# PCB_KioskMB_r3_3-03.net
KiCad netlist of a schematic drawn in EAGLE
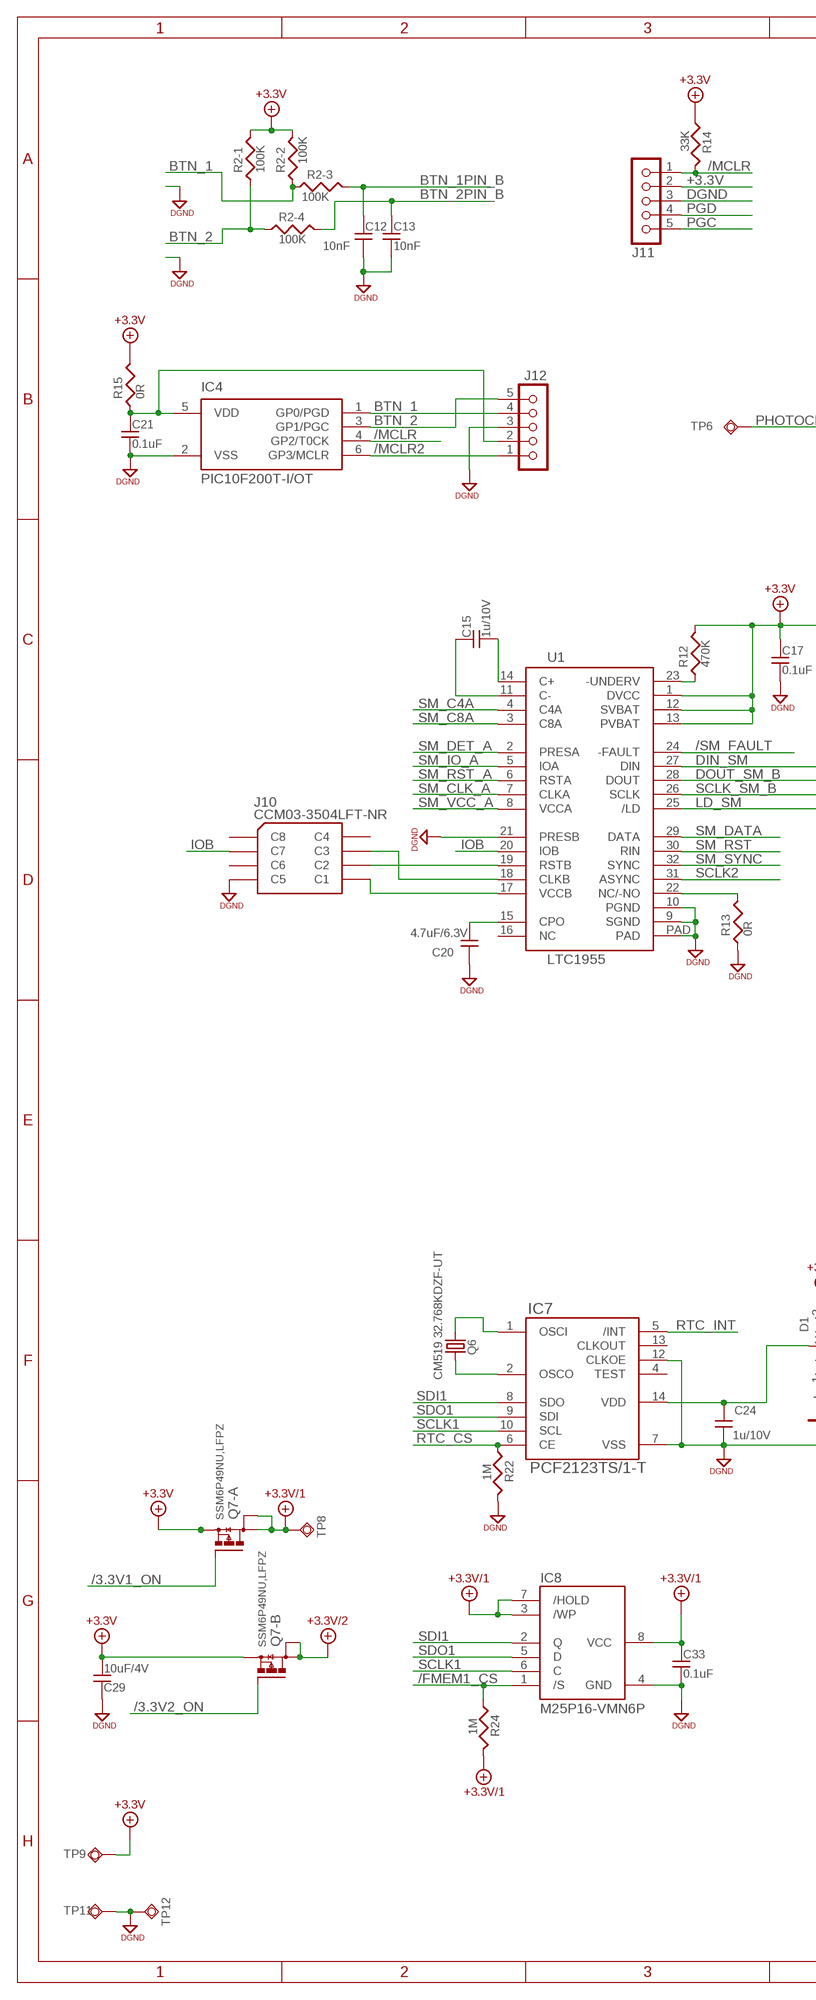
[diagram p0: schematic, sheet 1, part 1 of 2]
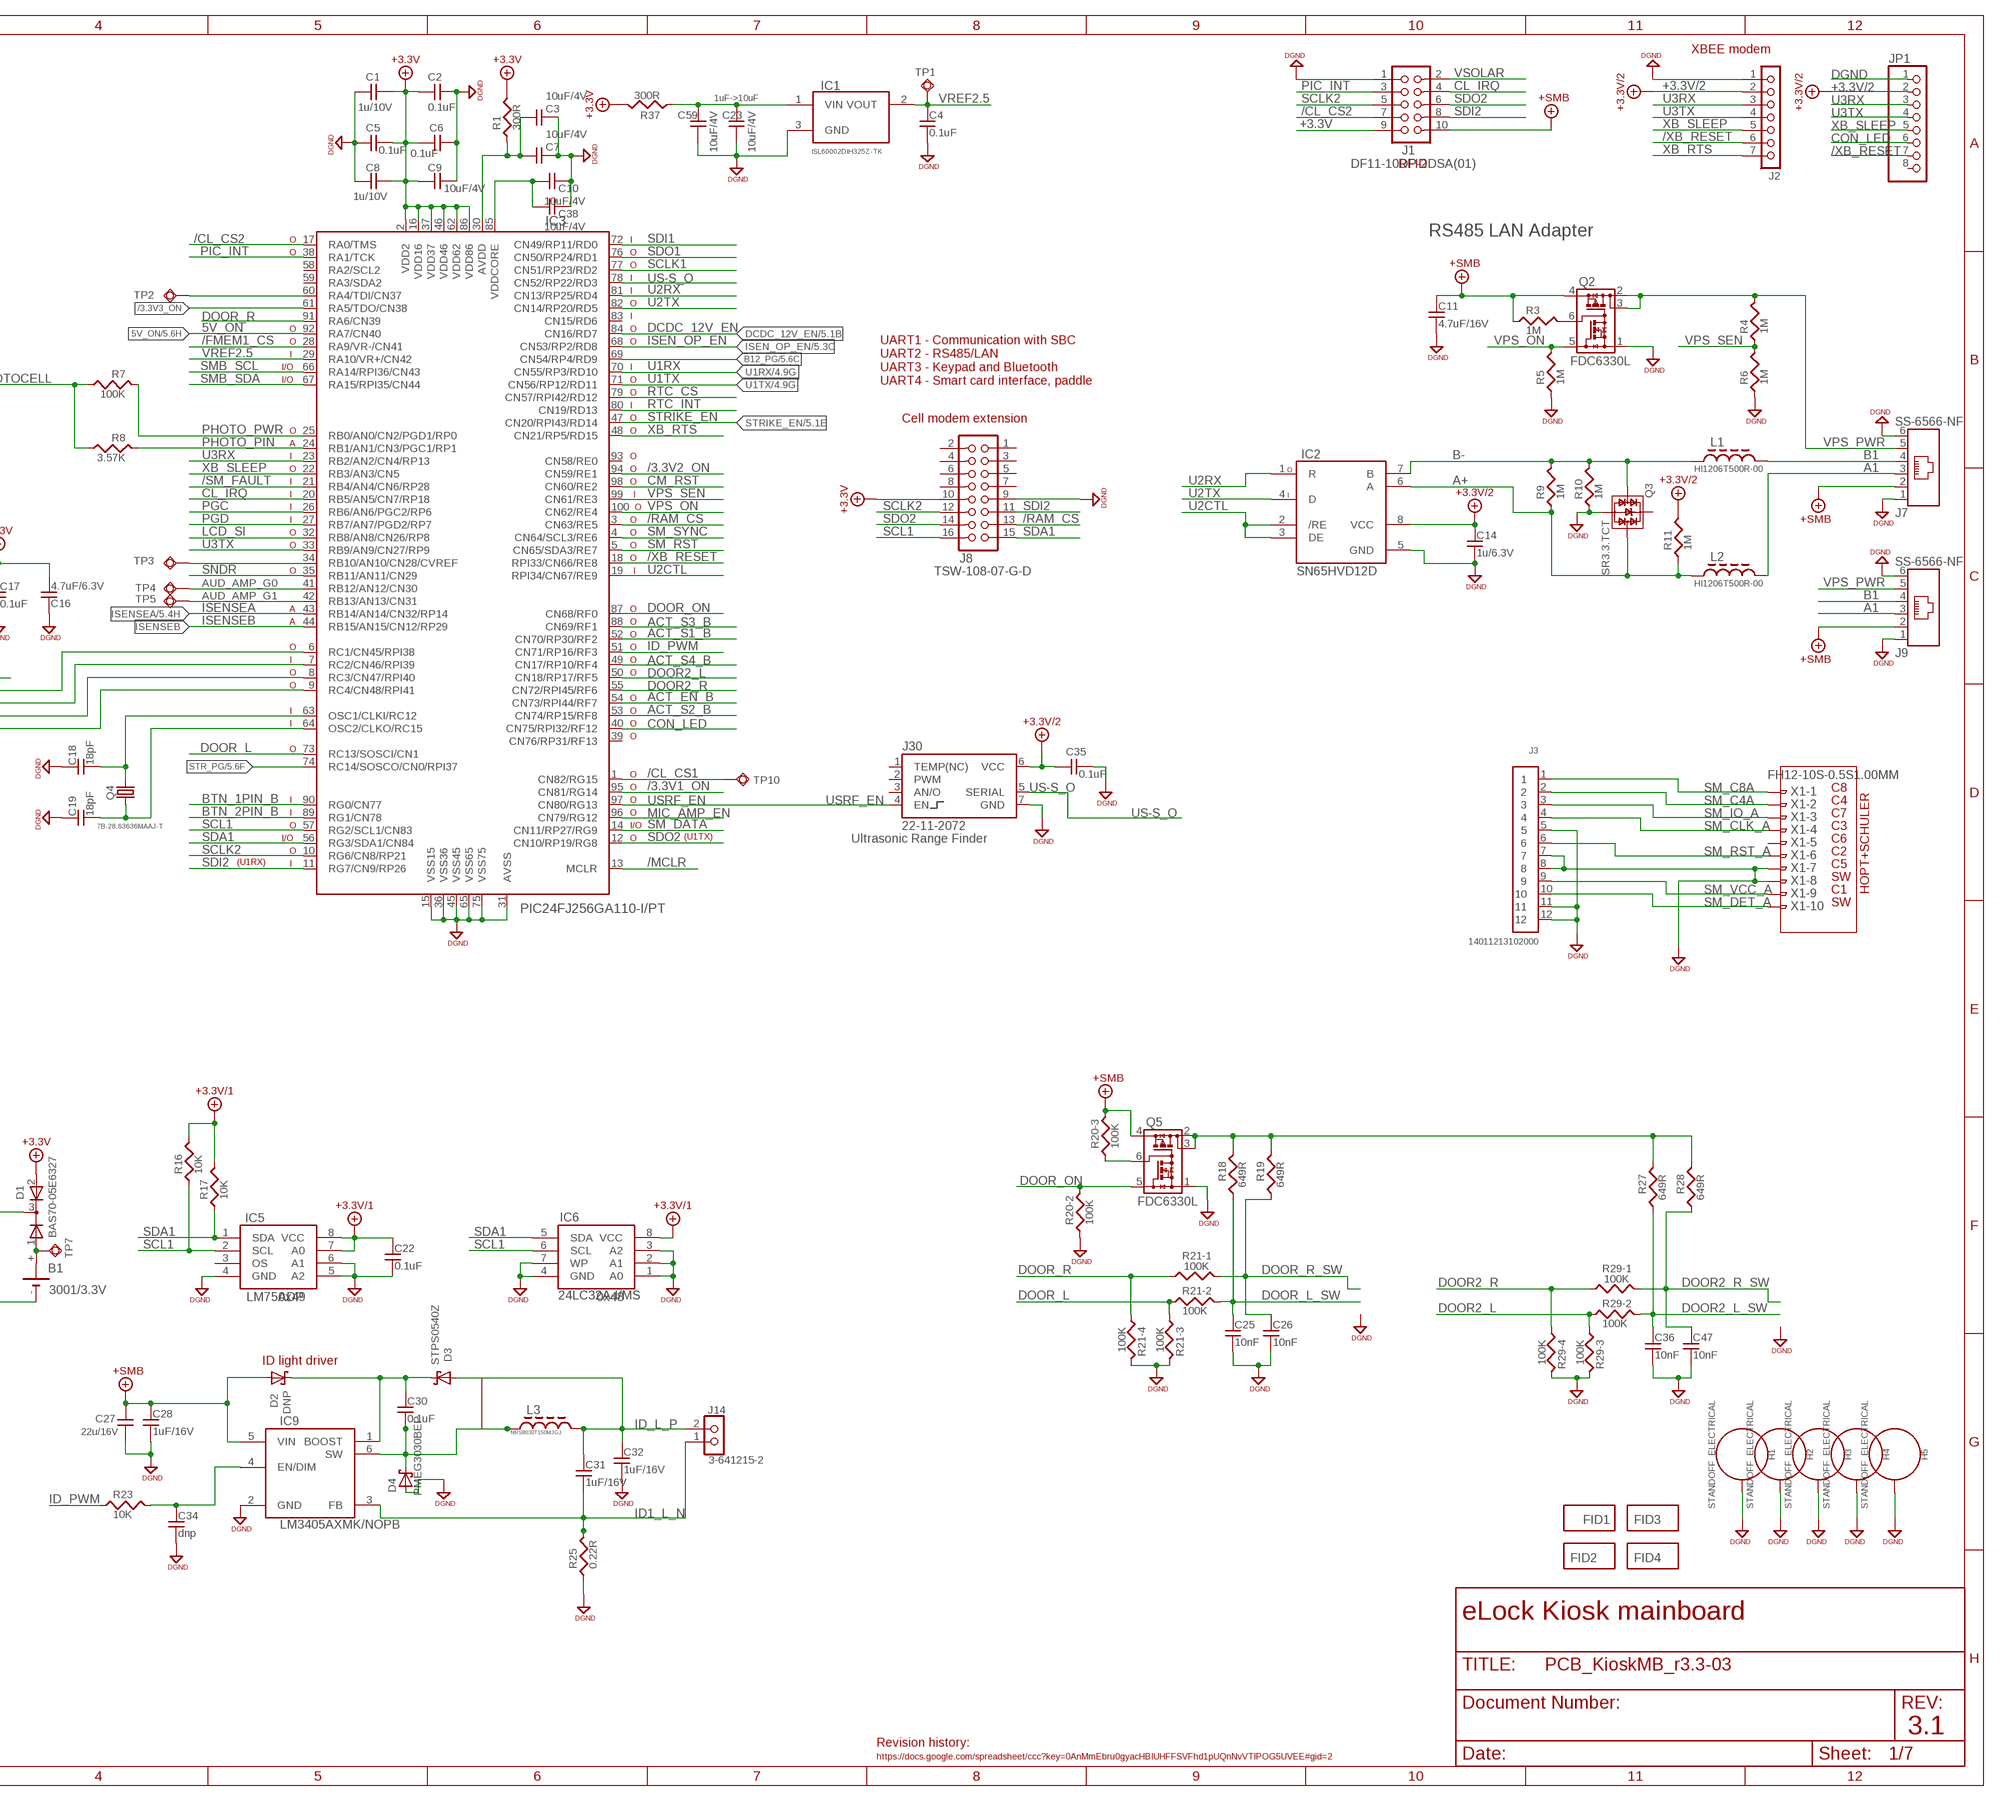
[diagram p1: schematic, sheet 1, part 2 of 2]
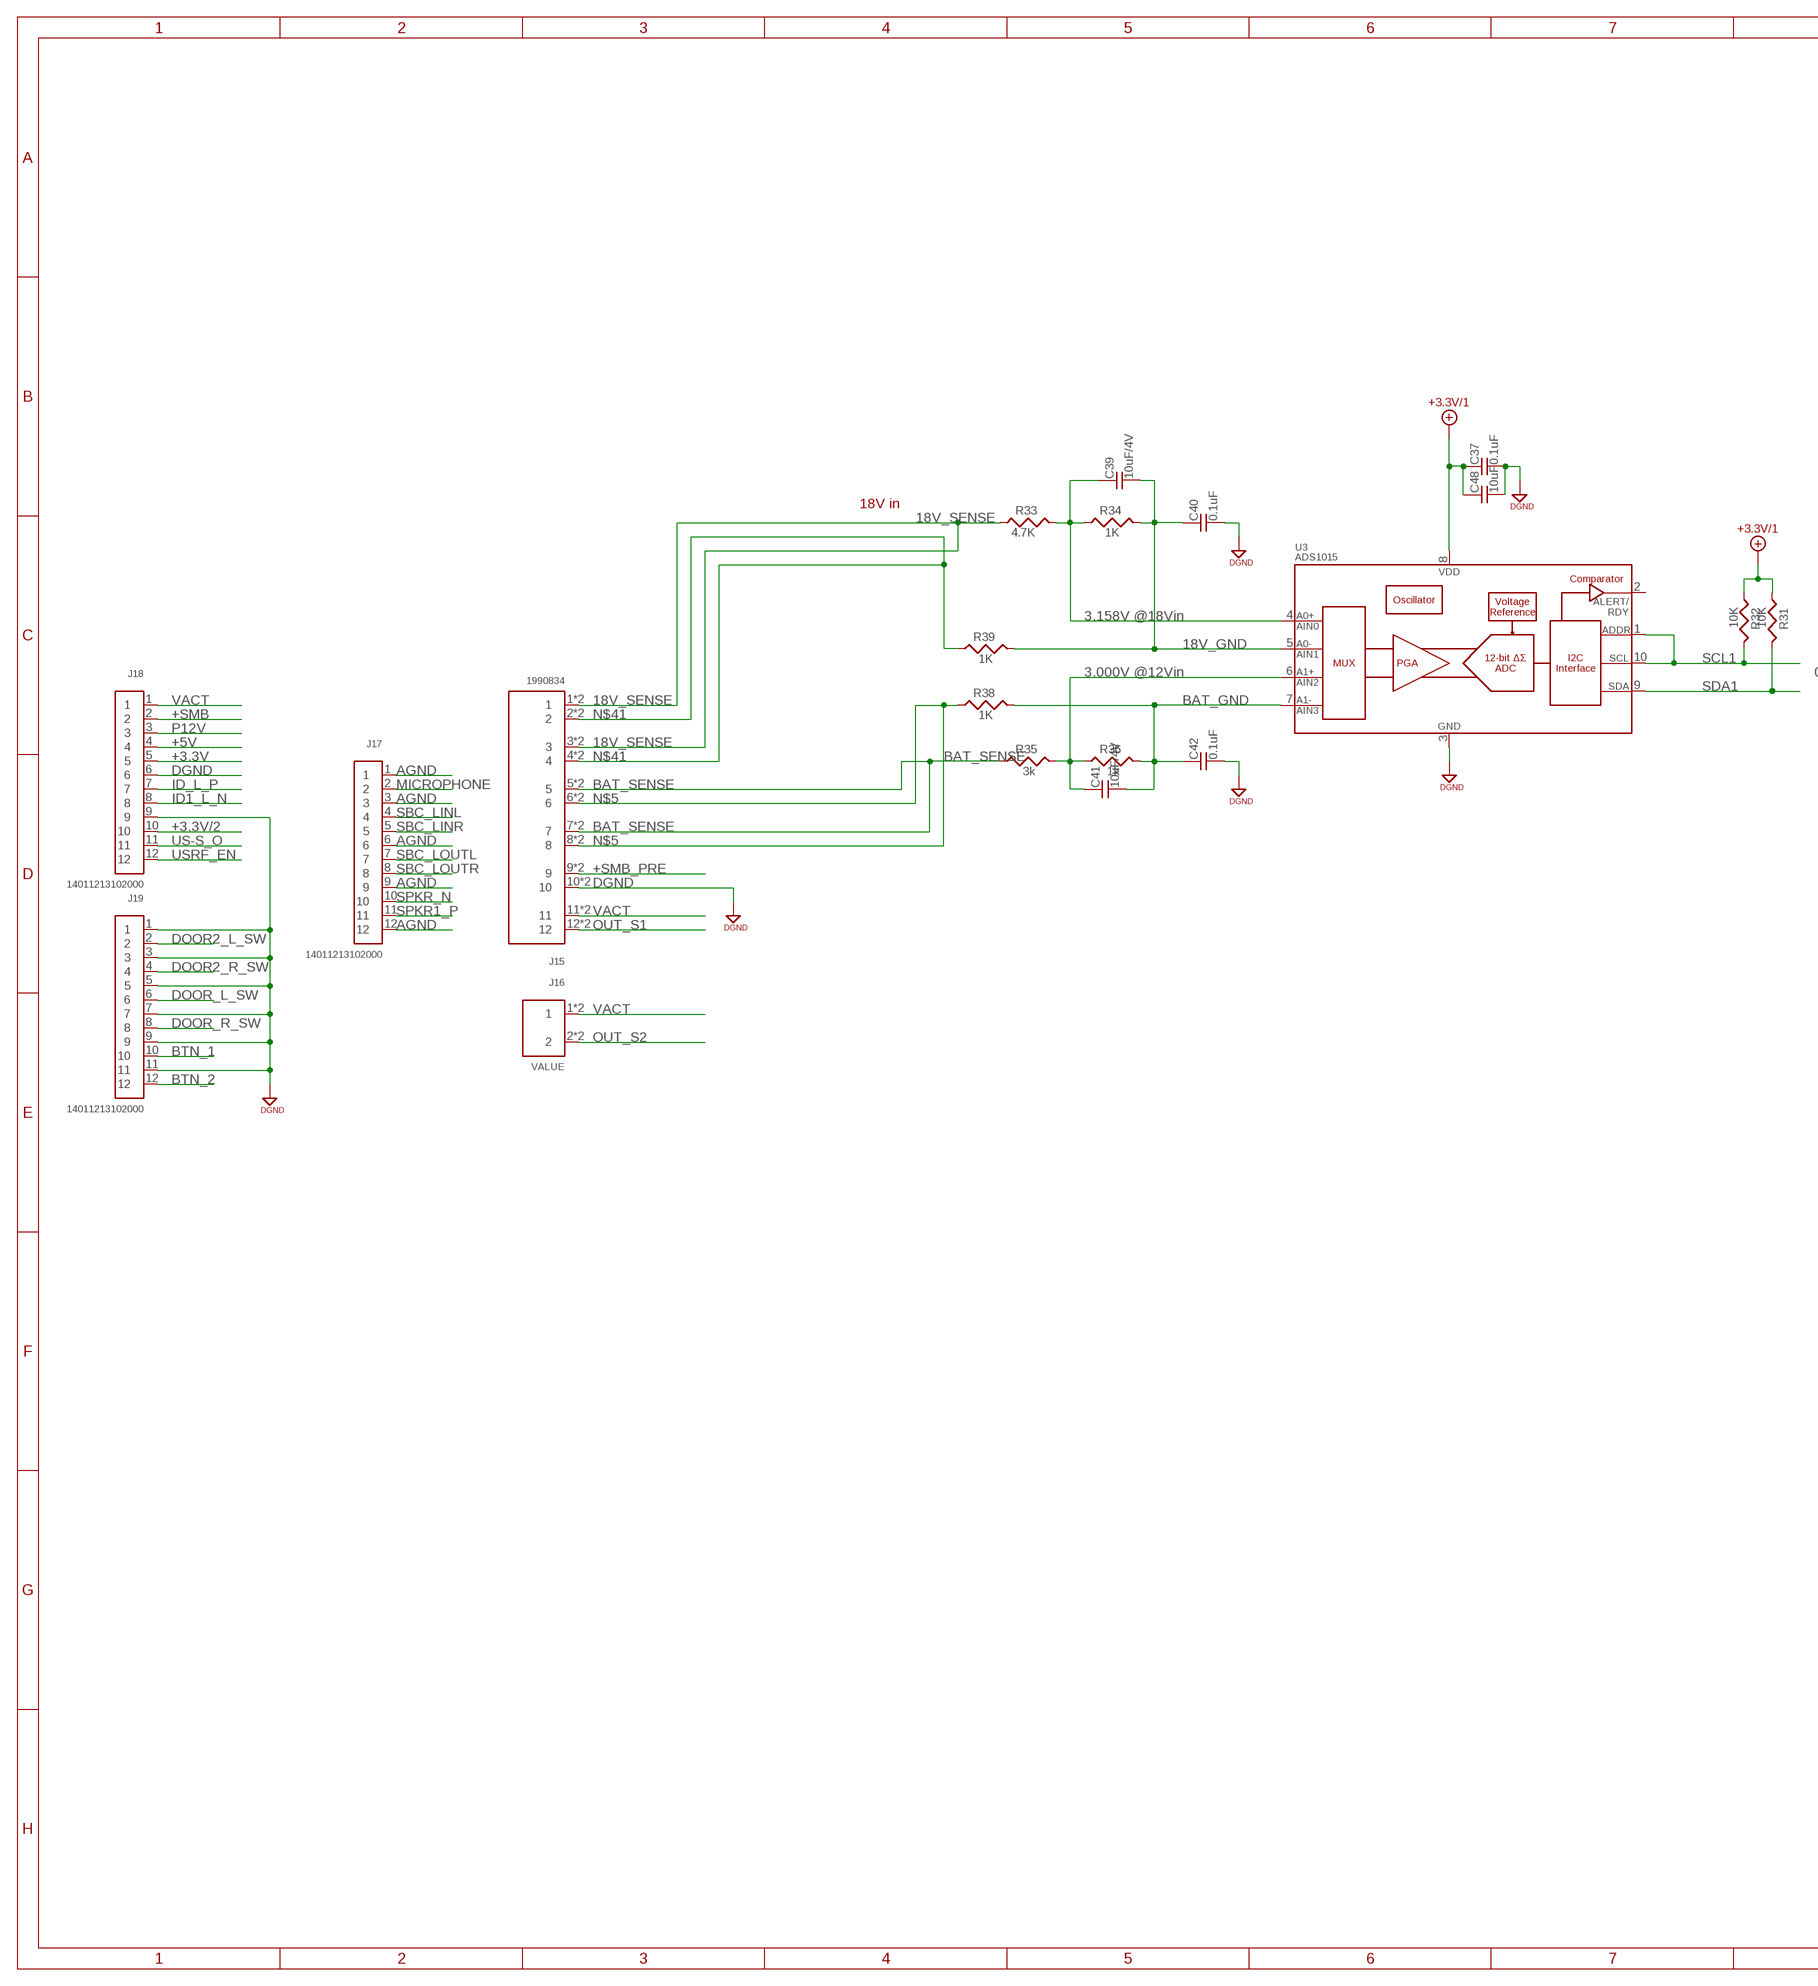
[diagram p2: schematic, sheet 2, part 1 of 2]
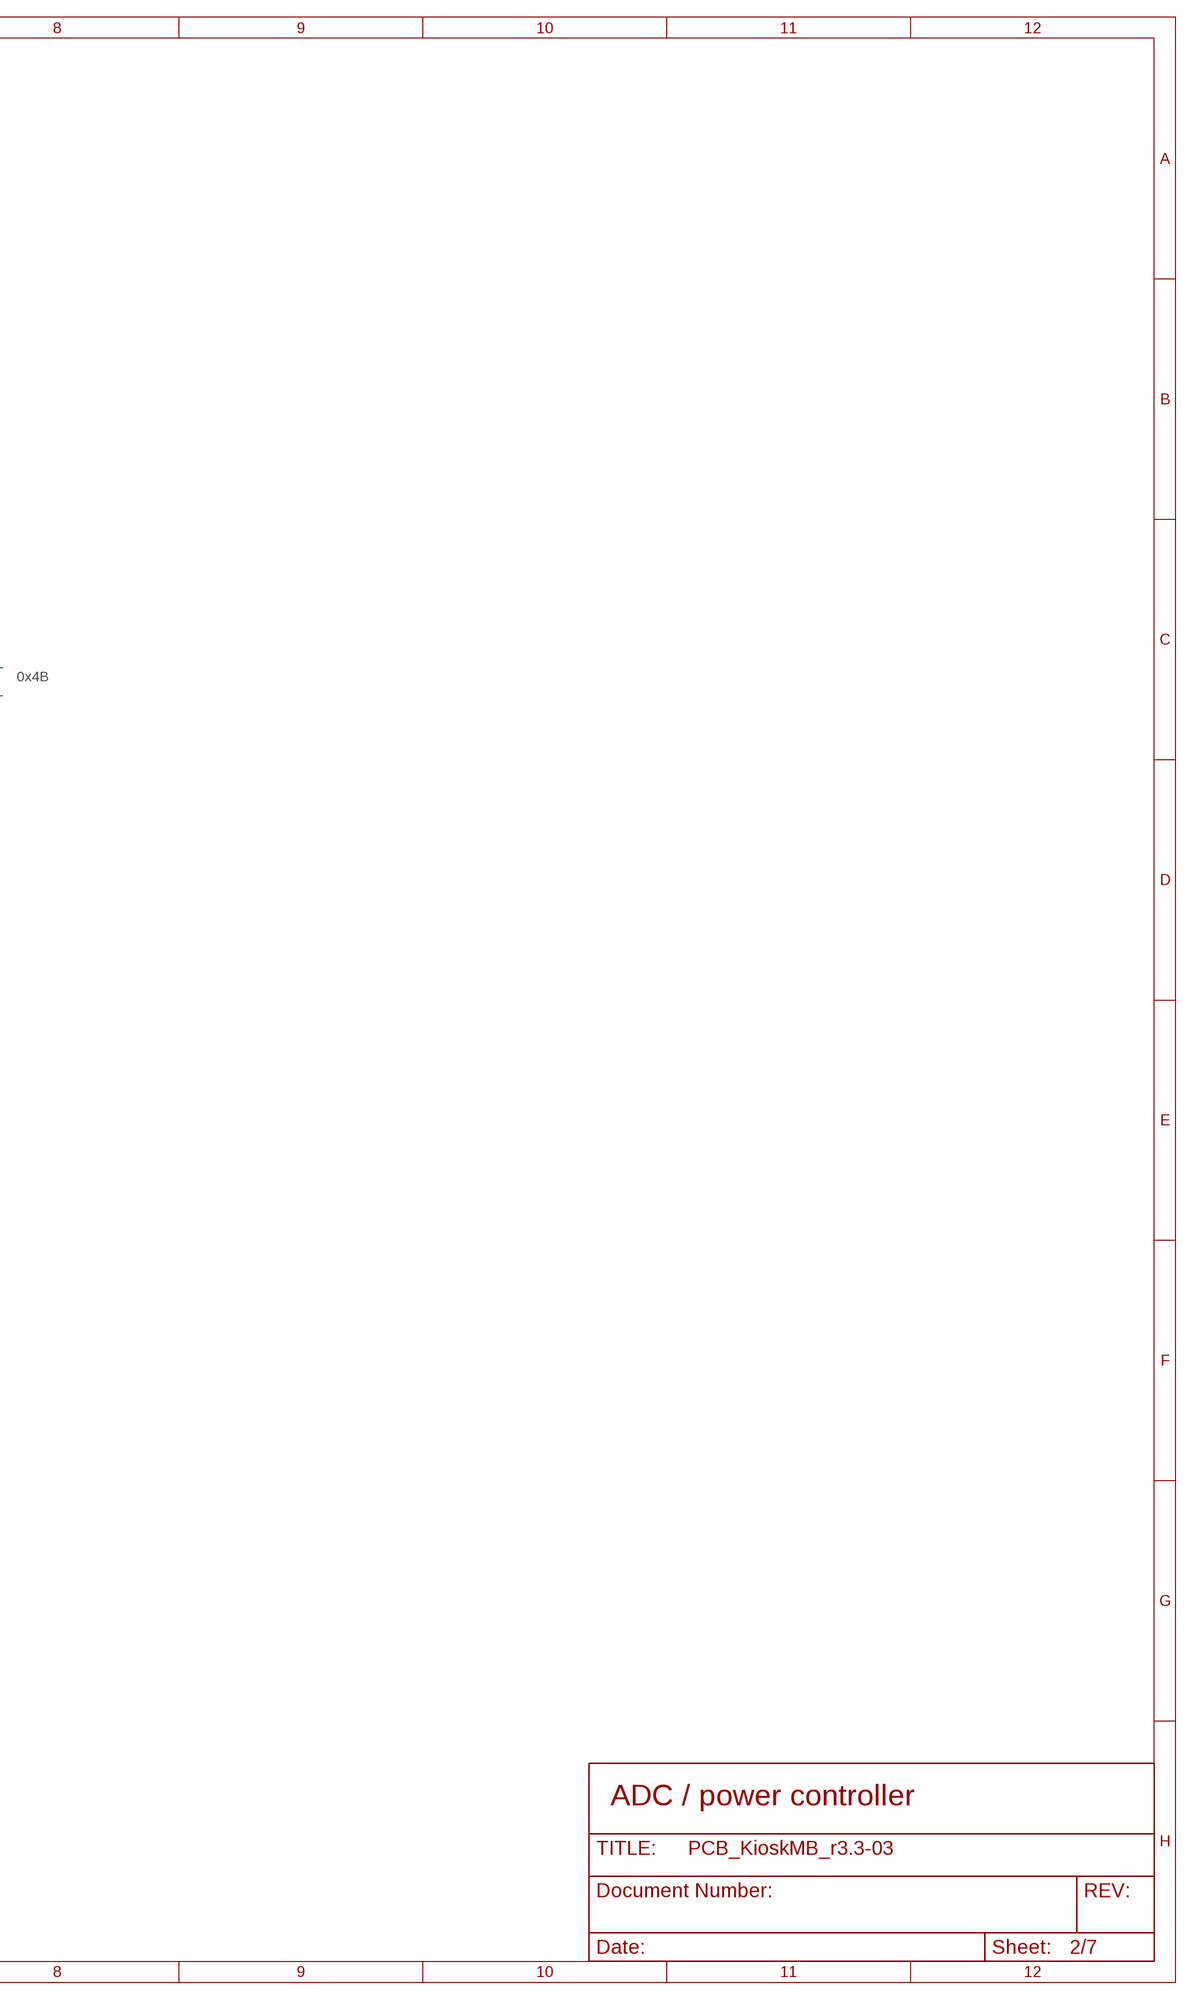
[diagram p3: schematic, sheet 2, part 2 of 2]
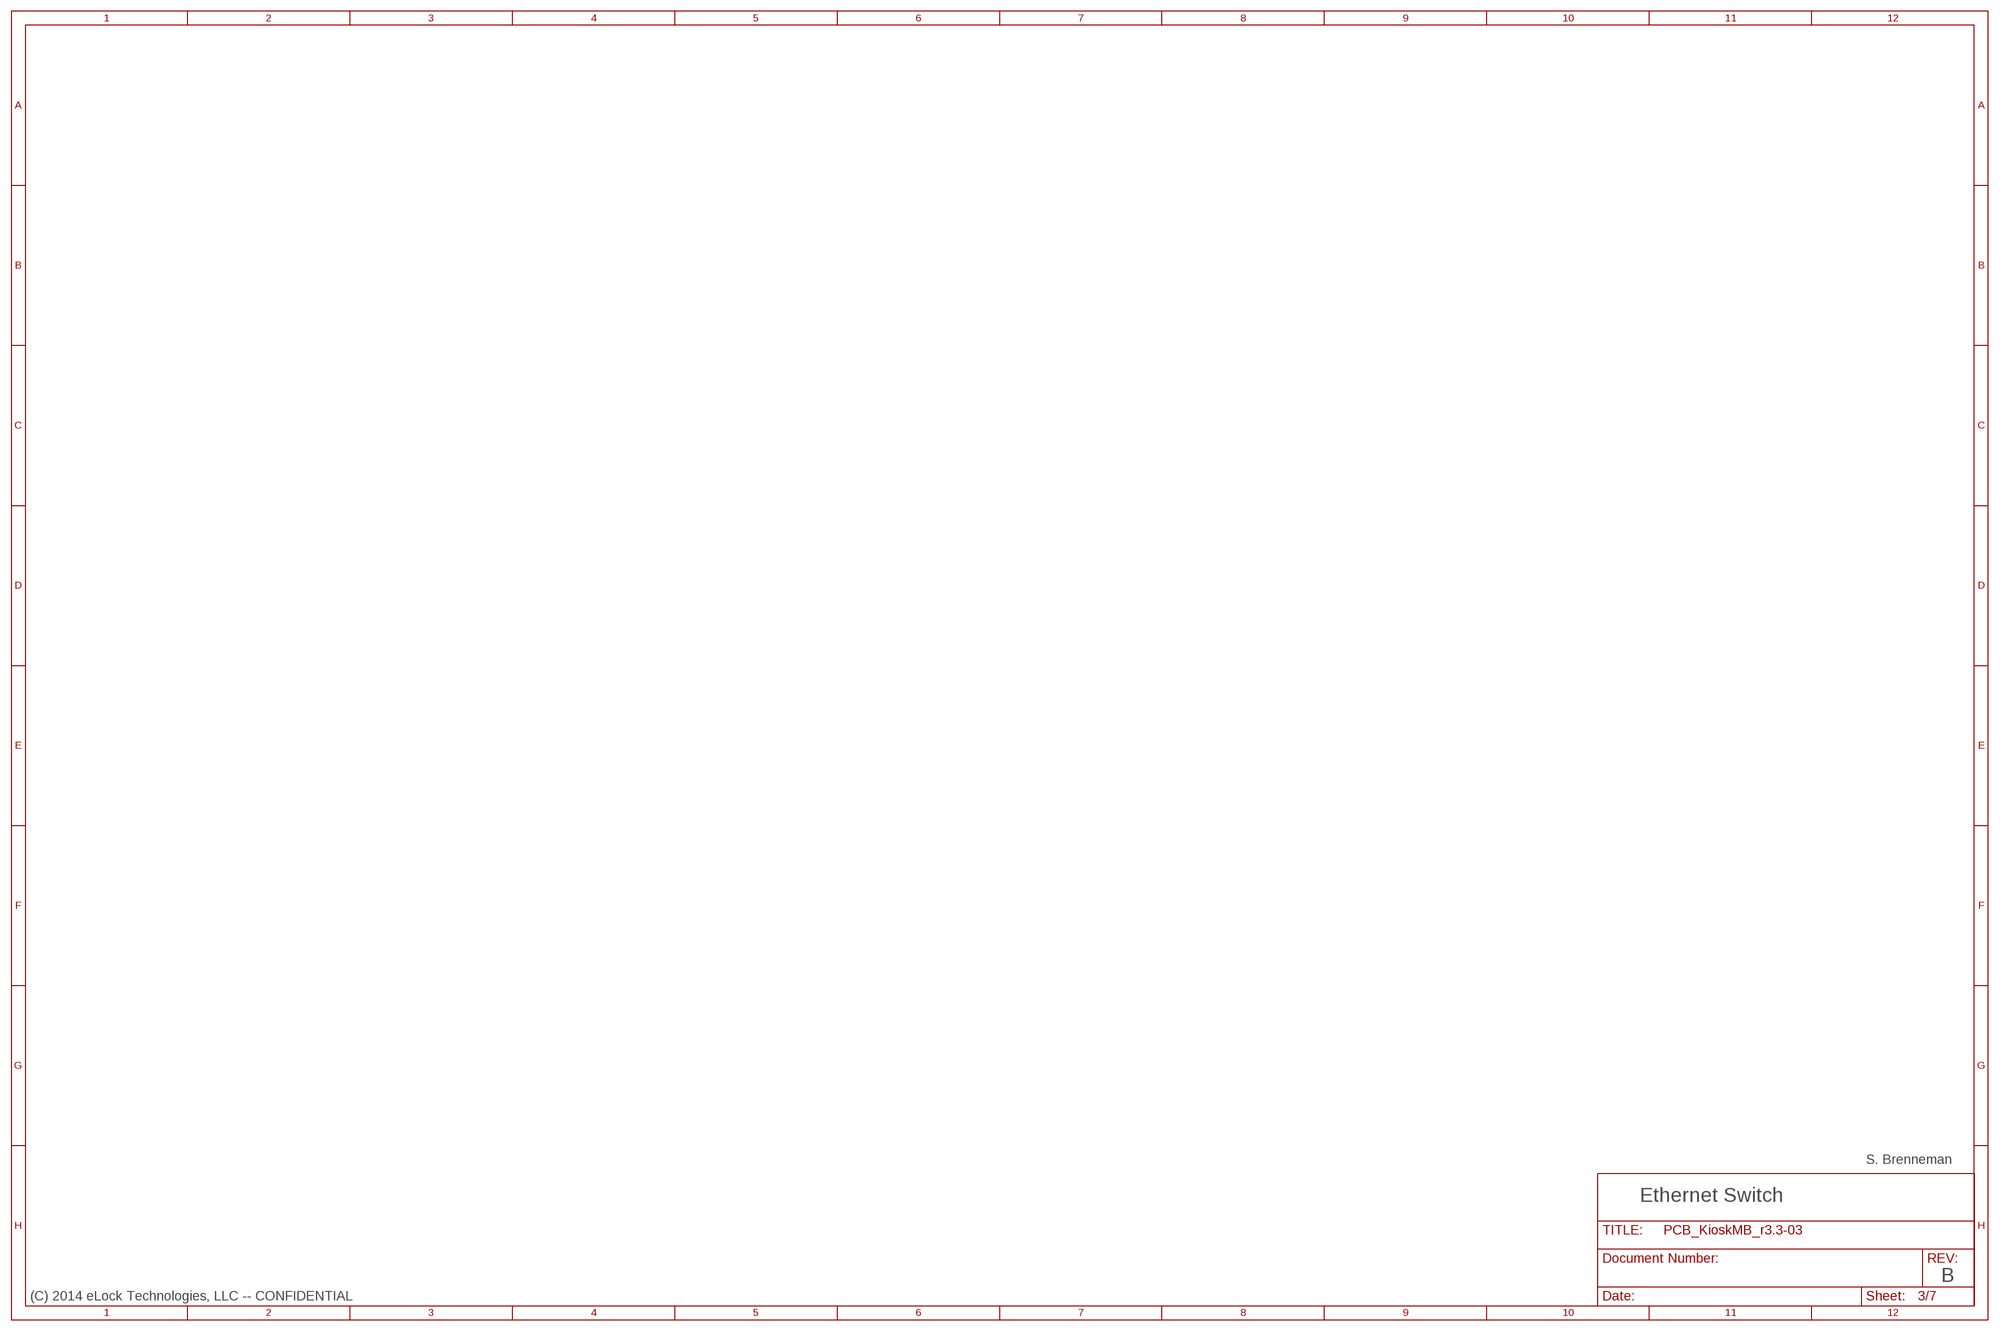
[diagram p4: schematic, sheet 3]
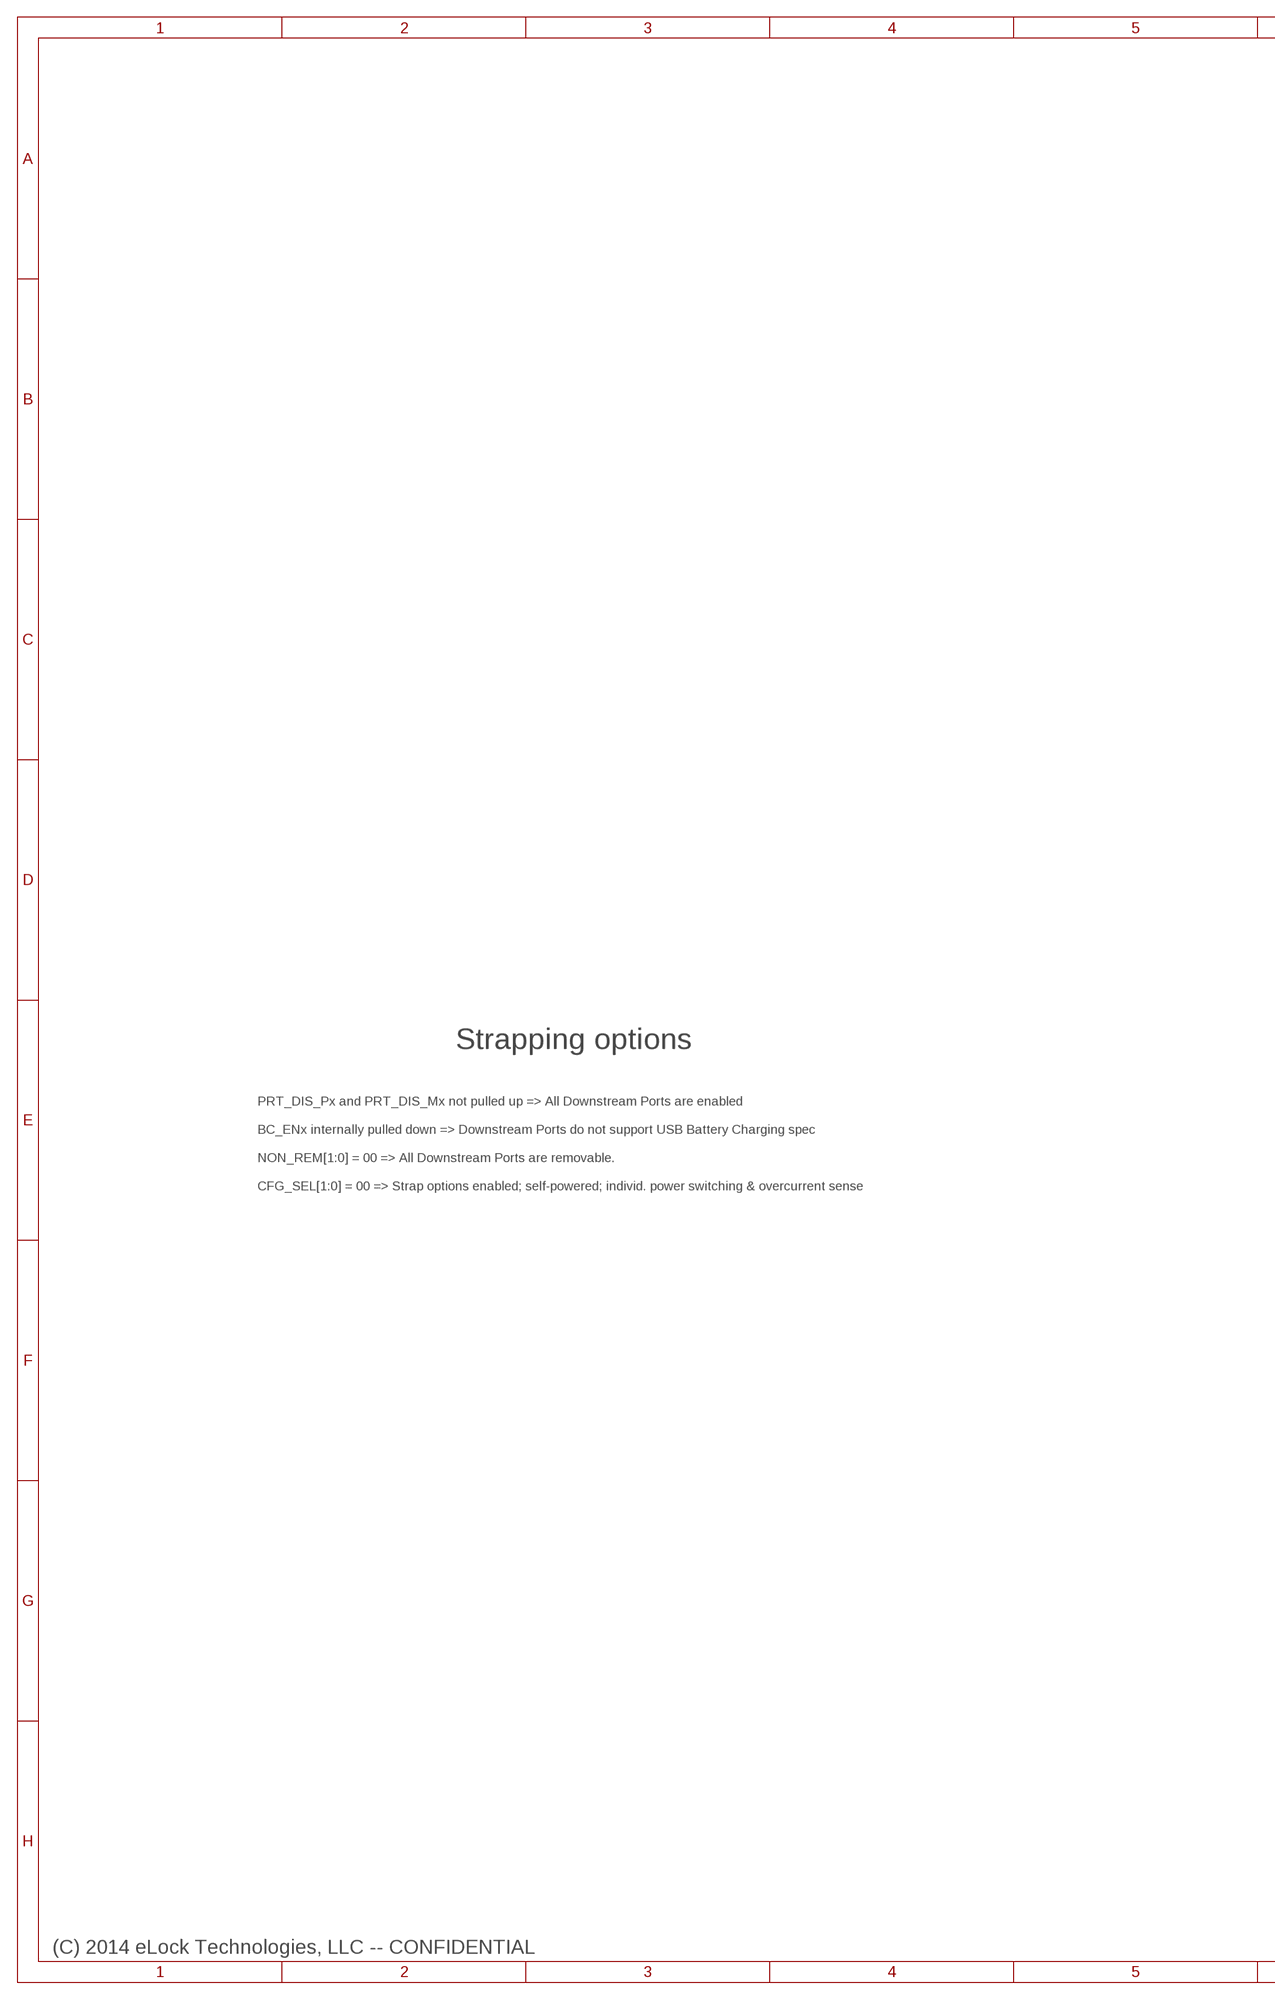
[diagram p5: schematic, sheet 4, part 1 of 2]
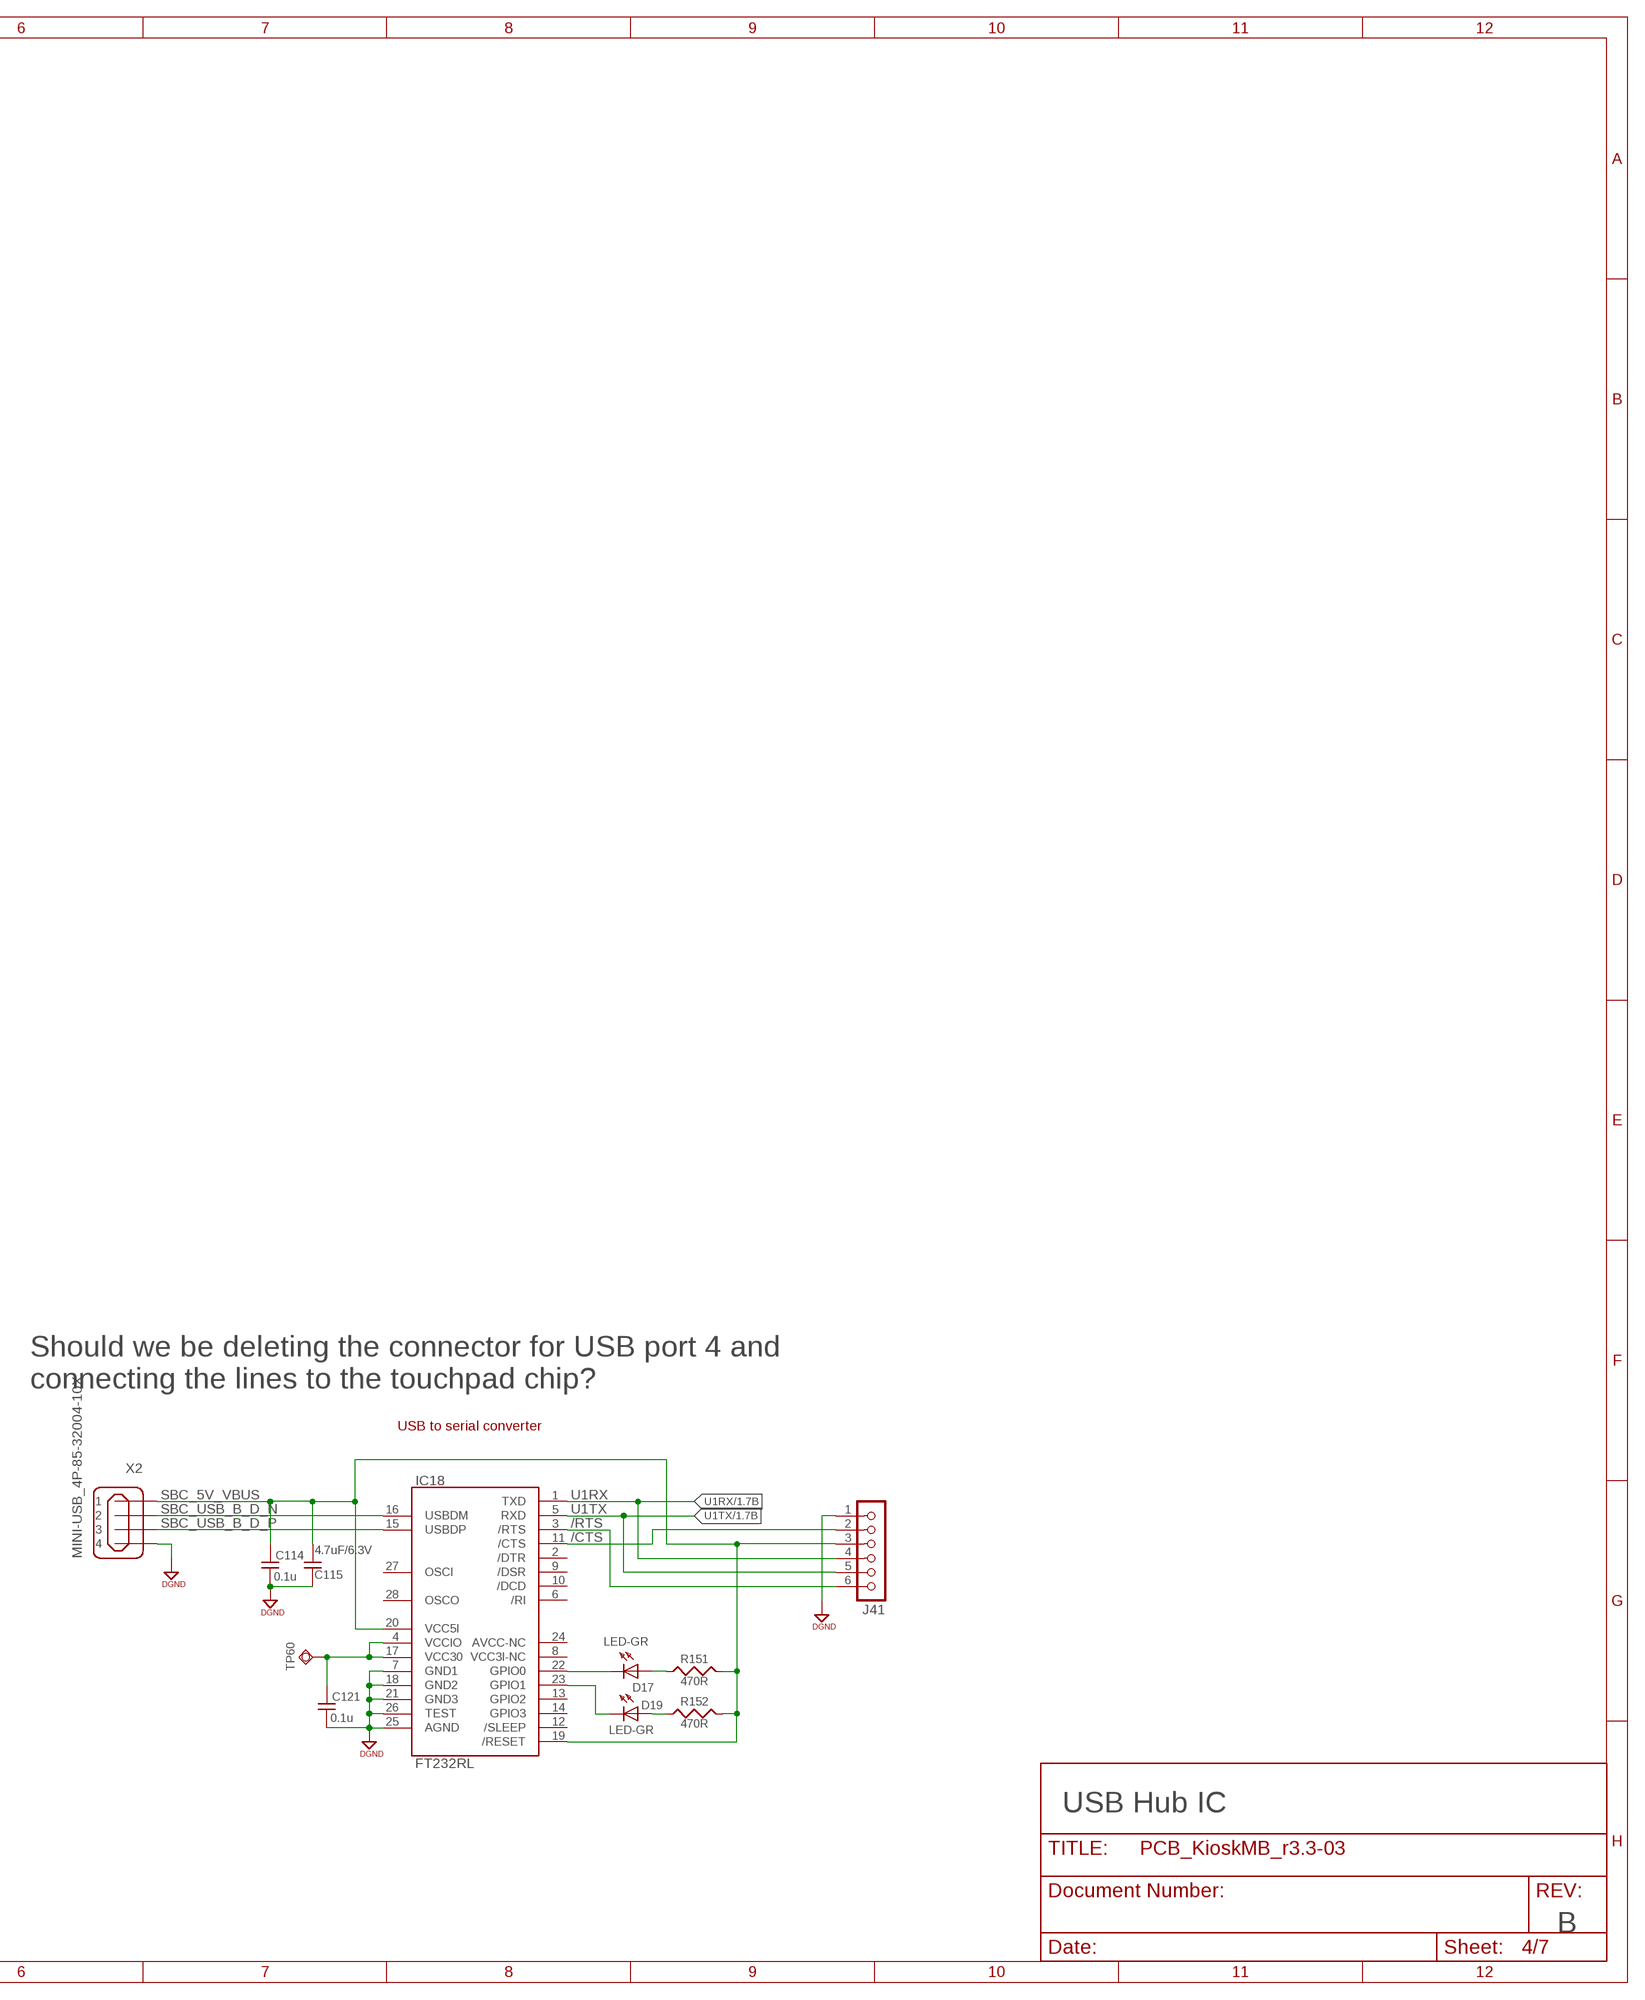
[diagram p6: schematic, sheet 4, part 2 of 2]
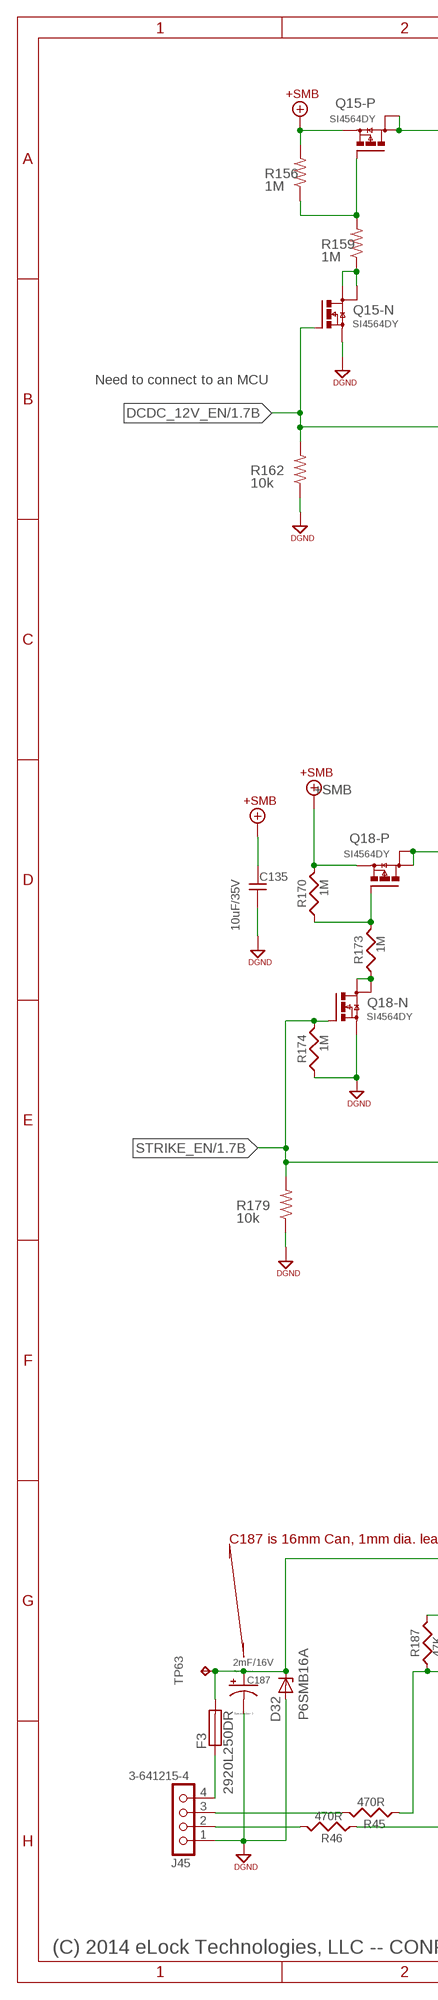
[diagram p7: schematic, sheet 5, part 1 of 2]
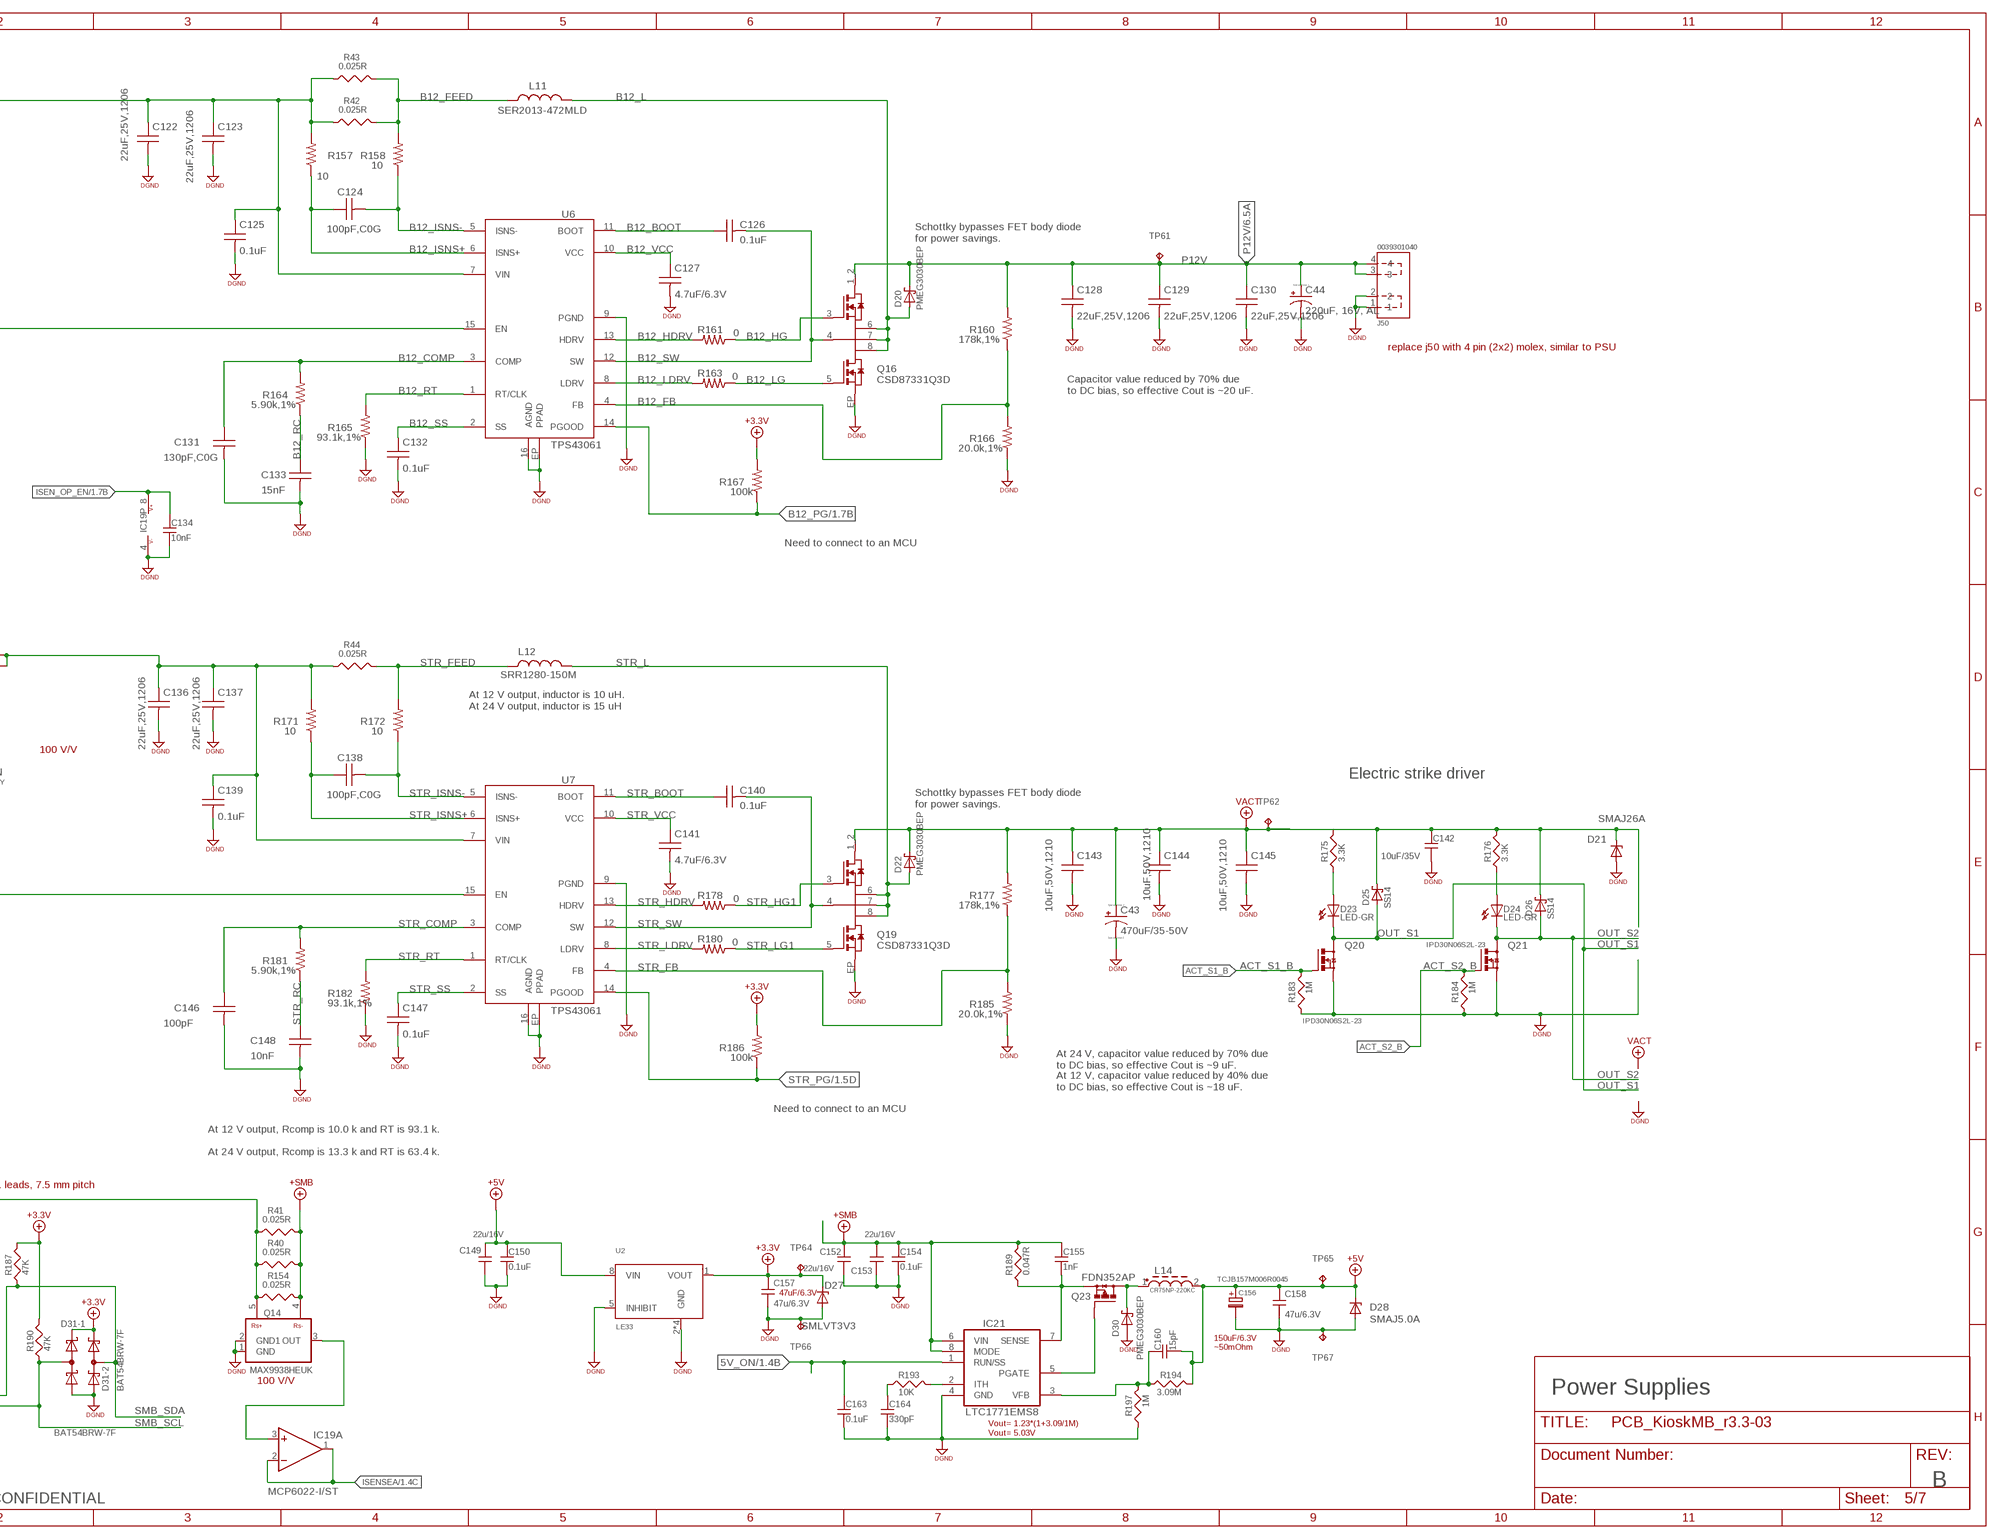
[diagram p8: schematic, sheet 5, part 2 of 2]
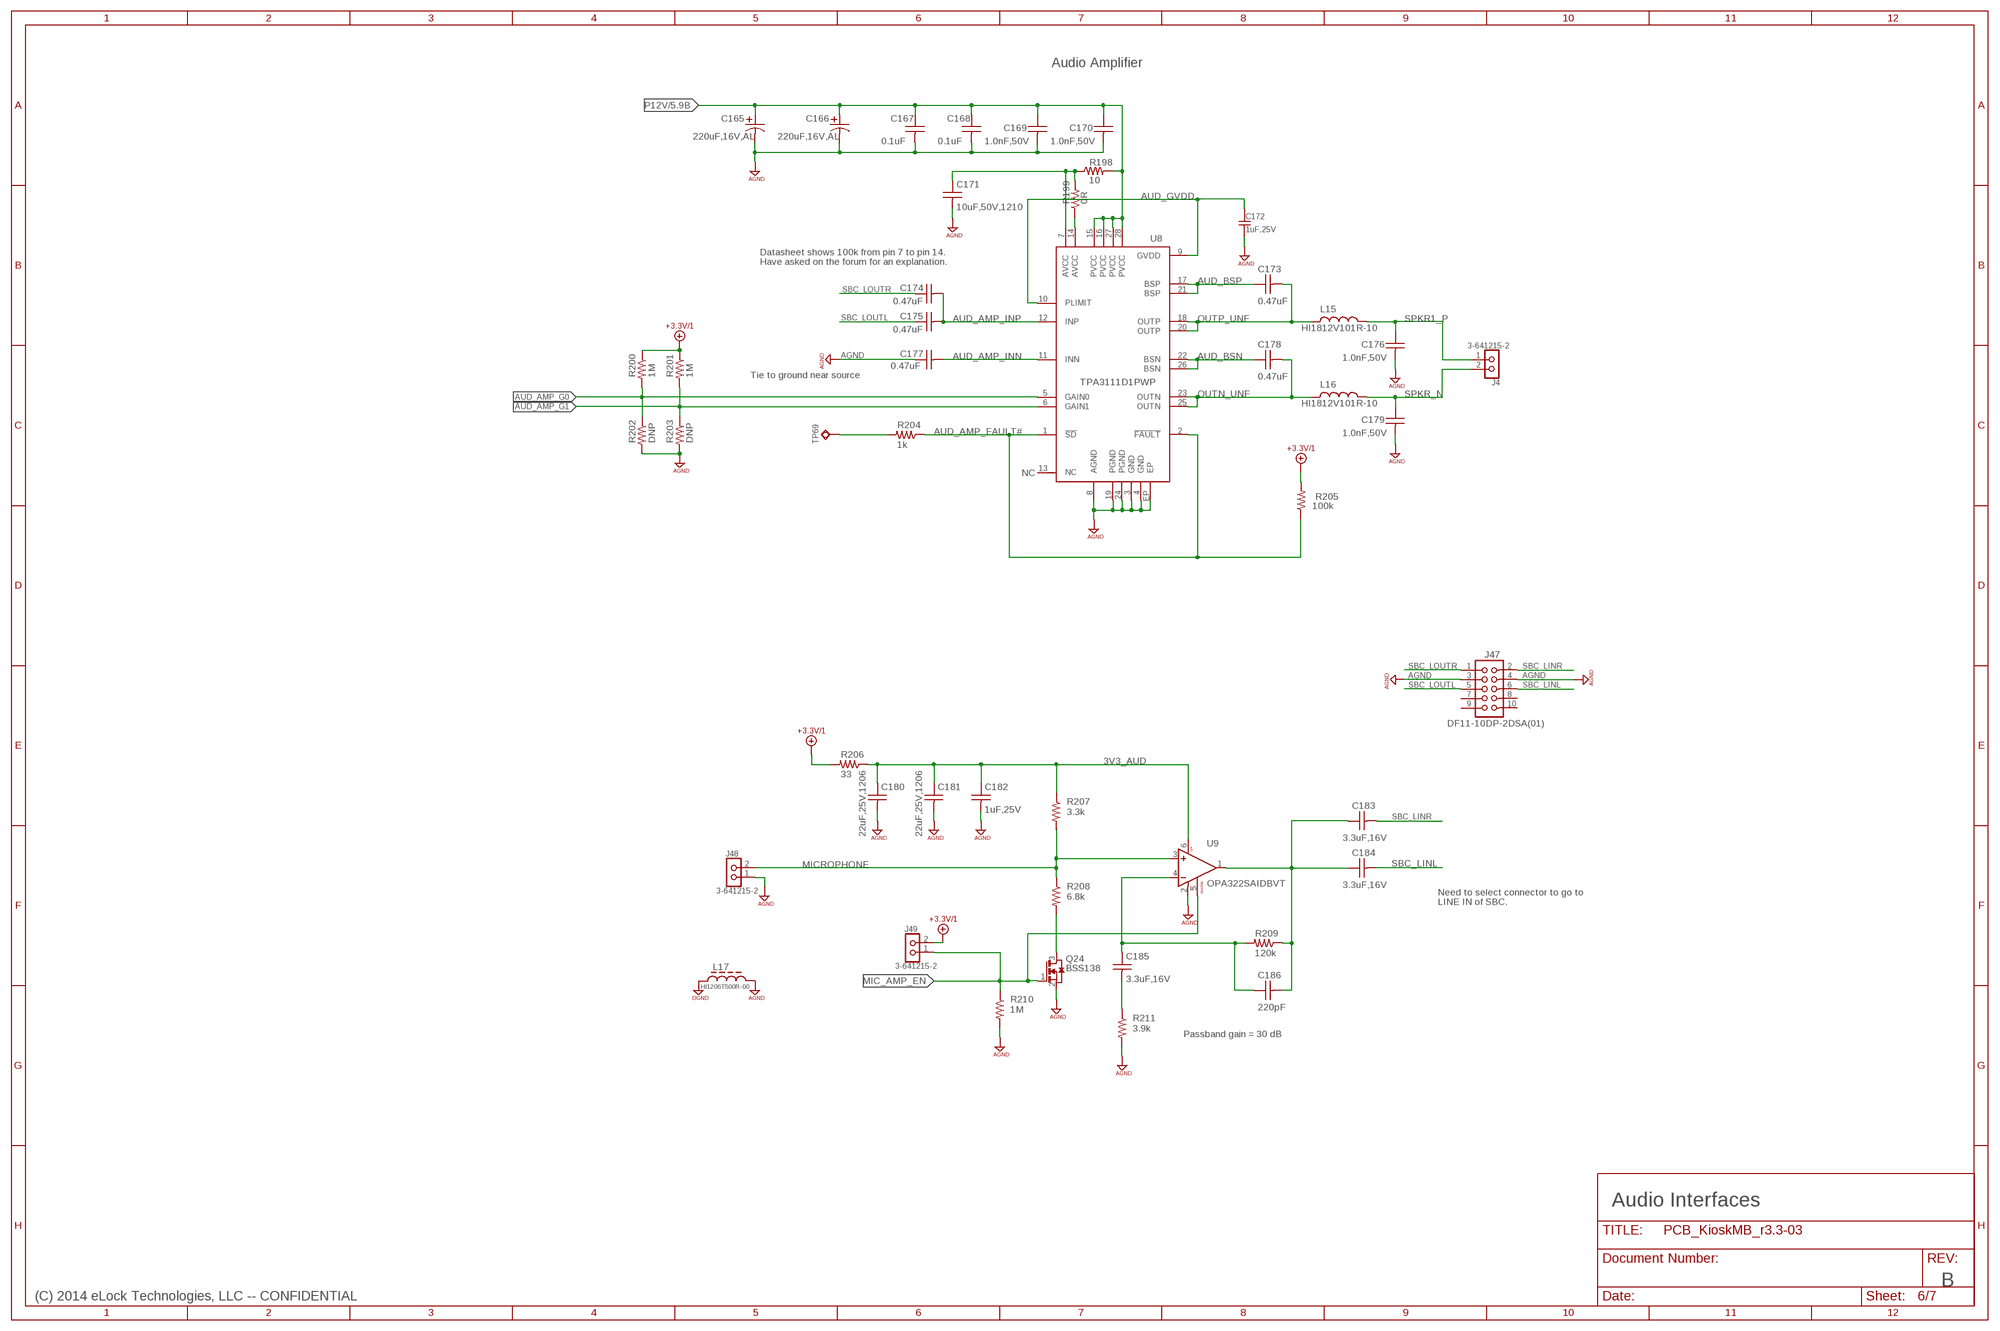
[diagram p9: schematic, sheet 6]
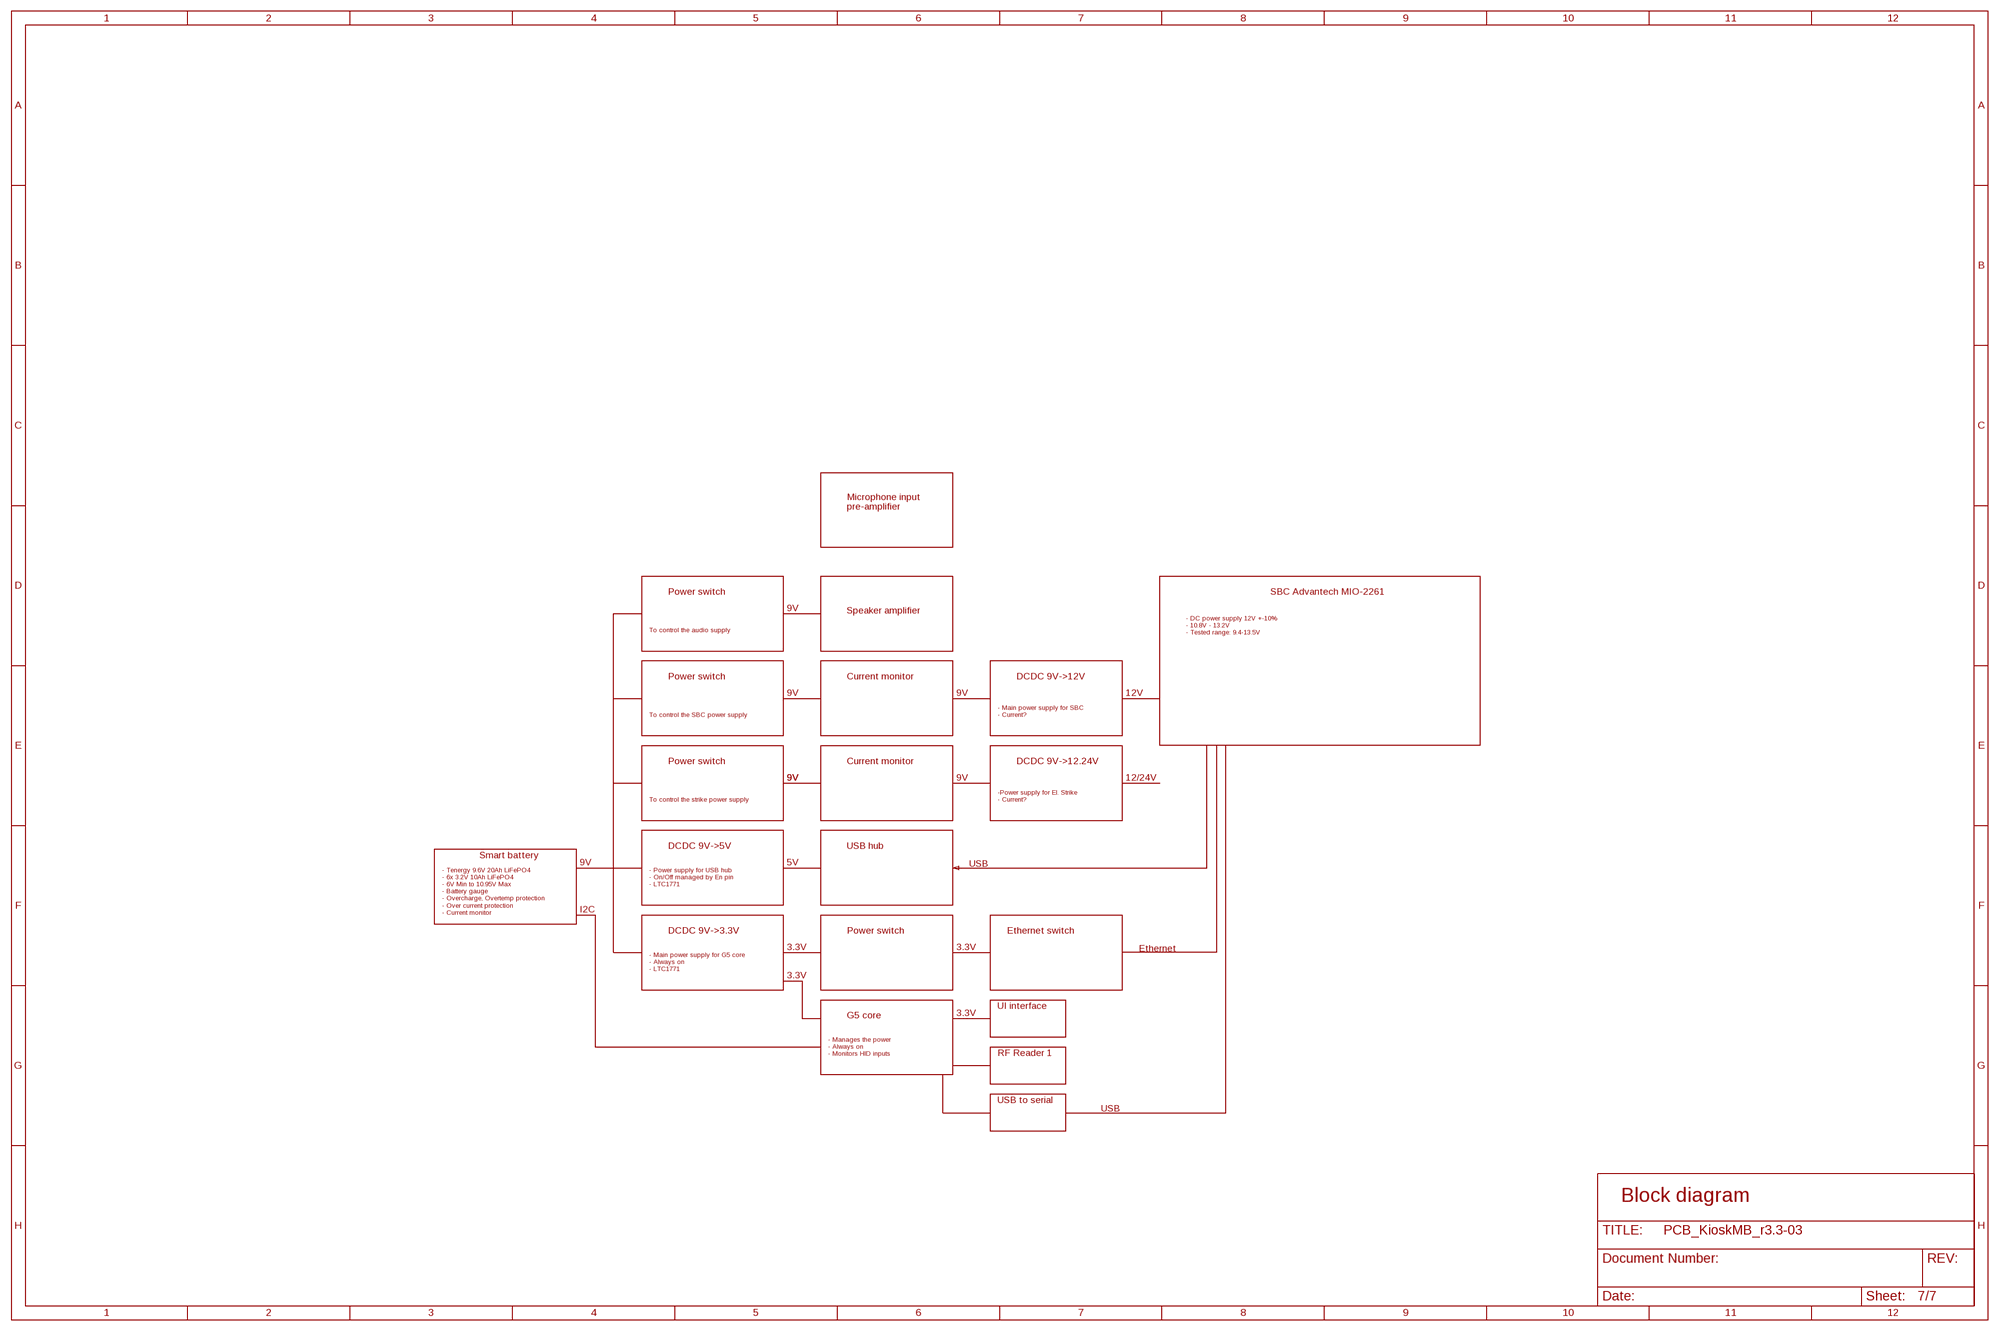
[diagram p10: schematic, sheet 7]

(export (version "E")
  (design (tool "Eeschema 10.0.6"))
  (components
    (comp (ref "C114")
      (value "0.1u")
      (footprint "eagle-import:0603")
      (libsource (lib "eagle-import") (part "C-0603"))
    )
    (comp (ref "C115")
      (value "4.7uF/6.3V")
      (footprint "eagle-import:0603")
      (libsource (lib "eagle-import") (part "C-0603"))
    )
    (comp (ref "C121")
      (value "0.1u")
      (footprint "eagle-import:0603")
      (libsource (lib "eagle-import") (part "C-0603"))
    )
    (comp (ref "D17")
      (value "LED-GR")
      (footprint "eagle-import:0805-POL")
      (libsource (lib "eagle-import") (part "LED-0805"))
    )
    (comp (ref "D19")
      (value "LED-GR")
      (footprint "eagle-import:0805-POL")
      (libsource (lib "eagle-import") (part "LED-0805"))
    )
    (comp (ref "IC18")
      (value "FT232RL")
      (footprint "eagle-import:SSOP28DB")
      (libsource (lib "eagle-import") (part "FT232RL"))
    )
    (comp (ref "J41")
      (value "MA06-1")
      (footprint "eagle-import:MA06-1")
      (libsource (lib "eagle-import") (part "MA06-1"))
    )
    (comp (ref "R151")
      (value "470R")
      (footprint "eagle-import:0603")
      (libsource (lib "eagle-import") (part "R-0603"))
    )
    (comp (ref "R152")
      (value "470R")
      (footprint "eagle-import:0603")
      (libsource (lib "eagle-import") (part "R-0603"))
    )
    (comp (ref "TP60")
      (value "ROUND_SMD0.7MM")
      (footprint "eagle-import:SMD_ROUND_07MM")
      (libsource (lib "eagle-import") (part "ROUND_SMD0.7MM"))
    )
    (comp (ref "X2")
      (value "MINI-USB_4P-85-32004-10X")
      (footprint "eagle-import:85-32004-10X")
      (libsource (lib "eagle-import") (part "MINI-USB_4P-85-32004-10X"))
    )
    (comp (ref "C165")
      (value "220uF,16V,AL")
      (footprint "eagle-import:CAP_6.3MM_DIA_SMT")
      (fields (field (name "MANUFACTURER") "Kemet") (field (name "MFR_PN") "EEV227M016A9HAA"))
      (libsource (lib "eagle-import") (part "CAP_ELEC_6.3MM_SMD"))
    )
    (comp (ref "C166")
      (value "220uF,16V,AL")
      (footprint "eagle-import:CAP_6.3MM_DIA_SMT")
      (fields (field (name "MANUFACTURER") "Kemet") (field (name "MFR_PN") "EEV227M016A9HAA"))
      (libsource (lib "eagle-import") (part "CAP_ELEC_6.3MM_SMD"))
    )
    (comp (ref "C167")
      (value "0.1uF")
      (footprint "eagle-import:C0603")
      (libsource (lib "eagle-import") (part "C-US-NP0603"))
    )
    (comp (ref "C168")
      (value "0.1uF")
      (footprint "eagle-import:C0603")
      (libsource (lib "eagle-import") (part "C-US-NP0603"))
    )
    (comp (ref "C169")
      (value "1.0nF,50V")
      (footprint "eagle-import:C0603")
      (fields (field (name "MANUFACTURER") "Samsung"))
      (libsource (lib "eagle-import") (part "C-US-NP0603"))
    )
    (comp (ref "C170")
      (value "1.0nF,50V")
      (footprint "eagle-import:C0603")
      (fields (field (name "MANUFACTURER") "Samsung"))
      (libsource (lib "eagle-import") (part "C-US-NP0603"))
    )
    (comp (ref "C171")
      (value "10uF,50V,1210")
      (footprint "eagle-import:C1210")
      (fields (field (name "MANUFACTURER") "Samsung"))
      (libsource (lib "eagle-import") (part "C-US-NP1210"))
    )
    (comp (ref "C172")
      (value "1uF,25V")
      (footprint "eagle-import:0603")
      (libsource (lib "eagle-import") (part "C-0603"))
    )
    (comp (ref "C173")
      (value "0.47uF")
      (footprint "eagle-import:C0603")
      (fields (field (name "MANUFACTURER") "Taiyo Yuden"))
      (libsource (lib "eagle-import") (part "C-US-NP0603"))
    )
    (comp (ref "C174")
      (value "0.47uF")
      (footprint "eagle-import:C0603")
      (fields (field (name "MANUFACTURER") "Samsung"))
      (libsource (lib "eagle-import") (part "C-US-NP0603"))
    )
    (comp (ref "C175")
      (value "0.47uF")
      (footprint "eagle-import:C0603")
      (fields (field (name "MANUFACTURER") "Samsung"))
      (libsource (lib "eagle-import") (part "C-US-NP0603"))
    )
    (comp (ref "C176")
      (value "1.0nF,50V")
      (footprint "eagle-import:C0603")
      (fields (field (name "MANUFACTURER") "Samsung"))
      (libsource (lib "eagle-import") (part "C-US-NP0603"))
    )
    (comp (ref "C177")
      (value "0.47uF")
      (footprint "eagle-import:C0603")
      (fields (field (name "MANUFACTURER") "Samsung"))
      (libsource (lib "eagle-import") (part "C-US-NP0603"))
    )
    (comp (ref "C178")
      (value "0.47uF")
      (footprint "eagle-import:C0603")
      (fields (field (name "MANUFACTURER") "Taiyo Yuden"))
      (libsource (lib "eagle-import") (part "C-US-NP0603"))
    )
    (comp (ref "C179")
      (value "1.0nF,50V")
      (footprint "eagle-import:C0603")
      (fields (field (name "MANUFACTURER") "Samsung"))
      (libsource (lib "eagle-import") (part "C-US-NP0603"))
    )
    (comp (ref "C180")
      (value "22uF,25V,1206")
      (footprint "eagle-import:C1206")
      (fields (field (name "MANUFACTURER") "Samsung"))
      (libsource (lib "eagle-import") (part "C-US-NP1206"))
    )
    (comp (ref "C181")
      (value "22uF,25V,1206")
      (footprint "eagle-import:C1206")
      (fields (field (name "MANUFACTURER") "Samsung"))
      (libsource (lib "eagle-import") (part "C-US-NP1206"))
    )
    (comp (ref "C182")
      (value "1uF,25V")
      (footprint "eagle-import:C0603")
      (libsource (lib "eagle-import") (part "C-US-NP0603"))
    )
    (comp (ref "C183")
      (value "3.3uF,16V")
      (footprint "eagle-import:C0603")
      (libsource (lib "eagle-import") (part "C-US-NP0603"))
    )
    (comp (ref "C184")
      (value "3.3uF,16V")
      (footprint "eagle-import:C0603")
      (libsource (lib "eagle-import") (part "C-US-NP0603"))
    )
    (comp (ref "C185")
      (value "3.3uF,16V")
      (footprint "eagle-import:C0603")
      (libsource (lib "eagle-import") (part "C-US-NP0603"))
    )
    (comp (ref "C186")
      (value "220pF")
      (footprint "eagle-import:C0603")
      (libsource (lib "eagle-import") (part "C-US-NP0603"))
    )
    (comp (ref "J4")
      (value "3-641215-2")
      (footprint "eagle-import:3-641215-2")
      (libsource (lib "eagle-import") (part "3-641215-2"))
    )
    (comp (ref "J47")
      (value "DF11-10DP-2DSA(01)")
      (footprint "eagle-import:DF11-10DP-2DSA")
      (libsource (lib "eagle-import") (part "DF11-10DP-2DSA(01)"))
    )
    (comp (ref "J48")
      (value "3-641215-2")
      (footprint "eagle-import:3-641215-2")
      (libsource (lib "eagle-import") (part "3-641215-2"))
    )
    (comp (ref "J49")
      (value "3-641215-2")
      (footprint "eagle-import:3-641215-2")
      (libsource (lib "eagle-import") (part "3-641215-2"))
    )
    (comp (ref "L15")
      (value "HI1812V101R-10")
      (footprint "eagle-import:L1812")
      (fields (field (name "MANUFACTURER") "Laird") (field (name "MFR_PN") "HI1812V101R-10"))
      (libsource (lib "eagle-import") (part "L1812"))
    )
    (comp (ref "L16")
      (value "HI1812V101R-10")
      (footprint "eagle-import:L1812")
      (fields (field (name "MANUFACTURER") "Laird") (field (name "MFR_PN") "HI1812V101R-10"))
      (libsource (lib "eagle-import") (part "L1812"))
    )
    (comp (ref "L17")
      (value "HI1206T500R-00")
      (footprint "eagle-import:1206")
      (libsource (lib "eagle-import") (part "L-1206"))
    )
    (comp (ref "Q24")
      (value "BSS138")
      (footprint "eagle-import:SOT23")
      (libsource (lib "eagle-import") (part "BSS138"))
    )
    (comp (ref "R198")
      (value "10")
      (footprint "eagle-import:R0603")
      (fields (field (name "MANUFACTURER") "Rohm"))
      (libsource (lib "eagle-import") (part "R-US_R0603"))
    )
    (comp (ref "R199")
      (value "0R")
      (footprint "eagle-import:R0603")
      (fields (field (name "MANUFACTURER") "Rohm"))
      (libsource (lib "eagle-import") (part "R-US_R0603"))
    )
    (comp (ref "R200")
      (value "1M")
      (footprint "eagle-import:R0603")
      (libsource (lib "eagle-import") (part "R-US_R0603"))
    )
    (comp (ref "R201")
      (value "1M")
      (footprint "eagle-import:R0603")
      (libsource (lib "eagle-import") (part "R-US_R0603"))
    )
    (comp (ref "R202")
      (value "DNP")
      (footprint "eagle-import:R0603")
      (libsource (lib "eagle-import") (part "R-US_R0603"))
    )
    (comp (ref "R203")
      (value "DNP")
      (footprint "eagle-import:R0603")
      (libsource (lib "eagle-import") (part "R-US_R0603"))
    )
    (comp (ref "R204")
      (value "1k")
      (footprint "eagle-import:R0603")
      (libsource (lib "eagle-import") (part "R-US_R0603"))
    )
    (comp (ref "R205")
      (value "100k")
      (footprint "eagle-import:R0603")
      (libsource (lib "eagle-import") (part "R-US_R0603"))
    )
    (comp (ref "R206")
      (value "33")
      (footprint "eagle-import:R0603")
      (libsource (lib "eagle-import") (part "R-US_R0603"))
    )
    (comp (ref "R207")
      (value "3.3k")
      (footprint "eagle-import:R0603")
      (libsource (lib "eagle-import") (part "R-US_R0603"))
    )
    (comp (ref "R208")
      (value "6.8k")
      (footprint "eagle-import:R0603")
      (libsource (lib "eagle-import") (part "R-US_R0603"))
    )
    (comp (ref "R209")
      (value "120k")
      (footprint "eagle-import:R0603")
      (libsource (lib "eagle-import") (part "R-US_R0603"))
    )
    (comp (ref "R210")
      (value "1M")
      (footprint "eagle-import:R0603")
      (libsource (lib "eagle-import") (part "R-US_R0603"))
    )
    (comp (ref "R211")
      (value "3.9k")
      (footprint "eagle-import:R0603")
      (libsource (lib "eagle-import") (part "R-US_R0603"))
    )
    (comp (ref "TP69")
      (value "P1-13")
      (footprint "eagle-import:P1-13@1")
      (libsource (lib "eagle-import") (part "P1-13"))
    )
    (comp (ref "U8")
      (value "TPA3111D1PWP")
      (footprint "eagle-import:TSSOP28_EP")
      (fields (field (name "MANUFACTURER") "TI"))
      (libsource (lib "eagle-import") (part "IC_TI_TPA3111D1PWP"))
    )
    (comp (ref "U9")
      (value "OPA322SAIDBVT")
      (footprint "eagle-import:SOT23-6")
      (fields (field (name "MANUFACTURER") "TI"))
      (libsource (lib "eagle-import") (part "IC_TI_OPA322SDBVAI"))
    )
    (comp (ref "B1")
      (value "3001/3.3V")
      (footprint "eagle-import:3001")
      (libsource (lib "eagle-import") (part "3001"))
    )
    (comp (ref "C1")
      (value "1u/10V")
      (footprint "eagle-import:0603")
      (libsource (lib "eagle-import") (part "C-0603"))
    )
    (comp (ref "C2")
      (value "0.1uF")
      (footprint "eagle-import:0603")
      (libsource (lib "eagle-import") (part "C-0603"))
    )
    (comp (ref "C3")
      (value "10uF/4V")
      (footprint "eagle-import:0603")
      (libsource (lib "eagle-import") (part "C-0603"))
    )
    (comp (ref "C4")
      (value "0.1uF")
      (footprint "eagle-import:0603")
      (libsource (lib "eagle-import") (part "C-0603"))
    )
    (comp (ref "C5")
      (value "0.1uF")
      (footprint "eagle-import:0603")
      (libsource (lib "eagle-import") (part "C-0603"))
    )
    (comp (ref "C6")
      (value "0.1uF")
      (footprint "eagle-import:0603")
      (libsource (lib "eagle-import") (part "C-0603"))
    )
    (comp (ref "C7")
      (value "10uF/4V")
      (footprint "eagle-import:0603")
      (libsource (lib "eagle-import") (part "C-0603"))
    )
    (comp (ref "C8")
      (value "1u/10V")
      (footprint "eagle-import:0603")
      (libsource (lib "eagle-import") (part "C-0603"))
    )
    (comp (ref "C9")
      (value "10uF/4V")
      (footprint "eagle-import:0603")
      (libsource (lib "eagle-import") (part "C-0603"))
    )
    (comp (ref "C10")
      (value "10uF/4V")
      (footprint "eagle-import:0603")
      (libsource (lib "eagle-import") (part "C-0603"))
    )
    (comp (ref "C11")
      (value "4.7uF/16V")
      (footprint "eagle-import:0805")
      (libsource (lib "eagle-import") (part "C-0805"))
    )
    (comp (ref "C12")
      (value "10nF")
      (footprint "eagle-import:0603")
      (libsource (lib "eagle-import") (part "C-0603"))
    )
    (comp (ref "C13")
      (value "10nF")
      (footprint "eagle-import:0603")
      (libsource (lib "eagle-import") (part "C-0603"))
    )
    (comp (ref "C14")
      (value "1u/6.3V")
      (footprint "eagle-import:0603")
      (libsource (lib "eagle-import") (part "C-0603"))
    )
    (comp (ref "C15")
      (value "1u/10V")
      (footprint "eagle-import:0603")
      (libsource (lib "eagle-import") (part "C-0603"))
    )
    (comp (ref "C16")
      (value "4.7uF/6.3V")
      (footprint "eagle-import:0603")
      (libsource (lib "eagle-import") (part "C-0603"))
    )
    (comp (ref "C17")
      (value "0.1uF")
      (footprint "eagle-import:0603")
      (libsource (lib "eagle-import") (part "C-0603"))
    )
    (comp (ref "C18")
      (value "18pF")
      (footprint "eagle-import:0603")
      (libsource (lib "eagle-import") (part "C-0603"))
    )
    (comp (ref "C19")
      (value "18pF")
      (footprint "eagle-import:0603")
      (libsource (lib "eagle-import") (part "C-0603"))
    )
    (comp (ref "C20")
      (value "4.7uF/6.3V")
      (footprint "eagle-import:0603")
      (libsource (lib "eagle-import") (part "C-0603"))
    )
    (comp (ref "C21")
      (value "0.1uF")
      (footprint "eagle-import:0603")
      (libsource (lib "eagle-import") (part "C-0603"))
    )
    (comp (ref "C22")
      (value "0.1uF")
      (footprint "eagle-import:0603")
      (libsource (lib "eagle-import") (part "C-0603"))
    )
    (comp (ref "C23")
      (value "10uF/4V")
      (footprint "eagle-import:0603")
      (libsource (lib "eagle-import") (part "C-0603"))
    )
    (comp (ref "C24")
      (value "1u/10V")
      (footprint "eagle-import:0603")
      (libsource (lib "eagle-import") (part "C-0603"))
    )
    (comp (ref "C25")
      (value "10nF")
      (footprint "eagle-import:0603")
      (libsource (lib "eagle-import") (part "C-0603"))
    )
    (comp (ref "C26")
      (value "10nF")
      (footprint "eagle-import:0603")
      (libsource (lib "eagle-import") (part "C-0603"))
    )
    (comp (ref "C27")
      (value "22u/16V")
      (footprint "eagle-import:1210")
      (libsource (lib "eagle-import") (part "C-1210"))
    )
    (comp (ref "C28")
      (value "1uF/16V")
      (footprint "eagle-import:0603")
      (libsource (lib "eagle-import") (part "C-0603"))
    )
    (comp (ref "C29")
      (value "10uF/4V")
      (footprint "eagle-import:0603")
      (libsource (lib "eagle-import") (part "C-0603"))
    )
    (comp (ref "C30")
      (value "0.1uF")
      (footprint "eagle-import:0603")
      (libsource (lib "eagle-import") (part "C-0603"))
    )
    (comp (ref "C31")
      (value "1uF/16V")
      (footprint "eagle-import:0603")
      (libsource (lib "eagle-import") (part "C-0603"))
    )
    (comp (ref "C32")
      (value "1uF/16V")
      (footprint "eagle-import:0603")
      (libsource (lib "eagle-import") (part "C-0603"))
    )
    (comp (ref "C33")
      (value "0.1uF")
      (footprint "eagle-import:0603")
      (libsource (lib "eagle-import") (part "C-0603"))
    )
    (comp (ref "C34")
      (value "dnp")
      (footprint "eagle-import:0603")
      (libsource (lib "eagle-import") (part "C-0603"))
    )
    (comp (ref "C35")
      (value "0.1uF")
      (footprint "eagle-import:0603")
      (libsource (lib "eagle-import") (part "C-0603"))
    )
    (comp (ref "C36")
      (value "10nF")
      (footprint "eagle-import:0603")
      (libsource (lib "eagle-import") (part "C-0603"))
    )
    (comp (ref "C38")
      (value "10uF/4V")
      (footprint "eagle-import:0603")
      (libsource (lib "eagle-import") (part "C-0603"))
    )
    (comp (ref "C47")
      (value "10nF")
      (footprint "eagle-import:0603")
      (libsource (lib "eagle-import") (part "C-0603"))
    )
    (comp (ref "C59")
      (value "10uF/4V")
      (footprint "eagle-import:0603")
      (libsource (lib "eagle-import") (part "C-0603"))
    )
    (comp (ref "D1")
      (value "BAS70-05E6327")
      (footprint "eagle-import:SOT-23")
      (libsource (lib "eagle-import") (part "BAS70-05E6327"))
    )
    (comp (ref "D2")
      (value "DNP")
      (footprint "eagle-import:SOD-123")
      (libsource (lib "eagle-import") (part "STPS0540Z"))
    )
    (comp (ref "D3")
      (value "STPS0540Z")
      (footprint "eagle-import:SOD-123")
      (libsource (lib "eagle-import") (part "STPS0540Z"))
    )
    (comp (ref "D4")
      (value "PMEG3030BEP")
      (footprint "eagle-import:SOD-128")
      (libsource (lib "eagle-import") (part "PMEG3030BEP"))
    )
    (comp (ref "FID1")
      (value "REF")
      (footprint "eagle-import:REF")
      (libsource (lib "eagle-import") (part "REF"))
    )
    (comp (ref "FID2")
      (value "REF")
      (footprint "eagle-import:REF")
      (libsource (lib "eagle-import") (part "REF"))
    )
    (comp (ref "FID3")
      (value "REF")
      (footprint "eagle-import:REF")
      (libsource (lib "eagle-import") (part "REF"))
    )
    (comp (ref "FID4")
      (value "REF")
      (footprint "eagle-import:REF")
      (libsource (lib "eagle-import") (part "REF"))
    )
    (comp (ref "H1")
      (value "STANDOFF_ELECTRICAL")
      (footprint "eagle-import:STANDOFF-ELECTRICAL")
      (libsource (lib "eagle-import") (part "STANDOFF_ELECTRICAL"))
    )
    (comp (ref "H2")
      (value "STANDOFF_ELECTRICAL")
      (footprint "eagle-import:STANDOFF-ELECTRICAL")
      (libsource (lib "eagle-import") (part "STANDOFF_ELECTRICAL"))
    )
    (comp (ref "H3")
      (value "STANDOFF_ELECTRICAL")
      (footprint "eagle-import:STANDOFF-ELECTRICAL")
      (libsource (lib "eagle-import") (part "STANDOFF_ELECTRICAL"))
    )
    (comp (ref "H4")
      (value "STANDOFF_ELECTRICAL")
      (footprint "eagle-import:STANDOFF-ELECTRICAL")
      (libsource (lib "eagle-import") (part "STANDOFF_ELECTRICAL"))
    )
    (comp (ref "H5")
      (value "STANDOFF_ELECTRICAL")
      (footprint "eagle-import:STANDOFF-ELECTRICAL")
      (libsource (lib "eagle-import") (part "STANDOFF_ELECTRICAL"))
    )
    (comp (ref "IC1")
      (value "ISL60002DIH325Z-TK")
      (footprint "eagle-import:SOT-23")
      (libsource (lib "eagle-import") (part "ISL60002DIH325Z-TK"))
    )
    (comp (ref "IC2")
      (value "SN65HVD12D")
      (footprint "eagle-import:SO08")
      (libsource (lib "eagle-import") (part "SN65HVD3082ED"))
    )
    (comp (ref "IC3")
      (value "PIC24FJ256GA110-I/PT")
      (footprint "eagle-import:SQFP-S-12X12-100")
      (libsource (lib "eagle-import") (part "PIC24FJ256GA110-I/PT"))
    )
    (comp (ref "IC4")
      (value "PIC10F200T-I/OT")
      (footprint "eagle-import:SOT23-6")
      (libsource (lib "eagle-import") (part "PIC10F200T-I/OT"))
    )
    (comp (ref "IC5")
      (value "LM75ADP")
      (footprint "eagle-import:TSSOP08-3")
      (libsource (lib "eagle-import") (part "LM75ADP"))
    )
    (comp (ref "IC6")
      (value "24LC32A-I/MS")
      (footprint "eagle-import:MSOP-08")
      (libsource (lib "eagle-import") (part "24-I/MS"))
    )
    (comp (ref "IC7")
      (value "PCF2123TS/1-T")
      (footprint "eagle-import:TSSOP014")
      (libsource (lib "eagle-import") (part "PCF2123TS/1-T"))
    )
    (comp (ref "IC8")
      (value "M25P16-VMN6P")
      (footprint "eagle-import:SO-08")
      (libsource (lib "eagle-import") (part "M25P16-VMN6P"))
    )
    (comp (ref "IC9")
      (value "LM3405AXMK/NOPB")
      (footprint "eagle-import:SOT23-6")
      (libsource (lib "eagle-import") (part "LM3405AXMK/NOPB"))
    )
    (comp (ref "J1")
      (value "DF11-10DP-2DSA(01)")
      (footprint "eagle-import:DF11-10DP-2DSA")
      (libsource (lib "eagle-import") (part "DF11-10DP-2DSA(01)"))
    )
    (comp (ref "J2")
      (value "MA07-1")
      (footprint "eagle-import:MA07-1")
      (libsource (lib "eagle-import") (part "MA07-1"))
    )
    (comp (ref "J3")
      (value "14011213102000")
      (footprint "eagle-import:14011213102000")
      (libsource (lib "eagle-import") (part "14011213102000"))
    )
    (comp (ref "J7")
      (value "SS-6566-NF")
      (footprint "eagle-import:SS-6566-NF")
      (libsource (lib "eagle-import") (part "SS-6566-NF"))
    )
    (comp (ref "J8")
      (value "TSW-108-07-G-D")
      (footprint "eagle-import:MA08-2")
      (libsource (lib "eagle-import") (part "MA08-2"))
    )
    (comp (ref "J9")
      (value "SS-6566-NF")
      (footprint "eagle-import:SS-6566-NF")
      (libsource (lib "eagle-import") (part "SS-6566-NF"))
    )
    (comp (ref "J10")
      (value "CCM03-3504LFT-NR")
      (footprint "eagle-import:CCM03-3504LFT-NR")
      (libsource (lib "eagle-import") (part "CCM03-3504LFT-NR"))
    )
    (comp (ref "J11")
      (value "MA05-1")
      (footprint "eagle-import:MA05-1")
      (libsource (lib "eagle-import") (part "MA05-1"))
    )
    (comp (ref "J12")
      (value "MA05-1")
      (footprint "eagle-import:MA05-1")
      (libsource (lib "eagle-import") (part "MA05-1"))
    )
    (comp (ref "J14")
      (value "3-641215-2")
      (footprint "eagle-import:3-641215-2")
      (libsource (lib "eagle-import") (part "3-641215-2"))
    )
    (comp (ref "J30")
      (value "22-11-2072")
      (footprint "eagle-import:HRXL-MAXSONAR-WRC-MB7387")
      (libsource (lib "eagle-import") (part "HRXL-MAXSONAR-WRC-MB7387"))
    )
    (comp (ref "JP1")
      (value "PINHD-1X8LOCK")
      (footprint "eagle-import:1X08-LOCK")
      (libsource (lib "eagle-import") (part "PINHD-1X8LOCK"))
    )
    (comp (ref "L1")
      (value "HI1206T500R-00")
      (footprint "eagle-import:1206")
      (libsource (lib "eagle-import") (part "L-1206"))
    )
    (comp (ref "L2")
      (value "HI1206T500R-00")
      (footprint "eagle-import:1206")
      (libsource (lib "eagle-import") (part "L-1206"))
    )
    (comp (ref "L3")
      (value "NRS8030T150MJGJ")
      (footprint "eagle-import:NRS8030")
      (libsource (lib "eagle-import") (part "NRS8030T150MJGJ"))
    )
    (comp (ref "Q2")
      (value "FDC6330L")
      (footprint "eagle-import:SSOT-6")
      (libsource (lib "eagle-import") (part "FDC6330L"))
    )
    (comp (ref "Q3")
      (value "SR3.3.TCT")
      (footprint "eagle-import:SOT-143")
      (libsource (lib "eagle-import") (part "SR05.TCT"))
    )
    (comp (ref "Q4")
      (value "7B-28.63636MAAJ-T")
      (footprint "eagle-import:7B")
      (libsource (lib "eagle-import") (part "7B-27.120MAAJ-T"))
    )
    (comp (ref "Q5")
      (value "FDC6330L")
      (footprint "eagle-import:SSOT-6")
      (libsource (lib "eagle-import") (part "FDC6324L"))
    )
    (comp (ref "Q6")
      (value "CM519 32.768KDZF-UT")
      (footprint "eagle-import:CM519")
      (libsource (lib "eagle-import") (part "CM519"))
    )
    (comp (ref "Q7")
      (value "SSM6P49NU,LFPZ")
      (footprint "eagle-import:MICRO_FET")
      (libsource (lib "eagle-import") (part "SSM6P49PZNU,LF"))
    )
    (comp (ref "R1")
      (value "300R")
      (footprint "eagle-import:0603")
      (libsource (lib "eagle-import") (part "R-0603"))
    )
    (comp (ref "R2")
      (value "100K")
      (footprint "eagle-import:0603-ARRAY")
      (libsource (lib "eagle-import") (part "EXB-38"))
    )
    (comp (ref "R3")
      (value "1M")
      (footprint "eagle-import:0603")
      (libsource (lib "eagle-import") (part "R-0603"))
    )
    (comp (ref "R4")
      (value "1M")
      (footprint "eagle-import:0603")
      (libsource (lib "eagle-import") (part "R-0603"))
    )
    (comp (ref "R5")
      (value "1M")
      (footprint "eagle-import:0603")
      (libsource (lib "eagle-import") (part "R-0603"))
    )
    (comp (ref "R6")
      (value "1M")
      (footprint "eagle-import:0603")
      (libsource (lib "eagle-import") (part "R-0603"))
    )
    (comp (ref "R7")
      (value "100K")
      (footprint "eagle-import:0603")
      (libsource (lib "eagle-import") (part "R-0603"))
    )
    (comp (ref "R8")
      (value "3.57K")
      (footprint "eagle-import:0603")
      (libsource (lib "eagle-import") (part "R-0603"))
    )
    (comp (ref "R9")
      (value "1M")
      (footprint "eagle-import:0603")
      (libsource (lib "eagle-import") (part "R-0603"))
    )
    (comp (ref "R10")
      (value "1M")
      (footprint "eagle-import:0603")
      (libsource (lib "eagle-import") (part "R-0603"))
    )
    (comp (ref "R11")
      (value "1M")
      (footprint "eagle-import:0603")
      (libsource (lib "eagle-import") (part "R-0603"))
    )
    (comp (ref "R12")
      (value "470K")
      (footprint "eagle-import:0603-0RTOP")
      (libsource (lib "eagle-import") (part "R-0603-0RTOP"))
    )
    (comp (ref "R13")
      (value "0R")
      (footprint "eagle-import:0603-0RTOP")
      (libsource (lib "eagle-import") (part "R-0603-0RTOP"))
    )
    (comp (ref "R14")
      (value "33K")
      (footprint "eagle-import:0603")
      (libsource (lib "eagle-import") (part "R-0603"))
    )
    (comp (ref "R15")
      (value "0R")
      (footprint "eagle-import:0603-0RTOP")
      (libsource (lib "eagle-import") (part "R-0603-0RTOP"))
    )
    (comp (ref "R16")
      (value "10K")
      (footprint "eagle-import:0603-0RTOP")
      (libsource (lib "eagle-import") (part "R-0603-0RTOP"))
    )
    (comp (ref "R17")
      (value "10K")
      (footprint "eagle-import:0603-0RTOP")
      (libsource (lib "eagle-import") (part "R-0603-0RTOP"))
    )
    (comp (ref "R18")
      (value "649R")
      (footprint "eagle-import:0603")
      (libsource (lib "eagle-import") (part "R-0603"))
    )
    (comp (ref "R19")
      (value "649R")
      (footprint "eagle-import:0603")
      (libsource (lib "eagle-import") (part "R-0603"))
    )
    (comp (ref "R20")
      (value "100K")
      (footprint "eagle-import:0603-ARRAY")
      (libsource (lib "eagle-import") (part "EXB-38"))
    )
    (comp (ref "R21")
      (value "100K")
      (footprint "eagle-import:0603-ARRAY")
      (libsource (lib "eagle-import") (part "EXB-38"))
    )
    (comp (ref "R22")
      (value "1M")
      (footprint "eagle-import:0603")
      (libsource (lib "eagle-import") (part "R-0603"))
    )
    (comp (ref "R23")
      (value "10K")
      (footprint "eagle-import:0603-0RTOP")
      (libsource (lib "eagle-import") (part "R-0603-0RTOP"))
    )
    (comp (ref "R24")
      (value "1M")
      (footprint "eagle-import:0603")
      (libsource (lib "eagle-import") (part "R-0603"))
    )
    (comp (ref "R25")
      (value "0.22R")
      (footprint "eagle-import:0603-0RTOP")
      (libsource (lib "eagle-import") (part "R-0603-0RTOP"))
    )
    (comp (ref "R27")
      (value "649R")
      (footprint "eagle-import:0603")
      (libsource (lib "eagle-import") (part "R-0603"))
    )
    (comp (ref "R28")
      (value "649R")
      (footprint "eagle-import:0603")
      (libsource (lib "eagle-import") (part "R-0603"))
    )
    (comp (ref "R29")
      (value "100K")
      (footprint "eagle-import:0603-ARRAY")
      (libsource (lib "eagle-import") (part "EXB-38"))
    )
    (comp (ref "R37")
      (value "300R")
      (footprint "eagle-import:0603")
      (libsource (lib "eagle-import") (part "R-0603"))
    )
    (comp (ref "TP1")
      (value "ROUND_SMD1MM")
      (footprint "eagle-import:SMD_ROUND_1MM")
      (libsource (lib "eagle-import") (part "ROUND_SMD1MM"))
    )
    (comp (ref "TP2")
      (value "ROUND_SMD1MM")
      (footprint "eagle-import:SMD_ROUND_1MM")
      (libsource (lib "eagle-import") (part "ROUND_SMD1MM"))
    )
    (comp (ref "TP3")
      (value "ROUND_SMD1MM")
      (footprint "eagle-import:SMD_ROUND_1MM")
      (libsource (lib "eagle-import") (part "ROUND_SMD1MM"))
    )
    (comp (ref "TP4")
      (value "ROUND_SMD1MM")
      (footprint "eagle-import:SMD_ROUND_1MM")
      (libsource (lib "eagle-import") (part "ROUND_SMD1MM"))
    )
    (comp (ref "TP5")
      (value "ROUND_SMD1MM")
      (footprint "eagle-import:SMD_ROUND_1MM")
      (libsource (lib "eagle-import") (part "ROUND_SMD1MM"))
    )
    (comp (ref "TP6")
      (value "ROUND_SMD1MM")
      (footprint "eagle-import:SMD_ROUND_1MM")
      (libsource (lib "eagle-import") (part "ROUND_SMD1MM"))
    )
    (comp (ref "TP7")
      (value "ROUND_SMD1MM")
      (footprint "eagle-import:SMD_ROUND_1MM")
      (libsource (lib "eagle-import") (part "ROUND_SMD1MM"))
    )
    (comp (ref "TP8")
      (value "ROUND_SMD1MM")
      (footprint "eagle-import:SMD_ROUND_1MM")
      (libsource (lib "eagle-import") (part "ROUND_SMD1MM"))
    )
    (comp (ref "TP9")
      (value "ROUND_SMD0.7MM")
      (footprint "eagle-import:SMD_ROUND_07MM")
      (libsource (lib "eagle-import") (part "ROUND_SMD0.7MM"))
    )
    (comp (ref "TP10")
      (value "ROUND_SMD1MM")
      (footprint "eagle-import:SMD_ROUND_1MM")
      (libsource (lib "eagle-import") (part "ROUND_SMD1MM"))
    )
    (comp (ref "TP11")
      (value "ROUND_SMD0.7MM")
      (footprint "eagle-import:SMD_ROUND_07MM")
      (libsource (lib "eagle-import") (part "ROUND_SMD0.7MM"))
    )
    (comp (ref "TP12")
      (value "TP_0812")
      (footprint "eagle-import:TP_0.8_1.2")
      (libsource (lib "eagle-import") (part "TP_0812"))
    )
    (comp (ref "U1")
      (value "LTC1955")
      (footprint "eagle-import:LFCSP_5X5_032")
      (libsource (lib "eagle-import") (part "LTC1955"))
    )
    (comp (ref "X1")
      (value "FH12-10S-0.5S1.00MM")
      (footprint "eagle-import:CON-FPC-1.0MM-10POS")
      (libsource (lib "eagle-import") (part "FH12-10S-0.5S1.00MM"))
    )
    (comp (ref "C37")
      (value "0.1uF")
      (footprint "eagle-import:0603")
      (libsource (lib "eagle-import") (part "C-0603"))
    )
    (comp (ref "C39")
      (value "10uF/4V")
      (footprint "eagle-import:0603")
      (libsource (lib "eagle-import") (part "C-0603"))
    )
    (comp (ref "C40")
      (value "0.1uF")
      (footprint "eagle-import:0603")
      (libsource (lib "eagle-import") (part "C-0603"))
    )
    (comp (ref "C41")
      (value "10uF/4V")
      (footprint "eagle-import:0603")
      (libsource (lib "eagle-import") (part "C-0603"))
    )
    (comp (ref "C42")
      (value "0.1uF")
      (footprint "eagle-import:0603")
      (libsource (lib "eagle-import") (part "C-0603"))
    )
    (comp (ref "C48")
      (value "10uF")
      (footprint "eagle-import:0603")
      (libsource (lib "eagle-import") (part "C-0603"))
    )
    (comp (ref "J15")
      (value "1990834")
      (footprint "eagle-import:1990834")
      (libsource (lib "eagle-import") (part "1990834"))
    )
    (comp (ref "J16")
      (value "1990737")
      (footprint "eagle-import:1990737")
      (libsource (lib "eagle-import") (part "1990737"))
    )
    (comp (ref "J17")
      (value "14011213102000")
      (footprint "eagle-import:14011213102000")
      (libsource (lib "eagle-import") (part "14011213102000"))
    )
    (comp (ref "J18")
      (value "14011213102000")
      (footprint "eagle-import:14011213102000")
      (libsource (lib "eagle-import") (part "14011213102000"))
    )
    (comp (ref "J19")
      (value "14011213102000")
      (footprint "eagle-import:14011213102000")
      (libsource (lib "eagle-import") (part "14011213102000"))
    )
    (comp (ref "R31")
      (value "10K")
      (footprint "eagle-import:0603")
      (libsource (lib "eagle-import") (part "R-0603"))
    )
    (comp (ref "R32")
      (value "10K")
      (footprint "eagle-import:0603")
      (libsource (lib "eagle-import") (part "R-0603"))
    )
    (comp (ref "R33")
      (value "4.7K")
      (footprint "eagle-import:0603")
      (libsource (lib "eagle-import") (part "R-0603"))
    )
    (comp (ref "R34")
      (value "1K")
      (footprint "eagle-import:0603")
      (libsource (lib "eagle-import") (part "R-0603"))
    )
    (comp (ref "R35")
      (value "3k")
      (footprint "eagle-import:0603")
      (libsource (lib "eagle-import") (part "R-0603"))
    )
    (comp (ref "R36")
      (value "1k")
      (footprint "eagle-import:0603")
      (libsource (lib "eagle-import") (part "R-0603"))
    )
    (comp (ref "R38")
      (value "1K")
      (footprint "eagle-import:0603")
      (libsource (lib "eagle-import") (part "R-0603"))
    )
    (comp (ref "R39")
      (value "1K")
      (footprint "eagle-import:0603")
      (libsource (lib "eagle-import") (part "R-0603"))
    )
    (comp (ref "U3")
      (value "ADS1015")
      (footprint "eagle-import:MSOP10")
      (libsource (lib "eagle-import") (part "ADS1015"))
    )
    (comp (ref "C43")
      (value "470uF/35-50V")
      (footprint "eagle-import:E5-13")
      (libsource (lib "eagle-import") (part "CPOL-USE5-13"))
    )
    (comp (ref "C44")
      (value "220uF, 16V, AL")
      (footprint "eagle-import:153CLV-0605")
      (libsource (lib "eagle-import") (part "CPOL-US153CLV-0605"))
    )
    (comp (ref "C122")
      (value "22uF,25V,1206")
      (footprint "eagle-import:C1206")
      (fields (field (name "MANUFACTURER") "Samsung"))
      (libsource (lib "eagle-import") (part "C-US-NP1206"))
    )
    (comp (ref "C123")
      (value "22uF,25V,1206")
      (footprint "eagle-import:C1206")
      (fields (field (name "MANUFACTURER") "Samsung"))
      (libsource (lib "eagle-import") (part "C-US-NP1206"))
    )
    (comp (ref "C124")
      (value "100pF,C0G")
      (footprint "eagle-import:C0603")
      (fields (field (name "MANUFACTURER") "Samsung"))
      (libsource (lib "eagle-import") (part "C-US-NP0603"))
    )
    (comp (ref "C125")
      (value "0.1uF")
      (footprint "eagle-import:C0603")
      (fields (field (name "MANUFACTURER") "Murata"))
      (libsource (lib "eagle-import") (part "C-US-NP0603"))
    )
    (comp (ref "C126")
      (value "0.1uF")
      (footprint "eagle-import:C0603")
      (fields (field (name "MANUFACTURER") "Murata"))
      (libsource (lib "eagle-import") (part "C-US-NP0603"))
    )
    (comp (ref "C127")
      (value "4.7uF/6.3V")
      (footprint "eagle-import:C0603")
      (fields (field (name "MANUFACTURER") "Samsung"))
      (libsource (lib "eagle-import") (part "C-US-NP0603"))
    )
    (comp (ref "C128")
      (value "22uF,25V,1206")
      (footprint "eagle-import:C1206")
      (fields (field (name "MANUFACTURER") "Samsung"))
      (libsource (lib "eagle-import") (part "C-US-NP1206"))
    )
    (comp (ref "C129")
      (value "22uF,25V,1206")
      (footprint "eagle-import:C1206")
      (fields (field (name "MANUFACTURER") "Samsung"))
      (libsource (lib "eagle-import") (part "C-US-NP1206"))
    )
    (comp (ref "C130")
      (value "22uF,25V,1206")
      (footprint "eagle-import:C1206")
      (fields (field (name "MANUFACTURER") "Samsung"))
      (libsource (lib "eagle-import") (part "C-US-NP1206"))
    )
    (comp (ref "C131")
      (value "130pF,C0G")
      (footprint "eagle-import:C0603")
      (fields (field (name "MANUFACTURER") "Samsung"))
      (libsource (lib "eagle-import") (part "C-US-NP0603"))
    )
    (comp (ref "C132")
      (value "0.1uF")
      (footprint "eagle-import:C0603")
      (fields (field (name "MANUFACTURER") "Murata"))
      (libsource (lib "eagle-import") (part "C-US-NP0603"))
    )
    (comp (ref "C133")
      (value "15nF")
      (footprint "eagle-import:C0603")
      (fields (field (name "MANUFACTURER") "Samsung"))
      (libsource (lib "eagle-import") (part "C-US-NP0603"))
    )
    (comp (ref "C134")
      (value "10nF")
      (footprint "eagle-import:0603")
      (libsource (lib "eagle-import") (part "C-0603"))
    )
    (comp (ref "C135")
      (value "10uF/35V")
      (footprint "eagle-import:1206")
      (libsource (lib "eagle-import") (part "C-1206"))
    )
    (comp (ref "C136")
      (value "22uF,25V,1206")
      (footprint "eagle-import:C1206")
      (fields (field (name "MANUFACTURER") "Samsung"))
      (libsource (lib "eagle-import") (part "C-US-NP1206"))
    )
    (comp (ref "C137")
      (value "22uF,25V,1206")
      (footprint "eagle-import:C1206")
      (fields (field (name "MANUFACTURER") "Samsung"))
      (libsource (lib "eagle-import") (part "C-US-NP1206"))
    )
    (comp (ref "C138")
      (value "100pF,C0G")
      (footprint "eagle-import:C0603")
      (fields (field (name "MANUFACTURER") "Samsung"))
      (libsource (lib "eagle-import") (part "C-US-NP0603"))
    )
    (comp (ref "C139")
      (value "0.1uF")
      (footprint "eagle-import:C0603")
      (fields (field (name "MANUFACTURER") "Murata"))
      (libsource (lib "eagle-import") (part "C-US-NP0603"))
    )
    (comp (ref "C140")
      (value "0.1uF")
      (footprint "eagle-import:C0603")
      (fields (field (name "MANUFACTURER") "Murata"))
      (libsource (lib "eagle-import") (part "C-US-NP0603"))
    )
    (comp (ref "C141")
      (value "4.7uF/6.3V")
      (footprint "eagle-import:C0603")
      (fields (field (name "MANUFACTURER") "Samsung"))
      (libsource (lib "eagle-import") (part "C-US-NP0603"))
    )
    (comp (ref "C142")
      (value "10uF/35V")
      (footprint "eagle-import:1206")
      (libsource (lib "eagle-import") (part "C-1206"))
    )
    (comp (ref "C143")
      (value "10uF,50V,1210")
      (footprint "eagle-import:C1210")
      (fields (field (name "MANUFACTURER") "Samsung"))
      (libsource (lib "eagle-import") (part "C-US-NP1210"))
    )
    (comp (ref "C144")
      (value "10uF,50V,1210")
      (footprint "eagle-import:C1210")
      (fields (field (name "MANUFACTURER") "Samsung"))
      (libsource (lib "eagle-import") (part "C-US-NP1210"))
    )
    (comp (ref "C145")
      (value "10uF,50V,1210")
      (footprint "eagle-import:C1210")
      (fields (field (name "MANUFACTURER") "Samsung"))
      (libsource (lib "eagle-import") (part "C-US-NP1210"))
    )
    (comp (ref "C146")
      (value "100pF")
      (footprint "eagle-import:C0603")
      (fields (field (name "MANUFACTURER") "Samsung"))
      (libsource (lib "eagle-import") (part "C-US-NP0603"))
    )
    (comp (ref "C147")
      (value "0.1uF")
      (footprint "eagle-import:C0603")
      (fields (field (name "MANUFACTURER") "Murata"))
      (libsource (lib "eagle-import") (part "C-US-NP0603"))
    )
    (comp (ref "C148")
      (value "10nF")
      (footprint "eagle-import:C0603")
      (fields (field (name "MANUFACTURER") "Samsung"))
      (libsource (lib "eagle-import") (part "C-US-NP0603"))
    )
    (comp (ref "C149")
      (value "22u/16V")
      (footprint "eagle-import:1210")
      (libsource (lib "eagle-import") (part "C-1210"))
    )
    (comp (ref "C150")
      (value "0.1uF")
      (footprint "eagle-import:0603")
      (libsource (lib "eagle-import") (part "C-0603"))
    )
    (comp (ref "C152")
      (value "22u/16V")
      (footprint "eagle-import:1210")
      (libsource (lib "eagle-import") (part "C-1210"))
    )
    (comp (ref "C153")
      (value "22u/16V")
      (footprint "eagle-import:1210")
      (libsource (lib "eagle-import") (part "C-1210"))
    )
    (comp (ref "C154")
      (value "0.1uF")
      (footprint "eagle-import:0603")
      (libsource (lib "eagle-import") (part "C-0603"))
    )
    (comp (ref "C155")
      (value "1nF")
      (footprint "eagle-import:0603")
      (libsource (lib "eagle-import") (part "C-0603"))
    )
    (comp (ref "C156")
      (value "TCJB157M006R0045")
      (footprint "eagle-import:3528-POL")
      (libsource (lib "eagle-import") (part "C-POL-3528"))
    )
    (comp (ref "C157")
      (value "47u/6.3V")
      (footprint "eagle-import:1210")
      (libsource (lib "eagle-import") (part "C-1210"))
    )
    (comp (ref "C158")
      (value "47u/6.3V")
      (footprint "eagle-import:1210")
      (libsource (lib "eagle-import") (part "C-1210"))
    )
    (comp (ref "C160")
      (value "15pF")
      (footprint "eagle-import:0603")
      (libsource (lib "eagle-import") (part "C-0603"))
    )
    (comp (ref "C163")
      (value "0.1uF")
      (footprint "eagle-import:0603")
      (libsource (lib "eagle-import") (part "C-0603"))
    )
    (comp (ref "C164")
      (value "330pF")
      (footprint "eagle-import:0603")
      (libsource (lib "eagle-import") (part "C-0603"))
    )
    (comp (ref "C187")
      (value "2mF/16V")
      (footprint "eagle-import:E7,5-18")
      (libsource (lib "eagle-import") (part "CPOL-USE7.5-18"))
    )
    (comp (ref "D20")
      (value "PMEG3030BEP")
      (footprint "eagle-import:SOD-128")
      (libsource (lib "eagle-import") (part "PMEG3030BEP"))
    )
    (comp (ref "D21")
      (value "SMAJ26A")
      (footprint "eagle-import:SMA")
      (libsource (lib "eagle-import") (part "SMAJ5.0A"))
    )
    (comp (ref "D22")
      (value "PMEG3030BEP")
      (footprint "eagle-import:SOD-128")
      (libsource (lib "eagle-import") (part "PMEG3030BEP"))
    )
    (comp (ref "D23")
      (value "LED-GR")
      (footprint "eagle-import:0805-POL")
      (libsource (lib "eagle-import") (part "LED-0805"))
    )
    (comp (ref "D24")
      (value "LED-GR")
      (footprint "eagle-import:0805-POL")
      (libsource (lib "eagle-import") (part "LED-0805"))
    )
    (comp (ref "D25")
      (value "SS14")
      (footprint "eagle-import:SMA")
      (libsource (lib "eagle-import") (part "SS14"))
    )
    (comp (ref "D26")
      (value "SS14")
      (footprint "eagle-import:SMA")
      (libsource (lib "eagle-import") (part "SS14"))
    )
    (comp (ref "D27")
      (value "SMLVT3V3")
      (footprint "eagle-import:SMA")
      (libsource (lib "eagle-import") (part "SMLVT3V3"))
    )
    (comp (ref "D28")
      (value "SMAJ5.0A")
      (footprint "eagle-import:SMA")
      (libsource (lib "eagle-import") (part "SMAJ5.0A"))
    )
    (comp (ref "D30")
      (value "PMEG3030BEP")
      (footprint "eagle-import:SOD-128")
      (libsource (lib "eagle-import") (part "PMEG3030BEP"))
    )
    (comp (ref "D31")
      (value "BAT54BRW-7F")
      (footprint "eagle-import:SOT-363")
      (libsource (lib "eagle-import") (part "BAT54BRW-7F"))
    )
    (comp (ref "D32")
      (value "P6SMB16A")
      (footprint "eagle-import:SMB")
      (libsource (lib "eagle-import") (part "P6SMB16A"))
    )
    (comp (ref "F3")
      (value "2920L250DR")
      (footprint "eagle-import:1812")
      (libsource (lib "eagle-import") (part "1812L014DR"))
    )
    (comp (ref "IC19")
      (value "MCP6022-I/ST")
      (footprint "eagle-import:TSSOP8")
      (libsource (lib "eagle-import") (part "MCP6022-I/ST"))
    )
    (comp (ref "IC21")
      (value "LTC1771EMS8")
      (footprint "eagle-import:MSOP-08")
      (libsource (lib "eagle-import") (part "LTC1771EMS8"))
    )
    (comp (ref "J45")
      (value "3-641215-4")
      (footprint "eagle-import:3-641215-4")
      (libsource (lib "eagle-import") (part "3-641215-4"))
    )
    (comp (ref "J50")
      (value "0039301040")
      (footprint "eagle-import:0039301040")
      (libsource (lib "eagle-import") (part "0039301040"))
    )
    (comp (ref "L11")
      (value "SER2013-472MLD")
      (footprint "eagle-import:L_SER20XX")
      (fields (field (name "MANUFACTURER") "Coilcraft"))
      (libsource (lib "eagle-import") (part "LSER20XX"))
    )
    (comp (ref "L12")
      (value "SRR1280-150M")
      (footprint "eagle-import:L_SRR1280")
      (fields (field (name "MANUFACTURER") "Bourns") (field (name "MFR_PN") "SRR1280-1x0M"))
      (libsource (lib "eagle-import") (part "LSRR1280"))
    )
    (comp (ref "L14")
      (value "CR75NP-220KC")
      (footprint "eagle-import:CR75")
      (libsource (lib "eagle-import") (part "CR75-330KC"))
    )
    (comp (ref "Q14")
      (value "MAX9938HEUK")
      (footprint "eagle-import:SOT23-5")
      (libsource (lib "eagle-import") (part "TSM9938HEUK+T"))
    )
    (comp (ref "Q15")
      (value "SI4564DY")
      (footprint "eagle-import:SO-08")
      (libsource (lib "eagle-import") (part "SI4564DY"))
    )
    (comp (ref "Q16")
      (value "CSD87331Q3D")
      (footprint "eagle-import:SON8_3.3X3.3_TI")
      (fields (field (name "MANUFACTURER") "TI") (field (name "MFR_PN") "CSD87331Q3D"))
      (libsource (lib "eagle-import") (part "TRANS_DUAL_NFET_HALF-BRQ3D"))
    )
    (comp (ref "Q18")
      (value "SI4564DY")
      (footprint "eagle-import:SO-08")
      (libsource (lib "eagle-import") (part "SI4564DY"))
    )
    (comp (ref "Q19")
      (value "CSD87331Q3D")
      (footprint "eagle-import:SON8_3.3X3.3_TI")
      (fields (field (name "MANUFACTURER") "TI") (field (name "MFR_PN") "CSD87331Q3D"))
      (libsource (lib "eagle-import") (part "TRANS_DUAL_NFET_HALF-BRQ3D"))
    )
    (comp (ref "Q20")
      (value "IPD30N06S2L-23")
      (footprint "eagle-import:TO252")
      (libsource (lib "eagle-import") (part "IPD30N06S2L-23"))
    )
    (comp (ref "Q21")
      (value "IPD30N06S2L-23")
      (footprint "eagle-import:TO252")
      (libsource (lib "eagle-import") (part "IPD30N06S2L-23"))
    )
    (comp (ref "Q23")
      (value "FDN352AP")
      (footprint "eagle-import:SOT-23")
      (libsource (lib "eagle-import") (part "FDN352AP"))
    )
    (comp (ref "R40")
      (value "0.025R")
      (footprint "eagle-import:0805")
      (libsource (lib "eagle-import") (part "R-0805"))
    )
    (comp (ref "R41")
      (value "0.025R")
      (footprint "eagle-import:0805")
      (libsource (lib "eagle-import") (part "R-0805"))
    )
    (comp (ref "R42")
      (value "0.025R")
      (footprint "eagle-import:0805")
      (libsource (lib "eagle-import") (part "R-0805"))
    )
    (comp (ref "R43")
      (value "0.025R")
      (footprint "eagle-import:0805")
      (libsource (lib "eagle-import") (part "R-0805"))
    )
    (comp (ref "R44")
      (value "0.025R")
      (footprint "eagle-import:0805")
      (libsource (lib "eagle-import") (part "R-0805"))
    )
    (comp (ref "R45")
      (value "470R")
      (footprint "eagle-import:0603")
      (libsource (lib "eagle-import") (part "R-0603"))
    )
    (comp (ref "R46")
      (value "470R")
      (footprint "eagle-import:0603")
      (libsource (lib "eagle-import") (part "R-0603"))
    )
    (comp (ref "R154")
      (value "0.025R")
      (footprint "eagle-import:0805")
      (libsource (lib "eagle-import") (part "R-0805"))
    )
    (comp (ref "R156")
      (value "1M")
      (footprint "eagle-import:R0603")
      (fields (field (name "MANUFACTURER") "Panasonic"))
      (libsource (lib "eagle-import") (part "R-US_R0603"))
    )
    (comp (ref "R157")
      (value "10")
      (footprint "eagle-import:R0603")
      (fields (field (name "MANUFACTURER") "Rohm"))
      (libsource (lib "eagle-import") (part "R-US_R0603"))
    )
    (comp (ref "R158")
      (value "10")
      (footprint "eagle-import:R0603")
      (fields (field (name "MANUFACTURER") "Rohm"))
      (libsource (lib "eagle-import") (part "R-US_R0603"))
    )
    (comp (ref "R159")
      (value "1M")
      (footprint "eagle-import:R0603")
      (fields (field (name "MANUFACTURER") "Panasonic"))
      (libsource (lib "eagle-import") (part "R-US_R0603"))
    )
    (comp (ref "R160")
      (value "178k,1%")
      (footprint "eagle-import:R0603")
      (fields (field (name "MANUFACTURER") "Panasonic"))
      (libsource (lib "eagle-import") (part "R-US_R0603"))
    )
    (comp (ref "R161")
      (value "0")
      (footprint "eagle-import:R0603")
      (fields (field (name "MANUFACTURER") "Panasonic"))
      (libsource (lib "eagle-import") (part "R-US_R0603"))
    )
    (comp (ref "R162")
      (value "10k")
      (footprint "eagle-import:R0603")
      (fields (field (name "MANUFACTURER") "Panasonic"))
      (libsource (lib "eagle-import") (part "R-US_R0603"))
    )
    (comp (ref "R163")
      (value "0")
      (footprint "eagle-import:R0603")
      (fields (field (name "MANUFACTURER") "Panasonic"))
      (libsource (lib "eagle-import") (part "R-US_R0603"))
    )
    (comp (ref "R164")
      (value "5.90k,1%")
      (footprint "eagle-import:R0603")
      (fields (field (name "MANUFACTURER") "Panasonic"))
      (libsource (lib "eagle-import") (part "R-US_R0603"))
    )
    (comp (ref "R165")
      (value "93.1k,1%")
      (footprint "eagle-import:R0603")
      (fields (field (name "MANUFACTURER") "Panasonic"))
      (libsource (lib "eagle-import") (part "R-US_R0603"))
    )
    (comp (ref "R166")
      (value "20.0k,1%")
      (footprint "eagle-import:R0603")
      (fields (field (name "MANUFACTURER") "Panasonic"))
      (libsource (lib "eagle-import") (part "R-US_R0603"))
    )
    (comp (ref "R167")
      (value "100k")
      (footprint "eagle-import:R0603")
      (fields (field (name "MANUFACTURER") "Panasonic"))
      (libsource (lib "eagle-import") (part "R-US_R0603"))
    )
    (comp (ref "R170")
      (value "1M")
      (footprint "eagle-import:0603")
      (libsource (lib "eagle-import") (part "R-0603"))
    )
    (comp (ref "R171")
      (value "10")
      (footprint "eagle-import:R0603")
      (fields (field (name "MANUFACTURER") "Rohm"))
      (libsource (lib "eagle-import") (part "R-US_R0603"))
    )
    (comp (ref "R172")
      (value "10")
      (footprint "eagle-import:R0603")
      (fields (field (name "MANUFACTURER") "Rohm"))
      (libsource (lib "eagle-import") (part "R-US_R0603"))
    )
    (comp (ref "R173")
      (value "1M")
      (footprint "eagle-import:0603")
      (libsource (lib "eagle-import") (part "R-0603"))
    )
    (comp (ref "R174")
      (value "1M")
      (footprint "eagle-import:0603")
      (libsource (lib "eagle-import") (part "R-0603"))
    )
    (comp (ref "R175")
      (value "3.3K")
      (footprint "eagle-import:0805")
      (libsource (lib "eagle-import") (part "R-0805"))
    )
    (comp (ref "R176")
      (value "3.3K")
      (footprint "eagle-import:0805")
      (libsource (lib "eagle-import") (part "R-0805"))
    )
    (comp (ref "R177")
      (value "178k,1%")
      (footprint "eagle-import:R0603")
      (fields (field (name "MANUFACTURER") "Panasonic"))
      (libsource (lib "eagle-import") (part "R-US_R0603"))
    )
    (comp (ref "R178")
      (value "0")
      (footprint "eagle-import:R0603")
      (fields (field (name "MANUFACTURER") "Panasonic"))
      (libsource (lib "eagle-import") (part "R-US_R0603"))
    )
    (comp (ref "R179")
      (value "10k")
      (footprint "eagle-import:R0603")
      (fields (field (name "MANUFACTURER") "Panasonic"))
      (libsource (lib "eagle-import") (part "R-US_R0603"))
    )
    (comp (ref "R180")
      (value "0")
      (footprint "eagle-import:R0603")
      (fields (field (name "MANUFACTURER") "Panasonic"))
      (libsource (lib "eagle-import") (part "R-US_R0603"))
    )
    (comp (ref "R181")
      (value "5.90k,1%")
      (footprint "eagle-import:R0603")
      (fields (field (name "MANUFACTURER") "Panasonic"))
      (libsource (lib "eagle-import") (part "R-US_R0603"))
    )
    (comp (ref "R182")
      (value "93.1k,1%")
      (footprint "eagle-import:R0603")
      (fields (field (name "MANUFACTURER") "Panasonic"))
      (libsource (lib "eagle-import") (part "R-US_R0603"))
    )
    (comp (ref "R183")
      (value "1M")
      (footprint "eagle-import:0603")
      (libsource (lib "eagle-import") (part "R-0603"))
    )
    (comp (ref "R184")
      (value "1M")
      (footprint "eagle-import:0603")
      (libsource (lib "eagle-import") (part "R-0603"))
    )
    (comp (ref "R185")
      (value "20.0k,1%")
      (footprint "eagle-import:R0603")
      (fields (field (name "MANUFACTURER") "Panasonic"))
      (libsource (lib "eagle-import") (part "R-US_R0603"))
    )
    (comp (ref "R186")
      (value "100k")
      (footprint "eagle-import:R0603")
      (fields (field (name "MANUFACTURER") "Panasonic"))
      (libsource (lib "eagle-import") (part "R-US_R0603"))
    )
    (comp (ref "R187")
      (value "47K")
      (footprint "eagle-import:0603")
      (libsource (lib "eagle-import") (part "R-0603"))
    )
    (comp (ref "R189")
      (value "0.047R")
      (footprint "eagle-import:0805")
      (libsource (lib "eagle-import") (part "R-0805"))
    )
    (comp (ref "R190")
      (value "47K")
      (footprint "eagle-import:0603")
      (libsource (lib "eagle-import") (part "R-0603"))
    )
    (comp (ref "R193")
      (value "10K")
      (footprint "eagle-import:0603")
      (libsource (lib "eagle-import") (part "R-0603"))
    )
    (comp (ref "R194")
      (value "3.09M")
      (footprint "eagle-import:0603")
      (libsource (lib "eagle-import") (part "R-0603"))
    )
    (comp (ref "R197")
      (value "1M")
      (footprint "eagle-import:0603")
      (libsource (lib "eagle-import") (part "R-0603"))
    )
    (comp (ref "TP61")
      (value "TPB1,27")
      (footprint "eagle-import:B1,27")
      (libsource (lib "eagle-import") (part "TPB1,27"))
    )
    (comp (ref "TP62")
      (value "TPB1,27")
      (footprint "eagle-import:B1,27")
      (libsource (lib "eagle-import") (part "TPB1,27"))
    )
    (comp (ref "TP63")
      (value "TPB1,27")
      (footprint "eagle-import:B1,27")
      (libsource (lib "eagle-import") (part "TPB1,27"))
    )
    (comp (ref "TP64")
      (value "TPB1,27")
      (footprint "eagle-import:B1,27")
      (libsource (lib "eagle-import") (part "TPB1,27"))
    )
    (comp (ref "TP65")
      (value "TPB1,27")
      (footprint "eagle-import:B1,27")
      (libsource (lib "eagle-import") (part "TPB1,27"))
    )
    (comp (ref "TP66")
      (value "TPB1,27")
      (footprint "eagle-import:B1,27")
      (libsource (lib "eagle-import") (part "TPB1,27"))
    )
    (comp (ref "TP67")
      (value "TPB1,27")
      (footprint "eagle-import:B1,27")
      (libsource (lib "eagle-import") (part "TPB1,27"))
    )
    (comp (ref "U2")
      (value "LE33")
      (footprint "eagle-import:LE33")
      (libsource (lib "eagle-import") (part "LE33"))
    )
    (comp (ref "U6")
      (value "TPS43061")
      (footprint "eagle-import:QFN16_3X3_EP")
      (fields (field (name "MANUFACTURER") "TI"))
      (libsource (lib "eagle-import") (part "IC_TI_TPS43061RTE"))
    )
    (comp (ref "U7")
      (value "TPS43061")
      (footprint "eagle-import:QFN16_3X3_EP")
      (fields (field (name "MANUFACTURER") "TI"))
      (libsource (lib "eagle-import") (part "IC_TI_TPS43061RTE"))
    )
  )
  (nets
    (net (code "1") (name "+3.3V") (class "Default")
      (node (ref "C1") (pin "1") (pinfunction "1_1") (pintype "passive"))
      (node (ref "C157") (pin "1") (pinfunction "1_1") (pintype "passive"))
      (node (ref "C16") (pin "2") (pinfunction "2_2") (pintype "passive"))
      (node (ref "C17") (pin "1") (pinfunction "1_1") (pintype "passive"))
      (node (ref "C2") (pin "1") (pinfunction "1_1") (pintype "passive"))
      (node (ref "C29") (pin "2") (pinfunction "2_2") (pintype "passive"))
      (node (ref "C5") (pin "1") (pinfunction "1_1") (pintype "passive"))
      (node (ref "C6") (pin "1") (pinfunction "1_1") (pintype "passive"))
      (node (ref "C8") (pin "1") (pinfunction "1_1") (pintype "passive"))
      (node (ref "C9") (pin "1") (pinfunction "1_1") (pintype "passive"))
      (node (ref "D1") (pin "2") (pinfunction "A2_2") (pintype "passive"))
      (node (ref "D27") (pin "+") (pinfunction "C_+") (pintype "passive"))
      (node (ref "D31") (pin "4") (pinfunction "K_4") (pintype "passive"))
      (node (ref "D31") (pin "5") (pinfunction "K_5") (pintype "passive"))
      (node (ref "IC3") (pin "16") (pinfunction "VDD16_16") (pintype "power_in"))
      (node (ref "IC3") (pin "2") (pinfunction "VDD2_2") (pintype "power_in"))
      (node (ref "IC3") (pin "37") (pinfunction "VDD37_37") (pintype "power_in"))
      (node (ref "IC3") (pin "46") (pinfunction "VDD46_46") (pintype "power_in"))
      (node (ref "IC3") (pin "62") (pinfunction "VDD62_62") (pintype "power_in"))
      (node (ref "IC3") (pin "86") (pinfunction "VDD86_86") (pintype "power_in"))
      (node (ref "J1") (pin "9") (pinfunction "9_9") (pintype "passive"))
      (node (ref "J11") (pin "2") (pinfunction "2_2") (pintype "passive"))
      (node (ref "J18") (pin "5") (pinfunction "5_5") (pintype "bidirectional"))
      (node (ref "J8") (pin "10") (pinfunction "10_10") (pintype "passive"))
      (node (ref "Q7") (pin "1") (pinfunction "S_1") (pintype "passive"))
      (node (ref "Q7") (pin "4") (pinfunction "S_4") (pintype "passive"))
      (node (ref "R1") (pin "2") (pinfunction "2_2") (pintype "passive"))
      (node (ref "R12") (pin "2") (pinfunction "2_2") (pintype "passive"))
      (node (ref "R14") (pin "2") (pinfunction "2_2") (pintype "passive"))
      (node (ref "R15") (pin "2") (pinfunction "2_2") (pintype "passive"))
      (node (ref "R167") (pin "2") (pinfunction "2_2") (pintype "passive"))
      (node (ref "R186") (pin "2") (pinfunction "2_2") (pintype "passive"))
      (node (ref "R187") (pin "2") (pinfunction "2_2") (pintype "passive"))
      (node (ref "R190") (pin "2") (pinfunction "2_2") (pintype "passive"))
      (node (ref "R2") (pin "7") (pinfunction "2_7") (pintype "passive"))
      (node (ref "R2") (pin "8") (pinfunction "2_8") (pintype "passive"))
      (node (ref "R37") (pin "2") (pinfunction "2_2") (pintype "passive"))
      (node (ref "TP64") (pin "TP") (pinfunction "TP_TP") (pintype "input"))
      (node (ref "TP9") (pin "P$1") (pinfunction "TP_P$1") (pintype "passive"))
      (node (ref "U1") (pin "1") (pinfunction "DVCC_1") (pintype "bidirectional"))
      (node (ref "U1") (pin "12") (pinfunction "SVBAT_12") (pintype "bidirectional"))
      (node (ref "U1") (pin "13") (pinfunction "PVBAT_13") (pintype "bidirectional"))
      (node (ref "U2") (pin "1") (pinfunction "VOUT_1") (pintype "bidirectional"))
    )
    (net (code "2") (name "+3.3V{slash}1") (class "Default")
      (node (ref "C22") (pin "1") (pinfunction "1_1") (pintype "passive"))
      (node (ref "C33") (pin "1") (pinfunction "1_1") (pintype "passive"))
      (node (ref "C37") (pin "1") (pinfunction "1_1") (pintype "passive"))
      (node (ref "C48") (pin "1") (pinfunction "1_1") (pintype "passive"))
      (node (ref "IC5") (pin "7") (pinfunction "A0_7") (pintype "input"))
      (node (ref "IC5") (pin "8") (pinfunction "VCC_8") (pintype "power_in"))
      (node (ref "IC6") (pin "8") (pinfunction "VCC_8") (pintype "power_in"))
      (node (ref "IC8") (pin "3") (pinfunction "/WP_3") (pintype "input"))
      (node (ref "IC8") (pin "7") (pinfunction "/HOLD_7") (pintype "input"))
      (node (ref "IC8") (pin "8") (pinfunction "VCC_8") (pintype "power_in"))
      (node (ref "J49") (pin "2") (pinfunction "2_2") (pintype "passive"))
      (node (ref "Q7") (pin "6") (pinfunction "D_6") (pintype "passive"))
      (node (ref "Q7") (pin "P1") (pinfunction "D1_P1") (pintype "passive"))
      (node (ref "R16") (pin "2") (pinfunction "2_2") (pintype "passive"))
      (node (ref "R17") (pin "2") (pinfunction "2_2") (pintype "passive"))
      (node (ref "R200") (pin "1") (pinfunction "1_1") (pintype "passive"))
      (node (ref "R201") (pin "1") (pinfunction "1_1") (pintype "passive"))
      (node (ref "R205") (pin "2") (pinfunction "2_2") (pintype "passive"))
      (node (ref "R206") (pin "2") (pinfunction "2_2") (pintype "passive"))
      (node (ref "R24") (pin "1") (pinfunction "1_1") (pintype "passive"))
      (node (ref "R31") (pin "2") (pinfunction "2_2") (pintype "passive"))
      (node (ref "R32") (pin "2") (pinfunction "2_2") (pintype "passive"))
      (node (ref "TP8") (pin "P$1") (pinfunction "TP_P$1") (pintype "passive"))
      (node (ref "U3") (pin "8") (pinfunction "VDD_8") (pintype "bidirectional"))
    )
    (net (code "3") (name "+3.3V{slash}2") (class "Default")
      (node (ref "C14") (pin "1") (pinfunction "1_1") (pintype "passive"))
      (node (ref "C35") (pin "2") (pinfunction "2_2") (pintype "passive"))
      (node (ref "IC2") (pin "8") (pinfunction "VCC_8") (pintype "power_in"))
      (node (ref "J18") (pin "10") (pinfunction "10_10") (pintype "bidirectional"))
      (node (ref "J2") (pin "2") (pinfunction "2_2") (pintype "passive"))
      (node (ref "J30") (pin "6") (pinfunction "VCC_6") (pintype "bidirectional"))
      (node (ref "JP1") (pin "2") (pinfunction "2_2") (pintype "passive"))
      (node (ref "Q7") (pin "3") (pinfunction "D_3") (pintype "passive"))
      (node (ref "Q7") (pin "P2") (pinfunction "D1_P2") (pintype "passive"))
      (node (ref "R11") (pin "2") (pinfunction "2_2") (pintype "passive"))
    )
    (net (code "4") (name "+5V") (class "Default")
      (node (ref "C149") (pin "1") (pinfunction "1_1") (pintype "passive"))
      (node (ref "C150") (pin "1") (pinfunction "1_1") (pintype "passive"))
      (node (ref "C156") (pin "1") (pinfunction "PIN+_1") (pintype "passive"))
      (node (ref "C158") (pin "1") (pinfunction "1_1") (pintype "passive"))
      (node (ref "C160") (pin "2") (pinfunction "2_2") (pintype "passive"))
      (node (ref "D28") (pin "+") (pinfunction "C_+") (pintype "passive"))
      (node (ref "J18") (pin "4") (pinfunction "4_4") (pintype "bidirectional"))
      (node (ref "L14") (pin "2") (pinfunction "2_2") (pintype "passive"))
      (node (ref "R194") (pin "1") (pinfunction "1_1") (pintype "passive"))
      (node (ref "TP65") (pin "TP") (pinfunction "TP_TP") (pintype "input"))
      (node (ref "U2") (pin "8") (pinfunction "VIN_8") (pintype "bidirectional"))
    )
    (net (code "5") (name "+SMB") (class "Default")
      (node (ref "C11") (pin "1") (pinfunction "1_1") (pintype "passive"))
      (node (ref "C135") (pin "1") (pinfunction "1_1") (pintype "passive"))
      (node (ref "C152") (pin "1") (pinfunction "1_1") (pintype "passive"))
      (node (ref "C153") (pin "1") (pinfunction "1_1") (pintype "passive"))
      (node (ref "C154") (pin "1") (pinfunction "1_1") (pintype "passive"))
      (node (ref "C155") (pin "1") (pinfunction "1_1") (pintype "passive"))
      (node (ref "C27") (pin "1") (pinfunction "1_1") (pintype "passive"))
      (node (ref "C28") (pin "1") (pinfunction "1_1") (pintype "passive"))
      (node (ref "D2") (pin "A") (pinfunction "A_A") (pintype "passive"))
      (node (ref "IC21") (pin "6") (pinfunction "VIN_6") (pintype "power_in"))
      (node (ref "IC21") (pin "8") (pinfunction "MODE_8") (pintype "input"))
      (node (ref "IC9") (pin "5") (pinfunction "VIN_5") (pintype "power_in"))
      (node (ref "J1") (pin "10") (pinfunction "10_10") (pintype "passive"))
      (node (ref "J18") (pin "2") (pinfunction "2_2") (pintype "bidirectional"))
      (node (ref "J7") (pin "2") (pinfunction "2_2") (pintype "passive"))
      (node (ref "J9") (pin "2") (pinfunction "2_2") (pintype "passive"))
      (node (ref "Q14") (pin "4") (pinfunction "VIN-_4") (pintype "input"))
      (node (ref "Q15") (pin "3") (pinfunction "S_3") (pintype "passive"))
      (node (ref "Q18") (pin "3") (pinfunction "S_3") (pintype "passive"))
      (node (ref "Q2") (pin "4") (pinfunction "Q2S_4") (pintype "bidirectional"))
      (node (ref "Q5") (pin "4") (pinfunction "Q2S_4") (pintype "bidirectional"))
      (node (ref "R154") (pin "2") (pinfunction "2_2") (pintype "passive"))
      (node (ref "R156") (pin "2") (pinfunction "2_2") (pintype "passive"))
      (node (ref "R170") (pin "1") (pinfunction "1_1") (pintype "passive"))
      (node (ref "R189") (pin "2") (pinfunction "2_2") (pintype "passive"))
      (node (ref "R20") (pin "6") (pinfunction "2_6") (pintype "passive"))
      (node (ref "R3") (pin "1") (pinfunction "1_1") (pintype "passive"))
      (node (ref "R40") (pin "2") (pinfunction "2_2") (pintype "passive"))
      (node (ref "R41") (pin "2") (pinfunction "2_2") (pintype "passive"))
    )
    (net (code "6") (name "+SMB_PRE") (class "Default")
      (node (ref "F3") (pin "1") (pinfunction "1_1") (pintype "passive"))
      (node (ref "J15") (pin "9") (pinfunction "9_9") (pintype "bidirectional"))
      (node (ref "J15") (pin "9A") (pinfunction "9_9A") (pintype "bidirectional"))
      (node (ref "J45") (pin "4") (pinfunction "4_4") (pintype "passive"))
    )
    (net (code "7") (name "3V3_AUD") (class "Default")
      (node (ref "C180") (pin "1") (pinfunction "1_1") (pintype "passive"))
      (node (ref "C181") (pin "1") (pinfunction "1_1") (pintype "passive"))
      (node (ref "C182") (pin "1") (pinfunction "1_1") (pintype "passive"))
      (node (ref "R206") (pin "1") (pinfunction "1_1") (pintype "passive"))
      (node (ref "R207") (pin "1") (pinfunction "1_1") (pintype "passive"))
      (node (ref "U9") (pin "6") (pinfunction "V+_6") (pintype "power_in"))
    )
    (net (code "8") (name "5V_ON") (class "Default")
      (node (ref "C163") (pin "1") (pinfunction "1_1") (pintype "passive"))
      (node (ref "IC21") (pin "1") (pinfunction "RUN/SS_1") (pintype "input"))
      (node (ref "IC3") (pin "92") (pinfunction "RA7/CN40_92") (pintype "bidirectional"))
    )
    (net (code "9") (name "18V_GND") (class "Default")
      (node (ref "C39") (pin "2") (pinfunction "2_2") (pintype "passive"))
      (node (ref "C40") (pin "1") (pinfunction "1_1") (pintype "passive"))
      (node (ref "R34") (pin "1") (pinfunction "1_1") (pintype "passive"))
      (node (ref "R39") (pin "1") (pinfunction "1_1") (pintype "passive"))
      (node (ref "U3") (pin "5") (pinfunction "AIN1_5") (pintype "bidirectional"))
    )
    (net (code "10") (name "18V_SENSE") (class "Default")
      (node (ref "J15") (pin "1") (pinfunction "1_1") (pintype "bidirectional"))
      (node (ref "J15") (pin "1A") (pinfunction "1_1A") (pintype "bidirectional"))
      (node (ref "J15") (pin "3") (pinfunction "3_3") (pintype "bidirectional"))
      (node (ref "J15") (pin "3A") (pinfunction "3_3A") (pintype "bidirectional"))
      (node (ref "R33") (pin "2") (pinfunction "2_2") (pintype "passive"))
    )
    (net (code "11") (name "A+") (class "Default")
      (node (ref "IC2") (pin "6") (pinfunction "A_6") (pintype "bidirectional"))
      (node (ref "L2") (pin "1") (pinfunction "1_1") (pintype "passive"))
      (node (ref "Q3") (pin "3") (pinfunction "3_3") (pintype "passive"))
      (node (ref "R11") (pin "1") (pinfunction "1_1") (pintype "passive"))
      (node (ref "R9") (pin "1") (pinfunction "1_1") (pintype "passive"))
    )
    (net (code "12") (name "A1") (class "Default")
      (node (ref "J7") (pin "3") (pinfunction "3_3") (pintype "passive"))
      (node (ref "J9") (pin "3") (pinfunction "3_3") (pintype "passive"))
      (node (ref "L2") (pin "2") (pinfunction "2_2") (pintype "passive"))
    )
    (net (code "13") (name "ACT_EN_B") (class "Default")
      (node (ref "IC3") (pin "54") (pinfunction "CN73/RPI44/RF7_54") (pintype "bidirectional"))
    )
    (net (code "14") (name "ACT_S1_B") (class "Default")
      (node (ref "IC3") (pin "52") (pinfunction "CN70/RP30/RF2_52") (pintype "bidirectional"))
      (node (ref "Q20") (pin "1") (pinfunction "G_1") (pintype "passive"))
      (node (ref "R183") (pin "1") (pinfunction "1_1") (pintype "passive"))
    )
    (net (code "15") (name "ACT_S2_B") (class "Default")
      (node (ref "IC3") (pin "53") (pinfunction "CN74/RP15/RF8_53") (pintype "bidirectional"))
      (node (ref "Q21") (pin "1") (pinfunction "G_1") (pintype "passive"))
      (node (ref "R184") (pin "1") (pinfunction "1_1") (pintype "passive"))
    )
    (net (code "16") (name "ACT_S3_B") (class "Default")
      (node (ref "IC3") (pin "88") (pinfunction "CN69/RF1_88") (pintype "bidirectional"))
    )
    (net (code "17") (name "ACT_S4_B") (class "Default")
      (node (ref "IC3") (pin "49") (pinfunction "CN17/RP10/RF4_49") (pintype "bidirectional"))
    )
    (net (code "18") (name "AGND") (class "Default")
      (node (ref "C165") (pin "2") (pinfunction "2_2") (pintype "passive"))
      (node (ref "C166") (pin "2") (pinfunction "2_2") (pintype "passive"))
      (node (ref "C167") (pin "2") (pinfunction "2_2") (pintype "passive"))
      (node (ref "C168") (pin "2") (pinfunction "2_2") (pintype "passive"))
      (node (ref "C169") (pin "2") (pinfunction "2_2") (pintype "passive"))
      (node (ref "C170") (pin "2") (pinfunction "2_2") (pintype "passive"))
      (node (ref "C171") (pin "2") (pinfunction "2_2") (pintype "passive"))
      (node (ref "C172") (pin "2") (pinfunction "2_2") (pintype "passive"))
      (node (ref "C176") (pin "2") (pinfunction "2_2") (pintype "passive"))
      (node (ref "C177") (pin "1") (pinfunction "1_1") (pintype "passive"))
      (node (ref "C179") (pin "2") (pinfunction "2_2") (pintype "passive"))
      (node (ref "C180") (pin "2") (pinfunction "2_2") (pintype "passive"))
      (node (ref "C181") (pin "2") (pinfunction "2_2") (pintype "passive"))
      (node (ref "C182") (pin "2") (pinfunction "2_2") (pintype "passive"))
      (node (ref "J17") (pin "1") (pinfunction "1_1") (pintype "bidirectional"))
      (node (ref "J17") (pin "12") (pinfunction "12_12") (pintype "bidirectional"))
      (node (ref "J17") (pin "3") (pinfunction "3_3") (pintype "bidirectional"))
      (node (ref "J17") (pin "6") (pinfunction "6_6") (pintype "bidirectional"))
      (node (ref "J17") (pin "9") (pinfunction "9_9") (pintype "bidirectional"))
      (node (ref "J47") (pin "3") (pinfunction "3_3") (pintype "passive"))
      (node (ref "J47") (pin "4") (pinfunction "4_4") (pintype "passive"))
      (node (ref "J48") (pin "1") (pinfunction "1_1") (pintype "passive"))
      (node (ref "L17") (pin "2") (pinfunction "2_2") (pintype "passive"))
      (node (ref "Q24") (pin "2") (pinfunction "S_2") (pintype "passive"))
      (node (ref "R202") (pin "2") (pinfunction "2_2") (pintype "passive"))
      (node (ref "R203") (pin "2") (pinfunction "2_2") (pintype "passive"))
      (node (ref "R210") (pin "2") (pinfunction "2_2") (pintype "passive"))
      (node (ref "R211") (pin "2") (pinfunction "2_2") (pintype "passive"))
      (node (ref "U8") (pin "19") (pinfunction "PGND_19") (pintype "power_in"))
      (node (ref "U8") (pin "24") (pinfunction "PGND_24") (pintype "power_in"))
      (node (ref "U8") (pin "3") (pinfunction "GND_3") (pintype "power_in"))
      (node (ref "U8") (pin "4") (pinfunction "GND_4") (pintype "power_in"))
      (node (ref "U8") (pin "8") (pinfunction "AGND_8") (pintype "power_in"))
      (node (ref "U8") (pin "EP") (pinfunction "EP_EP") (pintype "power_in"))
      (node (ref "U9") (pin "2") (pinfunction "V-_2") (pintype "power_in"))
    )
    (net (code "19") (name "AUD_AMP_FAULT#") (class "Default")
      (node (ref "R204") (pin "1") (pinfunction "1_1") (pintype "passive"))
      (node (ref "R205") (pin "1") (pinfunction "1_1") (pintype "passive"))
      (node (ref "U8") (pin "1") (pinfunction "~{SD}_1") (pintype "input"))
      (node (ref "U8") (pin "2") (pinfunction "~{FAULT}_2") (pintype "output"))
    )
    (net (code "20") (name "AUD_AMP_G0") (class "Default")
      (node (ref "IC3") (pin "41") (pinfunction "RB12/AN12/CN30_41") (pintype "bidirectional"))
      (node (ref "R200") (pin "2") (pinfunction "2_2") (pintype "passive"))
      (node (ref "R202") (pin "1") (pinfunction "1_1") (pintype "passive"))
      (node (ref "TP4") (pin "P$1") (pinfunction "TP_P$1") (pintype "passive"))
      (node (ref "U8") (pin "5") (pinfunction "GAIN0_5") (pintype "input"))
    )
    (net (code "21") (name "AUD_AMP_G1") (class "Default")
      (node (ref "IC3") (pin "42") (pinfunction "RB13/AN13/CN31_42") (pintype "bidirectional"))
      (node (ref "R201") (pin "2") (pinfunction "2_2") (pintype "passive"))
      (node (ref "R203") (pin "1") (pinfunction "1_1") (pintype "passive"))
      (node (ref "TP5") (pin "P$1") (pinfunction "TP_P$1") (pintype "passive"))
      (node (ref "U8") (pin "6") (pinfunction "GAIN1_6") (pintype "input"))
    )
    (net (code "22") (name "AUD_AMP_INN") (class "Default")
      (node (ref "C177") (pin "2") (pinfunction "2_2") (pintype "passive"))
      (node (ref "U8") (pin "11") (pinfunction "INN_11") (pintype "input"))
    )
    (net (code "23") (name "AUD_AMP_INP") (class "Default")
      (node (ref "C174") (pin "2") (pinfunction "2_2") (pintype "passive"))
      (node (ref "C175") (pin "2") (pinfunction "2_2") (pintype "passive"))
      (node (ref "U8") (pin "12") (pinfunction "INP_12") (pintype "input"))
    )
    (net (code "24") (name "AUD_BSN") (class "Default")
      (node (ref "C178") (pin "1") (pinfunction "1_1") (pintype "passive"))
      (node (ref "U8") (pin "22") (pinfunction "BSN_22") (pintype "input"))
      (node (ref "U8") (pin "26") (pinfunction "BSN_26") (pintype "input"))
    )
    (net (code "25") (name "AUD_BSP") (class "Default")
      (node (ref "C173") (pin "1") (pinfunction "1_1") (pintype "passive"))
      (node (ref "U8") (pin "17") (pinfunction "BSP_17") (pintype "input"))
      (node (ref "U8") (pin "21") (pinfunction "BSP_21") (pintype "input"))
    )
    (net (code "26") (name "AUD_GVDD") (class "Default")
      (node (ref "C172") (pin "1") (pinfunction "1_1") (pintype "passive"))
      (node (ref "U8") (pin "10") (pinfunction "PLIMIT_10") (pintype "input"))
      (node (ref "U8") (pin "9") (pinfunction "GVDD_9") (pintype "output"))
    )
    (net (code "27") (name "B-") (class "Default")
      (node (ref "IC2") (pin "7") (pinfunction "B_7") (pintype "bidirectional"))
      (node (ref "L1") (pin "1") (pinfunction "1_1") (pintype "passive"))
      (node (ref "Q3") (pin "2") (pinfunction "2_2") (pintype "passive"))
      (node (ref "R10") (pin "2") (pinfunction "2_2") (pintype "passive"))
      (node (ref "R9") (pin "2") (pinfunction "2_2") (pintype "passive"))
    )
    (net (code "28") (name "B1") (class "Default")
      (node (ref "J7") (pin "4") (pinfunction "4_4") (pintype "passive"))
      (node (ref "J9") (pin "4") (pinfunction "4_4") (pintype "passive"))
      (node (ref "L1") (pin "2") (pinfunction "2_2") (pintype "passive"))
    )
    (net (code "29") (name "B12_BOOT") (class "Default")
      (node (ref "C126") (pin "1") (pinfunction "1_1") (pintype "passive"))
      (node (ref "U6") (pin "11") (pinfunction "BOOT_11") (pintype "passive"))
    )
    (net (code "30") (name "B12_COMP") (class "Default")
      (node (ref "C131") (pin "1") (pinfunction "1_1") (pintype "passive"))
      (node (ref "R164") (pin "2") (pinfunction "2_2") (pintype "passive"))
      (node (ref "U6") (pin "3") (pinfunction "COMP_3") (pintype "passive"))
    )
    (net (code "31") (name "B12_FB") (class "Default")
      (node (ref "R160") (pin "1") (pinfunction "1_1") (pintype "passive"))
      (node (ref "R166") (pin "2") (pinfunction "2_2") (pintype "passive"))
      (node (ref "U6") (pin "4") (pinfunction "FB_4") (pintype "input"))
    )
    (net (code "32") (name "B12_FEED") (class "Default")
      (node (ref "L11") (pin "2") (pinfunction "2_2") (pintype "passive"))
      (node (ref "R158") (pin "2") (pinfunction "2_2") (pintype "passive"))
      (node (ref "R42") (pin "2") (pinfunction "2_2") (pintype "passive"))
      (node (ref "R43") (pin "2") (pinfunction "2_2") (pintype "passive"))
    )
    (net (code "33") (name "B12_HDRV") (class "Default")
      (node (ref "R161") (pin "2") (pinfunction "2_2") (pintype "passive"))
      (node (ref "U6") (pin "13") (pinfunction "HDRV_13") (pintype "output"))
    )
    (net (code "34") (name "B12_HG") (class "Default")
      (node (ref "Q16") (pin "3") (pinfunction "TG_3") (pintype "passive"))
      (node (ref "R161") (pin "1") (pinfunction "1_1") (pintype "passive"))
    )
    (net (code "35") (name "B12_ISNS+") (class "Default")
      (node (ref "C124") (pin "1") (pinfunction "1_1") (pintype "passive"))
      (node (ref "R157") (pin "1") (pinfunction "1_1") (pintype "passive"))
      (node (ref "U6") (pin "6") (pinfunction "ISNS+_6") (pintype "input"))
    )
    (net (code "36") (name "B12_ISNS-") (class "Default")
      (node (ref "C124") (pin "2") (pinfunction "2_2") (pintype "passive"))
      (node (ref "R158") (pin "1") (pinfunction "1_1") (pintype "passive"))
      (node (ref "U6") (pin "5") (pinfunction "ISNS-_5") (pintype "input"))
    )
    (net (code "37") (name "B12_L") (class "Default")
      (node (ref "D20") (pin "A") (pinfunction "A_A") (pintype "passive"))
      (node (ref "L11") (pin "1") (pinfunction "1_1") (pintype "passive"))
      (node (ref "Q16") (pin "6") (pinfunction "VSW_6") (pintype "passive"))
      (node (ref "Q16") (pin "7") (pinfunction "VSW_7") (pintype "passive"))
      (node (ref "Q16") (pin "8") (pinfunction "VSW_8") (pintype "passive"))
    )
    (net (code "38") (name "B12_LDRV") (class "Default")
      (node (ref "R163") (pin "2") (pinfunction "2_2") (pintype "passive"))
      (node (ref "U6") (pin "8") (pinfunction "LDRV_8") (pintype "output"))
    )
    (net (code "39") (name "B12_LG") (class "Default")
      (node (ref "Q16") (pin "5") (pinfunction "BG_5") (pintype "passive"))
      (node (ref "R163") (pin "1") (pinfunction "1_1") (pintype "passive"))
    )
    (net (code "40") (name "B12_PG") (class "Default")
      (node (ref "IC3") (pin "69") (pinfunction "CN54/RP4/RD9_69") (pintype "bidirectional"))
      (node (ref "R167") (pin "1") (pinfunction "1_1") (pintype "passive"))
      (node (ref "U6") (pin "14") (pinfunction "PGOOD_14") (pintype "open_collector"))
    )
    (net (code "41") (name "B12_RC") (class "Default")
      (node (ref "C133") (pin "1") (pinfunction "1_1") (pintype "passive"))
      (node (ref "R164") (pin "1") (pinfunction "1_1") (pintype "passive"))
    )
    (net (code "42") (name "B12_RT") (class "Default")
      (node (ref "R165") (pin "2") (pinfunction "2_2") (pintype "passive"))
      (node (ref "U6") (pin "1") (pinfunction "RT/CLK_1") (pintype "passive"))
    )
    (net (code "43") (name "B12_SS") (class "Default")
      (node (ref "C132") (pin "1") (pinfunction "1_1") (pintype "passive"))
      (node (ref "U6") (pin "2") (pinfunction "SS_2") (pintype "passive"))
    )
    (net (code "44") (name "B12_SW") (class "Default")
      (node (ref "C126") (pin "2") (pinfunction "2_2") (pintype "passive"))
      (node (ref "Q16") (pin "4") (pinfunction "TGR_4") (pintype "passive"))
      (node (ref "U6") (pin "12") (pinfunction "SW_12") (pintype "output"))
    )
    (net (code "45") (name "B12_VCC") (class "Default")
      (node (ref "C127") (pin "1") (pinfunction "1_1") (pintype "passive"))
      (node (ref "U6") (pin "10") (pinfunction "VCC_10") (pintype "output"))
    )
    (net (code "46") (name "BAT_GND") (class "Default")
      (node (ref "C41") (pin "2") (pinfunction "2_2") (pintype "passive"))
      (node (ref "C42") (pin "1") (pinfunction "1_1") (pintype "passive"))
      (node (ref "R36") (pin "1") (pinfunction "1_1") (pintype "passive"))
      (node (ref "R38") (pin "1") (pinfunction "1_1") (pintype "passive"))
      (node (ref "U3") (pin "7") (pinfunction "AIN3_7") (pintype "bidirectional"))
    )
    (net (code "47") (name "BAT_SENSE") (class "Default")
      (node (ref "J15") (pin "5") (pinfunction "5_5") (pintype "bidirectional"))
      (node (ref "J15") (pin "5A") (pinfunction "5_5A") (pintype "bidirectional"))
      (node (ref "J15") (pin "7") (pinfunction "7_7") (pintype "bidirectional"))
      (node (ref "J15") (pin "7A") (pinfunction "7_7A") (pintype "bidirectional"))
      (node (ref "R35") (pin "2") (pinfunction "2_2") (pintype "passive"))
    )
    (net (code "48") (name "BTN_1") (class "Default")
      (node (ref "IC4") (pin "1") (pinfunction "GP0/PGD_1") (pintype "bidirectional"))
      (node (ref "J12") (pin "4") (pinfunction "4_4") (pintype "passive"))
      (node (ref "J19") (pin "10") (pinfunction "10_10") (pintype "bidirectional"))
      (node (ref "R2") (pin "2") (pinfunction "1_2") (pintype "passive"))
      (node (ref "R2") (pin "3") (pinfunction "1_3") (pintype "passive"))
    )
    (net (code "49") (name "BTN_1PIN_B") (class "Default")
      (node (ref "C12") (pin "1") (pinfunction "1_1") (pintype "passive"))
      (node (ref "IC3") (pin "90") (pinfunction "RG0/CN77_90") (pintype "bidirectional"))
      (node (ref "R2") (pin "6") (pinfunction "2_6") (pintype "passive"))
    )
    (net (code "50") (name "BTN_2") (class "Default")
      (node (ref "IC4") (pin "3") (pinfunction "GP1/PGC_3") (pintype "bidirectional"))
      (node (ref "J12") (pin "5") (pinfunction "5_5") (pintype "passive"))
      (node (ref "J19") (pin "12") (pinfunction "12_12") (pintype "bidirectional"))
      (node (ref "R2") (pin "1") (pinfunction "1_1") (pintype "passive"))
      (node (ref "R2") (pin "4") (pinfunction "1_4") (pintype "passive"))
    )
    (net (code "51") (name "BTN_2PIN_B") (class "Default")
      (node (ref "C13") (pin "1") (pinfunction "1_1") (pintype "passive"))
      (node (ref "IC3") (pin "89") (pinfunction "RG1/CN78_89") (pintype "bidirectional"))
      (node (ref "R2") (pin "5") (pinfunction "2_5") (pintype "passive"))
    )
    (net (code "52") (name "CL_IRQ") (class "Default")
      (node (ref "IC3") (pin "20") (pinfunction "RB5/AN5/CN7/RP18_20") (pintype "bidirectional"))
      (node (ref "J1") (pin "4") (pinfunction "4_4") (pintype "passive"))
    )
    (net (code "53") (name "CM_RST") (class "Default")
      (node (ref "IC3") (pin "98") (pinfunction "CN60/RE2_98") (pintype "bidirectional"))
    )
    (net (code "54") (name "CON_LED") (class "Default")
      (node (ref "IC3") (pin "40") (pinfunction "CN75/RPI32/RF12_40") (pintype "bidirectional"))
      (node (ref "JP1") (pin "6") (pinfunction "6_6") (pintype "passive"))
    )
    (net (code "55") (name "DCDC_12V_EN") (class "Default")
      (node (ref "IC3") (pin "84") (pinfunction "CN16/RD7_84") (pintype "bidirectional"))
      (node (ref "Q15") (pin "2") (pinfunction "G_2") (pintype "passive"))
      (node (ref "R162") (pin "2") (pinfunction "2_2") (pintype "passive"))
      (node (ref "U6") (pin "15") (pinfunction "EN_15") (pintype "input"))
    )
    (net (code "56") (name "DGND") (class "Default")
      (node (ref "B1") (pin "-") (pinfunction "-_-") (pintype "passive"))
      (node (ref "C1") (pin "2") (pinfunction "2_2") (pintype "passive"))
      (node (ref "C10") (pin "1") (pinfunction "1_1") (pintype "passive"))
      (node (ref "C11") (pin "2") (pinfunction "2_2") (pintype "passive"))
      (node (ref "C114") (pin "1") (pinfunction "1_1") (pintype "passive"))
      (node (ref "C115") (pin "1") (pinfunction "1_1") (pintype "passive"))
      (node (ref "C12") (pin "2") (pinfunction "2_2") (pintype "passive"))
      (node (ref "C121") (pin "1") (pinfunction "1_1") (pintype "passive"))
      (node (ref "C122") (pin "2") (pinfunction "2_2") (pintype "passive"))
      (node (ref "C123") (pin "2") (pinfunction "2_2") (pintype "passive"))
      (node (ref "C125") (pin "2") (pinfunction "2_2") (pintype "passive"))
      (node (ref "C127") (pin "2") (pinfunction "2_2") (pintype "passive"))
      (node (ref "C128") (pin "2") (pinfunction "2_2") (pintype "passive"))
      (node (ref "C129") (pin "2") (pinfunction "2_2") (pintype "passive"))
      (node (ref "C13") (pin "2") (pinfunction "2_2") (pintype "passive"))
      (node (ref "C130") (pin "2") (pinfunction "2_2") (pintype "passive"))
      (node (ref "C131") (pin "2") (pinfunction "2_2") (pintype "passive"))
      (node (ref "C132") (pin "2") (pinfunction "2_2") (pintype "passive"))
      (node (ref "C133") (pin "2") (pinfunction "2_2") (pintype "passive"))
      (node (ref "C134") (pin "2") (pinfunction "2_2") (pintype "passive"))
      (node (ref "C135") (pin "2") (pinfunction "2_2") (pintype "passive"))
      (node (ref "C136") (pin "2") (pinfunction "2_2") (pintype "passive"))
      (node (ref "C137") (pin "2") (pinfunction "2_2") (pintype "passive"))
      (node (ref "C139") (pin "2") (pinfunction "2_2") (pintype "passive"))
      (node (ref "C14") (pin "2") (pinfunction "2_2") (pintype "passive"))
      (node (ref "C141") (pin "2") (pinfunction "2_2") (pintype "passive"))
      (node (ref "C142") (pin "2") (pinfunction "2_2") (pintype "passive"))
      (node (ref "C143") (pin "2") (pinfunction "2_2") (pintype "passive"))
      (node (ref "C144") (pin "2") (pinfunction "2_2") (pintype "passive"))
      (node (ref "C145") (pin "2") (pinfunction "2_2") (pintype "passive"))
      (node (ref "C146") (pin "2") (pinfunction "2_2") (pintype "passive"))
      (node (ref "C147") (pin "2") (pinfunction "2_2") (pintype "passive"))
      (node (ref "C148") (pin "2") (pinfunction "2_2") (pintype "passive"))
      (node (ref "C149") (pin "2") (pinfunction "2_2") (pintype "passive"))
      (node (ref "C150") (pin "2") (pinfunction "2_2") (pintype "passive"))
      (node (ref "C152") (pin "2") (pinfunction "2_2") (pintype "passive"))
      (node (ref "C153") (pin "2") (pinfunction "2_2") (pintype "passive"))
      (node (ref "C154") (pin "2") (pinfunction "2_2") (pintype "passive"))
      (node (ref "C156") (pin "2") (pinfunction "PIN-_2") (pintype "passive"))
      (node (ref "C157") (pin "2") (pinfunction "2_2") (pintype "passive"))
      (node (ref "C158") (pin "2") (pinfunction "2_2") (pintype "passive"))
      (node (ref "C16") (pin "1") (pinfunction "1_1") (pintype "passive"))
      (node (ref "C163") (pin "2") (pinfunction "2_2") (pintype "passive"))
      (node (ref "C164") (pin "2") (pinfunction "2_2") (pintype "passive"))
      (node (ref "C17") (pin "2") (pinfunction "2_2") (pintype "passive"))
      (node (ref "C18") (pin "1") (pinfunction "1_1") (pintype "passive"))
      (node (ref "C187") (pin "-") (pinfunction "-_-") (pintype "passive"))
      (node (ref "C19") (pin "1") (pinfunction "1_1") (pintype "passive"))
      (node (ref "C2") (pin "2") (pinfunction "2_2") (pintype "passive"))
      (node (ref "C20") (pin "1") (pinfunction "1_1") (pintype "passive"))
      (node (ref "C21") (pin "2") (pinfunction "2_2") (pintype "passive"))
      (node (ref "C22") (pin "2") (pinfunction "2_2") (pintype "passive"))
      (node (ref "C23") (pin "2") (pinfunction "2_2") (pintype "passive"))
      (node (ref "C24") (pin "2") (pinfunction "2_2") (pintype "passive"))
      (node (ref "C25") (pin "2") (pinfunction "2_2") (pintype "passive"))
      (node (ref "C26") (pin "2") (pinfunction "2_2") (pintype "passive"))
      (node (ref "C27") (pin "2") (pinfunction "2_2") (pintype "passive"))
      (node (ref "C28") (pin "2") (pinfunction "2_2") (pintype "passive"))
      (node (ref "C29") (pin "1") (pinfunction "1_1") (pintype "passive"))
      (node (ref "C3") (pin "2") (pinfunction "2_2") (pintype "passive"))
      (node (ref "C32") (pin "2") (pinfunction "2_2") (pintype "passive"))
      (node (ref "C33") (pin "2") (pinfunction "2_2") (pintype "passive"))
      (node (ref "C34") (pin "2") (pinfunction "2_2") (pintype "passive"))
      (node (ref "C35") (pin "1") (pinfunction "1_1") (pintype "passive"))
      (node (ref "C36") (pin "2") (pinfunction "2_2") (pintype "passive"))
      (node (ref "C37") (pin "2") (pinfunction "2_2") (pintype "passive"))
      (node (ref "C38") (pin "1") (pinfunction "1_1") (pintype "passive"))
      (node (ref "C4") (pin "2") (pinfunction "2_2") (pintype "passive"))
      (node (ref "C40") (pin "2") (pinfunction "2_2") (pintype "passive"))
      (node (ref "C42") (pin "2") (pinfunction "2_2") (pintype "passive"))
      (node (ref "C43") (pin "-") (pinfunction "-_-") (pintype "passive"))
      (node (ref "C44") (pin "-") (pinfunction "-_-") (pintype "passive"))
      (node (ref "C47") (pin "2") (pinfunction "2_2") (pintype "passive"))
      (node (ref "C48") (pin "2") (pinfunction "2_2") (pintype "passive"))
      (node (ref "C5") (pin "2") (pinfunction "2_2") (pintype "passive"))
      (node (ref "C59") (pin "2") (pinfunction "2_2") (pintype "passive"))
      (node (ref "C6") (pin "2") (pinfunction "2_2") (pintype "passive"))
      (node (ref "C7") (pin "2") (pinfunction "2_2") (pintype "passive"))
      (node (ref "C8") (pin "2") (pinfunction "2_2") (pintype "passive"))
      (node (ref "C9") (pin "2") (pinfunction "2_2") (pintype "passive"))
      (node (ref "D21") (pin "-") (pinfunction "A_-") (pintype "passive"))
      (node (ref "D27") (pin "-") (pinfunction "A_-") (pintype "passive"))
      (node (ref "D28") (pin "-") (pinfunction "A_-") (pintype "passive"))
      (node (ref "D30") (pin "A") (pinfunction "A_A") (pintype "passive"))
      (node (ref "D31") (pin "1") (pinfunction "A_1") (pintype "passive"))
      (node (ref "D31") (pin "2") (pinfunction "A_2") (pintype "passive"))
      (node (ref "D32") (pin "A") (pinfunction "A_A") (pintype "passive"))
      (node (ref "D4") (pin "A") (pinfunction "A_A") (pintype "passive"))
      (node (ref "H1") (pin "P1") (pinfunction "P$1_P1") (pintype "bidirectional"))
      (node (ref "H2") (pin "P1") (pinfunction "P$1_P1") (pintype "bidirectional"))
      (node (ref "H3") (pin "P1") (pinfunction "P$1_P1") (pintype "bidirectional"))
      (node (ref "H4") (pin "P1") (pinfunction "P$1_P1") (pintype "bidirectional"))
      (node (ref "H5") (pin "P1") (pinfunction "P$1_P1") (pintype "bidirectional"))
      (node (ref "IC1") (pin "3") (pinfunction "GND_3") (pintype "power_in"))
      (node (ref "IC18") (pin "18") (pinfunction "GND2_18") (pintype "power_in"))
      (node (ref "IC18") (pin "21") (pinfunction "GND3_21") (pintype "power_in"))
      (node (ref "IC18") (pin "25") (pinfunction "AGND_25") (pintype "power_in"))
      (node (ref "IC18") (pin "26") (pinfunction "TEST_26") (pintype "bidirectional"))
      (node (ref "IC18") (pin "7") (pinfunction "GND1_7") (pintype "power_in"))
      (node (ref "IC19") (pin "4") (pinfunction "V-_4") (pintype "power_in"))
      (node (ref "IC2") (pin "5") (pinfunction "GND_5") (pintype "power_in"))
      (node (ref "IC21") (pin "4") (pinfunction "GND_4") (pintype "power_in"))
      (node (ref "IC3") (pin "15") (pinfunction "VSS15_15") (pintype "power_in"))
      (node (ref "IC3") (pin "31") (pinfunction "AVSS_31") (pintype "power_in"))
      (node (ref "IC3") (pin "36") (pinfunction "VSS36_36") (pintype "power_in"))
      (node (ref "IC3") (pin "45") (pinfunction "VSS45_45") (pintype "power_in"))
      (node (ref "IC3") (pin "65") (pinfunction "VSS65_65") (pintype "power_in"))
      (node (ref "IC3") (pin "75") (pinfunction "VSS75_75") (pintype "power_in"))
      (node (ref "IC4") (pin "2") (pinfunction "VSS_2") (pintype "power_in"))
      (node (ref "IC5") (pin "4") (pinfunction "GND_4") (pintype "power_in"))
      (node (ref "IC5") (pin "5") (pinfunction "A2_5") (pintype "input"))
      (node (ref "IC5") (pin "6") (pinfunction "A1_6") (pintype "input"))
      (node (ref "IC6") (pin "1") (pinfunction "A0_1") (pintype "input"))
      (node (ref "IC6") (pin "2") (pinfunction "A1_2") (pintype "input"))
      (node (ref "IC6") (pin "3") (pinfunction "A2_3") (pintype "input"))
      (node (ref "IC6") (pin "4") (pinfunction "GND_4") (pintype "power_in"))
      (node (ref "IC6") (pin "7") (pinfunction "WP_7") (pintype "input"))
      (node (ref "IC7") (pin "12") (pinfunction "CLKOE_12") (pintype "input"))
      (node (ref "IC7") (pin "7") (pinfunction "VSS_7") (pintype "power_in"))
      (node (ref "IC8") (pin "4") (pinfunction "GND_4") (pintype "power_in"))
      (node (ref "IC9") (pin "2") (pinfunction "GND_2") (pintype "power_in"))
      (node (ref "J1") (pin "1") (pinfunction "1_1") (pintype "passive"))
      (node (ref "J10") (pin "C5") (pinfunction "C5_C5") (pintype "bidirectional"))
      (node (ref "J11") (pin "3") (pinfunction "3_3") (pintype "passive"))
      (node (ref "J12") (pin "3") (pinfunction "3_3") (pintype "passive"))
      (node (ref "J15") (pin "10") (pinfunction "10_10") (pintype "bidirectional"))
      (node (ref "J15") (pin "10A") (pinfunction "10_10A") (pintype "bidirectional"))
      (node (ref "J18") (pin "6") (pinfunction "6_6") (pintype "bidirectional"))
      (node (ref "J18") (pin "9") (pinfunction "9_9") (pintype "bidirectional"))
      (node (ref "J19") (pin "1") (pinfunction "1_1") (pintype "bidirectional"))
      (node (ref "J19") (pin "11") (pinfunction "11_11") (pintype "bidirectional"))
      (node (ref "J19") (pin "3") (pinfunction "3_3") (pintype "bidirectional"))
      (node (ref "J19") (pin "5") (pinfunction "5_5") (pintype "bidirectional"))
      (node (ref "J19") (pin "7") (pinfunction "7_7") (pintype "bidirectional"))
      (node (ref "J19") (pin "9") (pinfunction "9_9") (pintype "bidirectional"))
      (node (ref "J2") (pin "1") (pinfunction "1_1") (pintype "passive"))
      (node (ref "J3") (pin "11") (pinfunction "11_11") (pintype "bidirectional"))
      (node (ref "J3") (pin "12") (pinfunction "12_12") (pintype "bidirectional"))
      (node (ref "J3") (pin "5") (pinfunction "5_5") (pintype "bidirectional"))
      (node (ref "J3") (pin "7") (pinfunction "7_7") (pintype "bidirectional"))
      (node (ref "J3") (pin "8") (pinfunction "8_8") (pintype "bidirectional"))
      (node (ref "J30") (pin "7") (pinfunction "GND_7") (pintype "bidirectional"))
      (node (ref "J41") (pin "1") (pinfunction "1_1") (pintype "passive"))
      (node (ref "J45") (pin "1") (pinfunction "1_1") (pintype "passive"))
      (node (ref "J50") (pin "1") (pinfunction "1_1") (pintype "bidirectional"))
      (node (ref "J50") (pin "2") (pinfunction "2_2") (pintype "bidirectional"))
      (node (ref "J7") (pin "1") (pinfunction "1_1") (pintype "passive"))
      (node (ref "J7") (pin "6") (pinfunction "6_6") (pintype "passive"))
      (node (ref "J8") (pin "9") (pinfunction "9_9") (pintype "passive"))
      (node (ref "J9") (pin "1") (pinfunction "1_1") (pintype "passive"))
      (node (ref "J9") (pin "6") (pinfunction "6_6") (pintype "passive"))
      (node (ref "JP1") (pin "1") (pinfunction "1_1") (pintype "passive"))
      (node (ref "L17") (pin "1") (pinfunction "1_1") (pintype "passive"))
      (node (ref "Q14") (pin "1") (pinfunction "GND_1") (pintype "power_in"))
      (node (ref "Q14") (pin "2") (pinfunction "GND1_2") (pintype "power_in"))
      (node (ref "Q15") (pin "1") (pinfunction "S_1") (pintype "passive"))
      (node (ref "Q16") (pin "EP") (pinfunction "PGND_EP") (pintype "passive"))
      (node (ref "Q18") (pin "1") (pinfunction "S_1") (pintype "passive"))
      (node (ref "Q19") (pin "EP") (pinfunction "PGND_EP") (pintype "passive"))
      (node (ref "Q2") (pin "1") (pinfunction "Q1S_1") (pintype "bidirectional"))
      (node (ref "Q20") (pin "2") (pinfunction "S_2") (pintype "passive"))
      (node (ref "Q21") (pin "2") (pinfunction "S_2") (pintype "passive"))
      (node (ref "Q3") (pin "1") (pinfunction "1_1") (pintype "passive"))
      (node (ref "Q5") (pin "1") (pinfunction "Q1S_1") (pintype "bidirectional"))
      (node (ref "R10") (pin "1") (pinfunction "1_1") (pintype "passive"))
      (node (ref "R13") (pin "1") (pinfunction "1_1") (pintype "passive"))
      (node (ref "R162") (pin "1") (pinfunction "1_1") (pintype "passive"))
      (node (ref "R165") (pin "1") (pinfunction "1_1") (pintype "passive"))
      (node (ref "R166") (pin "1") (pinfunction "1_1") (pintype "passive"))
      (node (ref "R174") (pin "2") (pinfunction "2_2") (pintype "passive"))
      (node (ref "R179") (pin "1") (pinfunction "1_1") (pintype "passive"))
      (node (ref "R182") (pin "1") (pinfunction "1_1") (pintype "passive"))
      (node (ref "R183") (pin "2") (pinfunction "2_2") (pintype "passive"))
      (node (ref "R184") (pin "2") (pinfunction "2_2") (pintype "passive"))
      (node (ref "R185") (pin "1") (pinfunction "1_1") (pintype "passive"))
      (node (ref "R197") (pin "2") (pinfunction "2_2") (pintype "passive"))
      (node (ref "R20") (pin "2") (pinfunction "1_2") (pintype "passive"))
      (node (ref "R21") (pin "5") (pinfunction "2_5") (pintype "passive"))
      (node (ref "R21") (pin "6") (pinfunction "2_6") (pintype "passive"))
      (node (ref "R22") (pin "1") (pinfunction "1_1") (pintype "passive"))
      (node (ref "R25") (pin "1") (pinfunction "1_1") (pintype "passive"))
      (node (ref "R29") (pin "5") (pinfunction "2_5") (pintype "passive"))
      (node (ref "R29") (pin "6") (pinfunction "2_6") (pintype "passive"))
      (node (ref "R5") (pin "1") (pinfunction "1_1") (pintype "passive"))
      (node (ref "R6") (pin "1") (pinfunction "1_1") (pintype "passive"))
      (node (ref "TP11") (pin "P$1") (pinfunction "TP_P$1") (pintype "passive"))
      (node (ref "TP12") (pin "1") (pinfunction "TP_1") (pintype "passive"))
      (node (ref "TP66") (pin "TP") (pinfunction "TP_TP") (pintype "input"))
      (node (ref "TP67") (pin "TP") (pinfunction "TP_TP") (pintype "input"))
      (node (ref "U1") (pin "10") (pinfunction "PGND_10") (pintype "bidirectional"))
      (node (ref "U1") (pin "21") (pinfunction "PRESB_21") (pintype "bidirectional"))
      (node (ref "U1") (pin "9") (pinfunction "SGND_9") (pintype "bidirectional"))
      (node (ref "U1") (pin "PAD") (pinfunction "PAD_PAD") (pintype "bidirectional"))
      (node (ref "U2") (pin "2") (pinfunction "GND_2") (pintype "bidirectional"))
      (node (ref "U2") (pin "3") (pinfunction "GND_3") (pintype "bidirectional"))
      (node (ref "U2") (pin "5") (pinfunction "INHIBIT_5") (pintype "bidirectional"))
      (node (ref "U2") (pin "6") (pinfunction "GND_6") (pintype "bidirectional"))
      (node (ref "U2") (pin "7") (pinfunction "GND_7") (pintype "bidirectional"))
      (node (ref "U3") (pin "3") (pinfunction "VSS_3") (pintype "bidirectional"))
      (node (ref "U6") (pin "16") (pinfunction "AGND_16") (pintype "power_in"))
      (node (ref "U6") (pin "9") (pinfunction "PGND_9") (pintype "power_in"))
      (node (ref "U6") (pin "EP") (pinfunction "PPAD_EP") (pintype "power_in"))
      (node (ref "U7") (pin "16") (pinfunction "AGND_16") (pintype "power_in"))
      (node (ref "U7") (pin "9") (pinfunction "PGND_9") (pintype "power_in"))
      (node (ref "U7") (pin "EP") (pinfunction "PPAD_EP") (pintype "power_in"))
      (node (ref "X1") (pin "7") (pinfunction "1_7") (pintype "passive"))
      (node (ref "X1") (pin "8") (pinfunction "1_8") (pintype "passive"))
      (node (ref "X2") (pin "4") (pinfunction "4_4") (pintype "passive"))
    )
    (net (code "57") (name "DIN_SM") (class "Default")
      (node (ref "IC3") (pin "6") (pinfunction "RC1/CN45/RPI38_6") (pintype "bidirectional"))
      (node (ref "U1") (pin "27") (pinfunction "DIN_27") (pintype "bidirectional"))
    )
    (net (code "58") (name "DOOR2_L") (class "Default")
      (node (ref "IC3") (pin "50") (pinfunction "CN18/RP17/RF5_50") (pintype "bidirectional"))
      (node (ref "R29") (pin "2") (pinfunction "1_2") (pintype "passive"))
      (node (ref "R29") (pin "3") (pinfunction "1_3") (pintype "passive"))
    )
    (net (code "59") (name "DOOR2_L_SW") (class "Default")
      (node (ref "C36") (pin "1") (pinfunction "1_1") (pintype "passive"))
      (node (ref "J19") (pin "2") (pinfunction "2_2") (pintype "bidirectional"))
      (node (ref "R27") (pin "2") (pinfunction "2_2") (pintype "passive"))
      (node (ref "R29") (pin "7") (pinfunction "2_7") (pintype "passive"))
    )
    (net (code "60") (name "DOOR2_R") (class "Default")
      (node (ref "IC3") (pin "55") (pinfunction "CN72/RPI45/RF6_55") (pintype "bidirectional"))
      (node (ref "R29") (pin "1") (pinfunction "1_1") (pintype "passive"))
      (node (ref "R29") (pin "4") (pinfunction "1_4") (pintype "passive"))
    )
    (net (code "61") (name "DOOR2_R_SW") (class "Default")
      (node (ref "C47") (pin "1") (pinfunction "1_1") (pintype "passive"))
      (node (ref "J19") (pin "4") (pinfunction "4_4") (pintype "bidirectional"))
      (node (ref "R28") (pin "2") (pinfunction "2_2") (pintype "passive"))
      (node (ref "R29") (pin "8") (pinfunction "2_8") (pintype "passive"))
    )
    (net (code "62") (name "DOOR_L") (class "Default")
      (node (ref "IC3") (pin "73") (pinfunction "RC13/SOSCI/CN1_73") (pintype "bidirectional"))
      (node (ref "R21") (pin "2") (pinfunction "1_2") (pintype "passive"))
      (node (ref "R21") (pin "3") (pinfunction "1_3") (pintype "passive"))
    )
    (net (code "63") (name "DOOR_L_SW") (class "Default")
      (node (ref "C25") (pin "1") (pinfunction "1_1") (pintype "passive"))
      (node (ref "J19") (pin "6") (pinfunction "6_6") (pintype "bidirectional"))
      (node (ref "R18") (pin "2") (pinfunction "2_2") (pintype "passive"))
      (node (ref "R21") (pin "7") (pinfunction "2_7") (pintype "passive"))
    )
    (net (code "64") (name "DOOR_ON") (class "Default")
      (node (ref "IC3") (pin "87") (pinfunction "CN68/RF0_87") (pintype "bidirectional"))
      (node (ref "Q5") (pin "5") (pinfunction "Q1G_5") (pintype "input"))
      (node (ref "R20") (pin "7") (pinfunction "2_7") (pintype "passive"))
    )
    (net (code "65") (name "DOOR_R") (class "Default")
      (node (ref "IC3") (pin "91") (pinfunction "RA6/CN39_91") (pintype "bidirectional"))
      (node (ref "R21") (pin "1") (pinfunction "1_1") (pintype "passive"))
      (node (ref "R21") (pin "4") (pinfunction "1_4") (pintype "passive"))
    )
    (net (code "66") (name "DOOR_R_SW") (class "Default")
      (node (ref "C26") (pin "1") (pinfunction "1_1") (pintype "passive"))
      (node (ref "J19") (pin "8") (pinfunction "8_8") (pintype "bidirectional"))
      (node (ref "R19") (pin "2") (pinfunction "2_2") (pintype "passive"))
      (node (ref "R21") (pin "8") (pinfunction "2_8") (pintype "passive"))
    )
    (net (code "67") (name "DOUT_SM_B") (class "Default")
      (node (ref "IC3") (pin "7") (pinfunction "RC2/CN46/RPI39_7") (pintype "bidirectional"))
      (node (ref "U1") (pin "28") (pinfunction "DOUT_28") (pintype "bidirectional"))
    )
    (net (code "68") (name "ID1_L_N") (class "Default")
      (node (ref "C31") (pin "2") (pinfunction "2_2") (pintype "passive"))
      (node (ref "IC9") (pin "3") (pinfunction "FB_3") (pintype "input"))
      (node (ref "J14") (pin "1") (pinfunction "1_1") (pintype "passive"))
      (node (ref "J18") (pin "8") (pinfunction "8_8") (pintype "bidirectional"))
      (node (ref "R25") (pin "2") (pinfunction "2_2") (pintype "passive"))
    )
    (net (code "69") (name "ID_L_P") (class "Default")
      (node (ref "C31") (pin "1") (pinfunction "1_1") (pintype "passive"))
      (node (ref "C32") (pin "1") (pinfunction "1_1") (pintype "passive"))
      (node (ref "D3") (pin "A") (pinfunction "A_A") (pintype "passive"))
      (node (ref "J14") (pin "2") (pinfunction "2_2") (pintype "passive"))
      (node (ref "J18") (pin "7") (pinfunction "7_7") (pintype "bidirectional"))
      (node (ref "L3") (pin "2") (pinfunction "2_2") (pintype "passive"))
    )
    (net (code "70") (name "ID_PWM") (class "Default")
      (node (ref "IC3") (pin "51") (pinfunction "CN71/RP16/RF3_51") (pintype "bidirectional"))
      (node (ref "R23") (pin "1") (pinfunction "1_1") (pintype "passive"))
    )
    (net (code "71") (name "IOB") (class "Default")
      (node (ref "J10") (pin "C7") (pinfunction "C7_C7") (pintype "bidirectional"))
      (node (ref "U1") (pin "20") (pinfunction "IOB_20") (pintype "bidirectional"))
    )
    (net (code "72") (name "ISENSEA") (class "Default")
      (node (ref "IC19") (pin "1") (pinfunction "OUT_1") (pintype "output"))
      (node (ref "IC19") (pin "2") (pinfunction "-IN_2") (pintype "input"))
      (node (ref "IC3") (pin "43") (pinfunction "RB14/AN14/CN32/RP14_43") (pintype "bidirectional"))
    )
    (net (code "73") (name "ISENSEB") (class "Default")
      (node (ref "IC3") (pin "44") (pinfunction "RB15/AN15/CN12/RP29_44") (pintype "bidirectional"))
    )
    (net (code "74") (name "ISEN_OP_EN") (class "Default")
      (node (ref "C134") (pin "1") (pinfunction "1_1") (pintype "passive"))
      (node (ref "IC19") (pin "8") (pinfunction "V+_8") (pintype "power_in"))
      (node (ref "IC3") (pin "68") (pinfunction "CN53/RP2/RD8_68") (pintype "bidirectional"))
    )
    (net (code "75") (name "LCD_SI") (class "Default")
      (node (ref "IC3") (pin "32") (pinfunction "RB8/AN8/CN26/RP8_32") (pintype "bidirectional"))
    )
    (net (code "76") (name "LD_SM") (class "Default")
      (node (ref "IC3") (pin "9") (pinfunction "RC4/CN48/RPI41_9") (pintype "bidirectional"))
      (node (ref "U1") (pin "25") (pinfunction "/LD_25") (pintype "bidirectional"))
    )
    (net (code "77") (name "MICROPHONE") (class "Default")
      (node (ref "J17") (pin "2") (pinfunction "2_2") (pintype "bidirectional"))
      (node (ref "J48") (pin "2") (pinfunction "2_2") (pintype "passive"))
      (node (ref "R207") (pin "2") (pinfunction "2_2") (pintype "passive"))
      (node (ref "R208") (pin "1") (pinfunction "1_1") (pintype "passive"))
      (node (ref "U9") (pin "3") (pinfunction "+IN_3") (pintype "input"))
    )
    (net (code "78") (name "MIC_AMP_EN") (class "Default")
      (node (ref "IC3") (pin "96") (pinfunction "CN79/RG12_96") (pintype "bidirectional"))
      (node (ref "J49") (pin "1") (pinfunction "1_1") (pintype "passive"))
      (node (ref "Q24") (pin "1") (pinfunction "G_1") (pintype "passive"))
      (node (ref "R210") (pin "1") (pinfunction "1_1") (pintype "passive"))
      (node (ref "U9") (pin "5") (pinfunction "~{SHDN}_5") (pintype "power_in"))
    )
    (net (code "79") (name "N$5") (class "Default")
      (node (ref "J15") (pin "6") (pinfunction "6_6") (pintype "bidirectional"))
      (node (ref "J15") (pin "6A") (pinfunction "6_6A") (pintype "bidirectional"))
      (node (ref "J15") (pin "8") (pinfunction "8_8") (pintype "bidirectional"))
      (node (ref "J15") (pin "8A") (pinfunction "8_8A") (pintype "bidirectional"))
      (node (ref "R38") (pin "2") (pinfunction "2_2") (pintype "passive"))
    )
    (net (code "80") (name "N$41") (class "Default")
      (node (ref "J15") (pin "2") (pinfunction "2_2") (pintype "bidirectional"))
      (node (ref "J15") (pin "2A") (pinfunction "2_2A") (pintype "bidirectional"))
      (node (ref "J15") (pin "4") (pinfunction "4_4") (pintype "bidirectional"))
      (node (ref "J15") (pin "4A") (pinfunction "4_4A") (pintype "bidirectional"))
      (node (ref "R39") (pin "2") (pinfunction "2_2") (pintype "passive"))
    )
    (net (code "81") (name "Net-(C164-Pad1)") (class "Default")
      (node (ref "C164") (pin "1") (pinfunction "1_1") (pintype "passive"))
      (node (ref "R193") (pin "1") (pinfunction "1_1") (pintype "passive"))
    )
    (net (code "82") (name "Net-(C171-Pad1)") (class "Default")
      (node (ref "C171") (pin "1") (pinfunction "1_1") (pintype "passive"))
      (node (ref "R198") (pin "1") (pinfunction "1_1") (pintype "passive"))
      (node (ref "R199") (pin "2") (pinfunction "2_2") (pintype "passive"))
      (node (ref "U8") (pin "7") (pinfunction "AVCC_7") (pintype "power_in"))
    )
    (net (code "83") (name "Net-(C185-Pad2)") (class "Default")
      (node (ref "C185") (pin "2") (pinfunction "2_2") (pintype "passive"))
      (node (ref "R211") (pin "1") (pinfunction "1_1") (pintype "passive"))
    )
    (net (code "84") (name "Net-(D1-A1)") (class "Default")
      (node (ref "B1") (pin "+") (pinfunction "+_+") (pintype "passive"))
      (node (ref "D1") (pin "1") (pinfunction "A1_1") (pintype "passive"))
      (node (ref "TP7") (pin "P$1") (pinfunction "TP_P$1") (pintype "passive"))
    )
    (net (code "85") (name "Net-(D1-K)") (class "Default")
      (node (ref "C24") (pin "1") (pinfunction "1_1") (pintype "passive"))
      (node (ref "D1") (pin "3") (pinfunction "K_3") (pintype "passive"))
      (node (ref "IC7") (pin "14") (pinfunction "VDD_14") (pintype "power_in"))
    )
    (net (code "86") (name "Net-(D2-K)") (class "Default")
      (node (ref "C30") (pin "1") (pinfunction "1_1") (pintype "passive"))
      (node (ref "D2") (pin "C") (pinfunction "K_C") (pintype "passive"))
      (node (ref "D3") (pin "C") (pinfunction "K_C") (pintype "passive"))
      (node (ref "IC9") (pin "1") (pinfunction "BOOST_1") (pintype "input"))
    )
    (net (code "87") (name "Net-(D17-A)") (class "Default")
      (node (ref "D17") (pin "2") (pinfunction "A_2") (pintype "passive"))
      (node (ref "R151") (pin "1") (pinfunction "1_1") (pintype "passive"))
    )
    (net (code "88") (name "Net-(D17-K)") (class "Default")
      (node (ref "D17") (pin "1+") (pinfunction "K_1+") (pintype "passive"))
      (node (ref "IC18") (pin "22") (pinfunction "GPIO0_22") (pintype "output"))
    )
    (net (code "89") (name "Net-(D19-A)") (class "Default")
      (node (ref "D19") (pin "2") (pinfunction "A_2") (pintype "passive"))
      (node (ref "R152") (pin "1") (pinfunction "1_1") (pintype "passive"))
    )
    (net (code "90") (name "Net-(D19-K)") (class "Default")
      (node (ref "D19") (pin "1+") (pinfunction "K_1+") (pintype "passive"))
      (node (ref "IC18") (pin "23") (pinfunction "GPIO1_23") (pintype "output"))
    )
    (net (code "91") (name "Net-(D23-A)") (class "Default")
      (node (ref "D23") (pin "2") (pinfunction "A_2") (pintype "passive"))
      (node (ref "R175") (pin "1") (pinfunction "1_1") (pintype "passive"))
    )
    (net (code "92") (name "Net-(D24-A)") (class "Default")
      (node (ref "D24") (pin "2") (pinfunction "A_2") (pintype "passive"))
      (node (ref "R176") (pin "1") (pinfunction "1_1") (pintype "passive"))
    )
    (net (code "93") (name "Net-(IC1-VIN)") (class "Default")
      (node (ref "C23") (pin "1") (pinfunction "1_1") (pintype "passive"))
      (node (ref "C59") (pin "1") (pinfunction "1_1") (pintype "passive"))
      (node (ref "IC1") (pin "1") (pinfunction "VIN_1") (pintype "power_in"))
      (node (ref "R37") (pin "1") (pinfunction "1_1") (pintype "passive"))
    )
    (net (code "94") (name "Net-(IC3-AVDD)") (class "Default")
      (node (ref "C3") (pin "1") (pinfunction "1_1") (pintype "passive"))
      (node (ref "C7") (pin "1") (pinfunction "1_1") (pintype "passive"))
      (node (ref "IC3") (pin "30") (pinfunction "AVDD_30") (pintype "power_in"))
      (node (ref "R1") (pin "1") (pinfunction "1_1") (pintype "passive"))
    )
    (net (code "95") (name "Net-(IC3-OSC1{slash}CLKI{slash}RC12)") (class "Default")
      (node (ref "C18") (pin "2") (pinfunction "2_2") (pintype "passive"))
      (node (ref "IC3") (pin "63") (pinfunction "OSC1/CLKI/RC12_63") (pintype "bidirectional"))
      (node (ref "Q4") (pin "3") (pinfunction "2_3") (pintype "passive"))
    )
    (net (code "96") (name "Net-(IC3-OSC2{slash}CLKO{slash}RC15)") (class "Default")
      (node (ref "C19") (pin "2") (pinfunction "2_2") (pintype "passive"))
      (node (ref "IC3") (pin "64") (pinfunction "OSC2/CLKO/RC15_64") (pintype "bidirectional"))
      (node (ref "Q4") (pin "1") (pinfunction "1_1") (pintype "passive"))
    )
    (net (code "97") (name "Net-(IC3-RA4{slash}TDI{slash}CN37)") (class "Default")
      (node (ref "IC3") (pin "60") (pinfunction "RA4/TDI/CN37_60") (pintype "bidirectional"))
      (node (ref "TP2") (pin "P$1") (pinfunction "TP_P$1") (pintype "passive"))
    )
    (net (code "98") (name "Net-(IC3-RB10{slash}AN10{slash}CN28{slash}CVREF)") (class "Default")
      (node (ref "IC3") (pin "34") (pinfunction "RB10/AN10/CN28/CVREF_34") (pintype "bidirectional"))
      (node (ref "TP3") (pin "P$1") (pinfunction "TP_P$1") (pintype "passive"))
    )
    (net (code "99") (name "Net-(IC3-VDDCORE)") (class "Default")
      (node (ref "C10") (pin "2") (pinfunction "2_2") (pintype "passive"))
      (node (ref "C38") (pin "2") (pinfunction "2_2") (pintype "passive"))
      (node (ref "IC3") (pin "85") (pinfunction "VDDCORE_85") (pintype "passive"))
    )
    (net (code "100") (name "Net-(IC4-VDD)") (class "Default")
      (node (ref "C21") (pin "1") (pinfunction "1_1") (pintype "passive"))
      (node (ref "IC4") (pin "5") (pinfunction "VDD_5") (pintype "power_in"))
      (node (ref "J12") (pin "2") (pinfunction "2_2") (pintype "passive"))
      (node (ref "R15") (pin "1") (pinfunction "1_1") (pintype "passive"))
    )
    (net (code "101") (name "Net-(IC7-OSCI)") (class "Default")
      (node (ref "IC7") (pin "1") (pinfunction "OSCI_1") (pintype "input"))
      (node (ref "Q6") (pin "2") (pinfunction "2_2") (pintype "passive"))
    )
    (net (code "102") (name "Net-(IC7-OSCO)") (class "Default")
      (node (ref "IC7") (pin "2") (pinfunction "OSCO_2") (pintype "output"))
      (node (ref "Q6") (pin "1") (pinfunction "1_1") (pintype "passive"))
    )
    (net (code "103") (name "Net-(IC9-EN{slash}DIM)") (class "Default")
      (node (ref "C34") (pin "1") (pinfunction "1_1") (pintype "passive"))
      (node (ref "IC9") (pin "4") (pinfunction "EN/DIM_4") (pintype "input"))
      (node (ref "R23") (pin "2") (pinfunction "2_2") (pintype "passive"))
    )
    (net (code "104") (name "Net-(IC9-SW)") (class "Default")
      (node (ref "C30") (pin "2") (pinfunction "2_2") (pintype "passive"))
      (node (ref "D4") (pin "K") (pinfunction "K_K") (pintype "passive"))
      (node (ref "IC9") (pin "6") (pinfunction "SW_6") (pintype "output"))
      (node (ref "L3") (pin "1") (pinfunction "1_1") (pintype "passive"))
    )
    (net (code "105") (name "Net-(IC18-VCC30)") (class "Default")
      (node (ref "C121") (pin "2") (pinfunction "2_2") (pintype "passive"))
      (node (ref "IC18") (pin "17") (pinfunction "VCC30_17") (pintype "power_in"))
      (node (ref "IC18") (pin "4") (pinfunction "VCCIO_4") (pintype "power_in"))
      (node (ref "TP60") (pin "P$1") (pinfunction "TP_P$1") (pintype "passive"))
    )
    (net (code "106") (name "Net-(IC19A-+IN)") (class "Default")
      (node (ref "IC19") (pin "3") (pinfunction "+IN_3") (pintype "input"))
      (node (ref "Q14") (pin "3") (pinfunction "OUT_3") (pintype "output"))
    )
    (net (code "107") (name "Net-(IC21-ITH)") (class "Default")
      (node (ref "IC21") (pin "2") (pinfunction "ITH_2") (pintype "input"))
      (node (ref "R193") (pin "2") (pinfunction "2_2") (pintype "passive"))
    )
    (net (code "108") (name "Net-(IC21-PGATE)") (class "Default")
      (node (ref "IC21") (pin "5") (pinfunction "PGATE_5") (pintype "output"))
      (node (ref "Q23") (pin "1") (pinfunction "G_1") (pintype "passive"))
    )
    (net (code "109") (name "Net-(IC21-SENSE)") (class "Default")
      (node (ref "C155") (pin "2") (pinfunction "2_2") (pintype "passive"))
      (node (ref "IC21") (pin "7") (pinfunction "SENSE_7") (pintype "input"))
      (node (ref "Q23") (pin "2") (pinfunction "S_2") (pintype "passive"))
      (node (ref "R189") (pin "1") (pinfunction "1_1") (pintype "passive"))
    )
    (net (code "110") (name "Net-(IC21-VFB)") (class "Default")
      (node (ref "C160") (pin "1") (pinfunction "1_1") (pintype "passive"))
      (node (ref "IC21") (pin "3") (pinfunction "VFB_3") (pintype "input"))
      (node (ref "R194") (pin "2") (pinfunction "2_2") (pintype "passive"))
      (node (ref "R197") (pin "1") (pinfunction "1_1") (pintype "passive"))
    )
    (net (code "111") (name "Net-(J45-Pad2)") (class "Default")
      (node (ref "J45") (pin "2") (pinfunction "2_2") (pintype "passive"))
      (node (ref "R46") (pin "2") (pinfunction "2_2") (pintype "passive"))
    )
    (net (code "112") (name "Net-(J45-Pad3)") (class "Default")
      (node (ref "J45") (pin "3") (pinfunction "3_3") (pintype "passive"))
      (node (ref "R45") (pin "2") (pinfunction "2_2") (pintype "passive"))
    )
    (net (code "113") (name "Net-(Q2-Q2G)") (class "Default")
      (node (ref "Q2") (pin "6") (pinfunction "Q2G_6") (pintype "input"))
      (node (ref "R3") (pin "2") (pinfunction "2_2") (pintype "passive"))
    )
    (net (code "114") (name "Net-(Q5-Q2D1)") (class "Default")
      (node (ref "Q5") (pin "2") (pinfunction "Q2D1_2") (pintype "bidirectional"))
      (node (ref "Q5") (pin "3") (pinfunction "Q2D2_3") (pintype "bidirectional"))
      (node (ref "R18") (pin "1") (pinfunction "1_1") (pintype "passive"))
      (node (ref "R19") (pin "1") (pinfunction "1_1") (pintype "passive"))
      (node (ref "R27") (pin "1") (pinfunction "1_1") (pintype "passive"))
      (node (ref "R28") (pin "1") (pinfunction "1_1") (pintype "passive"))
    )
    (net (code "115") (name "Net-(Q5-Q2G)") (class "Default")
      (node (ref "Q5") (pin "6") (pinfunction "Q2G_6") (pintype "input"))
      (node (ref "R20") (pin "3") (pinfunction "1_3") (pintype "passive"))
    )
    (net (code "116") (name "Net-(Q14-VIN+)") (class "Default")
      (node (ref "C187") (pin "+") (pinfunction "+_+") (pintype "passive"))
      (node (ref "D32") (pin "C") (pinfunction "C_C") (pintype "passive"))
      (node (ref "F3") (pin "2") (pinfunction "2_2") (pintype "passive"))
      (node (ref "Q14") (pin "5") (pinfunction "VIN+_5") (pintype "input"))
      (node (ref "R154") (pin "1") (pinfunction "1_1") (pintype "passive"))
      (node (ref "R40") (pin "1") (pinfunction "1_1") (pintype "passive"))
      (node (ref "R41") (pin "1") (pinfunction "1_1") (pintype "passive"))
      (node (ref "TP63") (pin "TP") (pinfunction "TP_TP") (pintype "input"))
    )
    (net (code "117") (name "Net-(Q15A-D)") (class "Default")
      (node (ref "Q15") (pin "7") (pinfunction "D_7") (pintype "passive"))
      (node (ref "Q15") (pin "8") (pinfunction "D1_8") (pintype "passive"))
      (node (ref "R159") (pin "1") (pinfunction "1_1") (pintype "passive"))
    )
    (net (code "118") (name "Net-(Q15B-D)") (class "Default")
      (node (ref "C122") (pin "1") (pinfunction "1_1") (pintype "passive"))
      (node (ref "C123") (pin "1") (pinfunction "1_1") (pintype "passive"))
      (node (ref "C125") (pin "1") (pinfunction "1_1") (pintype "passive"))
      (node (ref "Q15") (pin "5") (pinfunction "D_5") (pintype "passive"))
      (node (ref "Q15") (pin "6") (pinfunction "D1_6") (pintype "passive"))
      (node (ref "R157") (pin "2") (pinfunction "2_2") (pintype "passive"))
      (node (ref "R42") (pin "1") (pinfunction "1_1") (pintype "passive"))
      (node (ref "R43") (pin "1") (pinfunction "1_1") (pintype "passive"))
      (node (ref "U6") (pin "7") (pinfunction "VIN_7") (pintype "power_in"))
    )
    (net (code "119") (name "Net-(Q15B-G)") (class "Default")
      (node (ref "Q15") (pin "4") (pinfunction "G_4") (pintype "passive"))
      (node (ref "R156") (pin "1") (pinfunction "1_1") (pintype "passive"))
      (node (ref "R159") (pin "2") (pinfunction "2_2") (pintype "passive"))
    )
    (net (code "120") (name "Net-(Q18A-D)") (class "Default")
      (node (ref "Q18") (pin "7") (pinfunction "D_7") (pintype "passive"))
      (node (ref "Q18") (pin "8") (pinfunction "D1_8") (pintype "passive"))
      (node (ref "R173") (pin "2") (pinfunction "2_2") (pintype "passive"))
    )
    (net (code "121") (name "Net-(Q18B-D)") (class "Default")
      (node (ref "C136") (pin "1") (pinfunction "1_1") (pintype "passive"))
      (node (ref "C137") (pin "1") (pinfunction "1_1") (pintype "passive"))
      (node (ref "C139") (pin "1") (pinfunction "1_1") (pintype "passive"))
      (node (ref "Q18") (pin "5") (pinfunction "D_5") (pintype "passive"))
      (node (ref "Q18") (pin "6") (pinfunction "D1_6") (pintype "passive"))
      (node (ref "R171") (pin "2") (pinfunction "2_2") (pintype "passive"))
      (node (ref "R44") (pin "1") (pinfunction "1_1") (pintype "passive"))
      (node (ref "U7") (pin "7") (pinfunction "VIN_7") (pintype "power_in"))
    )
    (net (code "122") (name "Net-(Q18B-G)") (class "Default")
      (node (ref "Q18") (pin "4") (pinfunction "G_4") (pintype "passive"))
      (node (ref "R170") (pin "2") (pinfunction "2_2") (pintype "passive"))
      (node (ref "R173") (pin "1") (pinfunction "1_1") (pintype "passive"))
    )
    (net (code "123") (name "Net-(Q23-D)") (class "Default")
      (node (ref "D30") (pin "K") (pinfunction "K_K") (pintype "passive"))
      (node (ref "L14") (pin "1") (pinfunction "1_1") (pintype "passive"))
      (node (ref "Q23") (pin "3") (pinfunction "D_3") (pintype "passive"))
    )
    (net (code "124") (name "Net-(Q24-D)") (class "Default")
      (node (ref "Q24") (pin "3") (pinfunction "D_3") (pintype "passive"))
      (node (ref "R208") (pin "2") (pinfunction "2_2") (pintype "passive"))
    )
    (net (code "125") (name "Net-(R199-Pad1)") (class "Default")
      (node (ref "R199") (pin "1") (pinfunction "1_1") (pintype "passive"))
      (node (ref "U8") (pin "14") (pinfunction "AVCC_14") (pintype "power_in"))
    )
    (net (code "126") (name "Net-(TP69-TP)") (class "Default")
      (node (ref "R204") (pin "2") (pinfunction "2_2") (pintype "passive"))
      (node (ref "TP69") (pin "1") (pinfunction "TP_1") (pintype "passive"))
    )
    (net (code "127") (name "Net-(U1--UNDERV)") (class "Default")
      (node (ref "R12") (pin "1") (pinfunction "1_1") (pintype "passive"))
      (node (ref "U1") (pin "23") (pinfunction "-UNDERV_23") (pintype "bidirectional"))
    )
    (net (code "128") (name "Net-(U1-C+)") (class "Default")
      (node (ref "C15") (pin "2") (pinfunction "2_2") (pintype "passive"))
      (node (ref "U1") (pin "14") (pinfunction "C+_14") (pintype "bidirectional"))
    )
    (net (code "129") (name "Net-(U1-C-)") (class "Default")
      (node (ref "C15") (pin "1") (pinfunction "1_1") (pintype "passive"))
      (node (ref "U1") (pin "11") (pinfunction "C-_11") (pintype "bidirectional"))
    )
    (net (code "130") (name "Net-(U1-CLKB)") (class "Default")
      (node (ref "J10") (pin "C3") (pinfunction "C3_C3") (pintype "bidirectional"))
      (node (ref "U1") (pin "18") (pinfunction "CLKB_18") (pintype "bidirectional"))
    )
    (net (code "131") (name "Net-(U1-CPO)") (class "Default")
      (node (ref "C20") (pin "2") (pinfunction "2_2") (pintype "passive"))
      (node (ref "U1") (pin "15") (pinfunction "CPO_15") (pintype "bidirectional"))
    )
    (net (code "132") (name "Net-(U1-NC{slash}-NO)") (class "Default")
      (node (ref "R13") (pin "2") (pinfunction "2_2") (pintype "passive"))
      (node (ref "U1") (pin "22") (pinfunction "NC/-NO_22") (pintype "bidirectional"))
    )
    (net (code "133") (name "Net-(U1-RSTB)") (class "Default")
      (node (ref "J10") (pin "C2") (pinfunction "C2_C2") (pintype "bidirectional"))
      (node (ref "U1") (pin "19") (pinfunction "RSTB_19") (pintype "bidirectional"))
    )
    (net (code "134") (name "Net-(U1-VCCB)") (class "Default")
      (node (ref "J10") (pin "C1") (pinfunction "C1_C1") (pintype "bidirectional"))
      (node (ref "U1") (pin "17") (pinfunction "VCCB_17") (pintype "bidirectional"))
    )
    (net (code "135") (name "Net-(U3-AIN0)") (class "Default")
      (node (ref "C39") (pin "1") (pinfunction "1_1") (pintype "passive"))
      (node (ref "R33") (pin "1") (pinfunction "1_1") (pintype "passive"))
      (node (ref "R34") (pin "2") (pinfunction "2_2") (pintype "passive"))
      (node (ref "U3") (pin "4") (pinfunction "AIN0_4") (pintype "bidirectional"))
    )
    (net (code "136") (name "Net-(U3-AIN2)") (class "Default")
      (node (ref "C41") (pin "1") (pinfunction "1_1") (pintype "passive"))
      (node (ref "R35") (pin "1") (pinfunction "1_1") (pintype "passive"))
      (node (ref "R36") (pin "2") (pinfunction "2_2") (pintype "passive"))
      (node (ref "U3") (pin "6") (pinfunction "AIN2_6") (pintype "bidirectional"))
    )
    (net (code "137") (name "Net-(U9--IN)") (class "Default")
      (node (ref "C185") (pin "1") (pinfunction "1_1") (pintype "passive"))
      (node (ref "C186") (pin "1") (pinfunction "1_1") (pintype "passive"))
      (node (ref "R209") (pin "2") (pinfunction "2_2") (pintype "passive"))
      (node (ref "U9") (pin "4") (pinfunction "-IN_4") (pintype "input"))
    )
    (net (code "138") (name "Net-(U9-OUT)") (class "Default")
      (node (ref "C183") (pin "1") (pinfunction "1_1") (pintype "passive"))
      (node (ref "C184") (pin "1") (pinfunction "1_1") (pintype "passive"))
      (node (ref "C186") (pin "2") (pinfunction "2_2") (pintype "passive"))
      (node (ref "R209") (pin "1") (pinfunction "1_1") (pintype "passive"))
      (node (ref "U9") (pin "1") (pinfunction "OUT_1") (pintype "output"))
    )
    (net (code "139") (name "OUTN_UNF") (class "Default")
      (node (ref "C178") (pin "2") (pinfunction "2_2") (pintype "passive"))
      (node (ref "L16") (pin "2") (pinfunction "2_2") (pintype "passive"))
      (node (ref "U8") (pin "23") (pinfunction "OUTN_23") (pintype "output"))
      (node (ref "U8") (pin "25") (pinfunction "OUTN_25") (pintype "output"))
    )
    (net (code "140") (name "OUTP_UNF") (class "Default")
      (node (ref "C173") (pin "2") (pinfunction "2_2") (pintype "passive"))
      (node (ref "L15") (pin "2") (pinfunction "2_2") (pintype "passive"))
      (node (ref "U8") (pin "18") (pinfunction "OUTP_18") (pintype "output"))
      (node (ref "U8") (pin "20") (pinfunction "OUTP_20") (pintype "output"))
    )
    (net (code "141") (name "OUT_S1") (class "Default")
      (node (ref "D23") (pin "1+") (pinfunction "K_1+") (pintype "passive"))
      (node (ref "D25") (pin "A") (pinfunction "A_A") (pintype "passive"))
      (node (ref "J15") (pin "12") (pinfunction "12_12") (pintype "bidirectional"))
      (node (ref "J15") (pin "12A") (pinfunction "12_12A") (pintype "bidirectional"))
      (node (ref "Q20") (pin "3") (pinfunction "D_3") (pintype "passive"))
    )
    (net (code "142") (name "OUT_S2") (class "Default")
      (node (ref "D24") (pin "1+") (pinfunction "K_1+") (pintype "passive"))
      (node (ref "D26") (pin "A") (pinfunction "A_A") (pintype "passive"))
      (node (ref "J16") (pin "2") (pinfunction "2_2") (pintype "bidirectional"))
      (node (ref "J16") (pin "2A") (pinfunction "2_2A") (pintype "bidirectional"))
      (node (ref "Q21") (pin "3") (pinfunction "D_3") (pintype "passive"))
    )
    (net (code "143") (name "P12V") (class "Default")
      (node (ref "C128") (pin "1") (pinfunction "1_1") (pintype "passive"))
      (node (ref "C129") (pin "1") (pinfunction "1_1") (pintype "passive"))
      (node (ref "C130") (pin "1") (pinfunction "1_1") (pintype "passive"))
      (node (ref "C165") (pin "1") (pinfunction "1_1") (pintype "passive"))
      (node (ref "C166") (pin "1") (pinfunction "1_1") (pintype "passive"))
      (node (ref "C167") (pin "1") (pinfunction "1_1") (pintype "passive"))
      (node (ref "C168") (pin "1") (pinfunction "1_1") (pintype "passive"))
      (node (ref "C169") (pin "1") (pinfunction "1_1") (pintype "passive"))
      (node (ref "C170") (pin "1") (pinfunction "1_1") (pintype "passive"))
      (node (ref "C44") (pin "+") (pinfunction "+_+") (pintype "passive"))
      (node (ref "D20") (pin "K") (pinfunction "K_K") (pintype "passive"))
      (node (ref "J18") (pin "3") (pinfunction "3_3") (pintype "bidirectional"))
      (node (ref "J50") (pin "3") (pinfunction "3_3") (pintype "bidirectional"))
      (node (ref "J50") (pin "4") (pinfunction "4_4") (pintype "bidirectional"))
      (node (ref "Q16") (pin "1_2") (pinfunction "VIN_1_2") (pintype "passive"))
      (node (ref "R160") (pin "2") (pinfunction "2_2") (pintype "passive"))
      (node (ref "R198") (pin "2") (pinfunction "2_2") (pintype "passive"))
      (node (ref "TP61") (pin "TP") (pinfunction "TP_TP") (pintype "input"))
      (node (ref "U8") (pin "15") (pinfunction "PVCC_15") (pintype "power_in"))
      (node (ref "U8") (pin "16") (pinfunction "PVCC_16") (pintype "power_in"))
      (node (ref "U8") (pin "27") (pinfunction "PVCC_27") (pintype "power_in"))
      (node (ref "U8") (pin "28") (pinfunction "PVCC_28") (pintype "power_in"))
    )
    (net (code "144") (name "PGC") (class "Default")
      (node (ref "IC3") (pin "26") (pinfunction "RB6/AN6/PGC2/RP6_26") (pintype "bidirectional"))
      (node (ref "J11") (pin "5") (pinfunction "5_5") (pintype "passive"))
    )
    (net (code "145") (name "PGD") (class "Default")
      (node (ref "IC3") (pin "27") (pinfunction "RB7/AN7/PGD2/RP7_27") (pintype "bidirectional"))
      (node (ref "J11") (pin "4") (pinfunction "4_4") (pintype "passive"))
    )
    (net (code "146") (name "PHOTOCELL") (class "Default")
      (node (ref "R7") (pin "2") (pinfunction "2_2") (pintype "passive"))
      (node (ref "R8") (pin "2") (pinfunction "2_2") (pintype "passive"))
      (node (ref "TP6") (pin "P$1") (pinfunction "TP_P$1") (pintype "passive"))
    )
    (net (code "147") (name "PHOTO_PIN") (class "Default")
      (node (ref "IC3") (pin "24") (pinfunction "RB1/AN1/CN3/PGC1/RP1_24") (pintype "bidirectional"))
      (node (ref "R8") (pin "1") (pinfunction "1_1") (pintype "passive"))
    )
    (net (code "148") (name "PHOTO_PWR") (class "Default")
      (node (ref "IC3") (pin "25") (pinfunction "RB0/AN0/CN2/PGD1/RP0_25") (pintype "bidirectional"))
      (node (ref "R7") (pin "1") (pinfunction "1_1") (pintype "passive"))
    )
    (net (code "149") (name "PIC_INT") (class "Default")
      (node (ref "IC3") (pin "38") (pinfunction "RA1/TCK_38") (pintype "bidirectional"))
      (node (ref "J1") (pin "3") (pinfunction "3_3") (pintype "passive"))
    )
    (net (code "150") (name "RTC_CS") (class "Default")
      (node (ref "IC3") (pin "79") (pinfunction "CN57/RPI42/RD12_79") (pintype "bidirectional"))
      (node (ref "IC7") (pin "6") (pinfunction "CE_6") (pintype "input"))
      (node (ref "R22") (pin "2") (pinfunction "2_2") (pintype "passive"))
    )
    (net (code "151") (name "RTC_INT") (class "Default")
      (node (ref "IC3") (pin "80") (pinfunction "CN19/RD13_80") (pintype "bidirectional"))
      (node (ref "IC7") (pin "5") (pinfunction "/INT_5") (pintype "output"))
    )
    (net (code "152") (name "SBC_5V_VBUS") (class "Default")
      (node (ref "C114") (pin "2") (pinfunction "2_2") (pintype "passive"))
      (node (ref "C115") (pin "2") (pinfunction "2_2") (pintype "passive"))
      (node (ref "IC18") (pin "19") (pinfunction "/RESET_19") (pintype "bidirectional"))
      (node (ref "IC18") (pin "20") (pinfunction "VCC5I_20") (pintype "power_in"))
      (node (ref "J41") (pin "3") (pinfunction "3_3") (pintype "passive"))
      (node (ref "R151") (pin "2") (pinfunction "2_2") (pintype "passive"))
      (node (ref "R152") (pin "2") (pinfunction "2_2") (pintype "passive"))
      (node (ref "X2") (pin "1") (pinfunction "1_1") (pintype "passive"))
    )
    (net (code "153") (name "SBC_LINL") (class "Default")
      (node (ref "C184") (pin "2") (pinfunction "2_2") (pintype "passive"))
      (node (ref "J17") (pin "4") (pinfunction "4_4") (pintype "bidirectional"))
      (node (ref "J47") (pin "6") (pinfunction "6_6") (pintype "passive"))
    )
    (net (code "154") (name "SBC_LINR") (class "Default")
      (node (ref "C183") (pin "2") (pinfunction "2_2") (pintype "passive"))
      (node (ref "J17") (pin "5") (pinfunction "5_5") (pintype "bidirectional"))
      (node (ref "J47") (pin "2") (pinfunction "2_2") (pintype "passive"))
    )
    (net (code "155") (name "SBC_LOUTL") (class "Default")
      (node (ref "C175") (pin "1") (pinfunction "1_1") (pintype "passive"))
      (node (ref "J17") (pin "7") (pinfunction "7_7") (pintype "bidirectional"))
      (node (ref "J47") (pin "5") (pinfunction "5_5") (pintype "passive"))
    )
    (net (code "156") (name "SBC_LOUTR") (class "Default")
      (node (ref "C174") (pin "1") (pinfunction "1_1") (pintype "passive"))
      (node (ref "J17") (pin "8") (pinfunction "8_8") (pintype "bidirectional"))
      (node (ref "J47") (pin "1") (pinfunction "1_1") (pintype "passive"))
    )
    (net (code "157") (name "SBC_USB_B_D_N") (class "Default")
      (node (ref "IC18") (pin "16") (pinfunction "USBDM_16") (pintype "bidirectional"))
      (node (ref "X2") (pin "2") (pinfunction "2_2") (pintype "passive"))
    )
    (net (code "158") (name "SBC_USB_B_D_P") (class "Default")
      (node (ref "IC18") (pin "15") (pinfunction "USBDP_15") (pintype "bidirectional"))
      (node (ref "X2") (pin "3") (pinfunction "3_3") (pintype "passive"))
    )
    (net (code "159") (name "SCL1") (class "Default")
      (node (ref "IC3") (pin "57") (pinfunction "RG2/SCL1/CN83_57") (pintype "bidirectional"))
      (node (ref "IC5") (pin "2") (pinfunction "SCL_2") (pintype "input"))
      (node (ref "IC6") (pin "6") (pinfunction "SCL_6") (pintype "input"))
      (node (ref "J8") (pin "16") (pinfunction "16_16") (pintype "passive"))
      (node (ref "R16") (pin "1") (pinfunction "1_1") (pintype "passive"))
      (node (ref "R32") (pin "1") (pinfunction "1_1") (pintype "passive"))
      (node (ref "U3") (pin "1") (pinfunction "ADDR_1") (pintype "bidirectional"))
      (node (ref "U3") (pin "10") (pinfunction "SCL_10") (pintype "bidirectional"))
    )
    (net (code "160") (name "SCLK1") (class "Default")
      (node (ref "IC3") (pin "77") (pinfunction "CN51/RP23/RD2_77") (pintype "bidirectional"))
      (node (ref "IC7") (pin "10") (pinfunction "SCL_10") (pintype "input"))
      (node (ref "IC8") (pin "6") (pinfunction "C_6") (pintype "input"))
    )
    (net (code "161") (name "SCLK2") (class "Default")
      (node (ref "IC3") (pin "10") (pinfunction "RG6/CN8/RP21_10") (pintype "bidirectional"))
      (node (ref "J1") (pin "5") (pinfunction "5_5") (pintype "passive"))
      (node (ref "J8") (pin "12") (pinfunction "12_12") (pintype "passive"))
      (node (ref "U1") (pin "31") (pinfunction "ASYNC_31") (pintype "bidirectional"))
    )
    (net (code "162") (name "SCLK_SM_B") (class "Default")
      (node (ref "IC3") (pin "8") (pinfunction "RC3/CN47/RPI40_8") (pintype "bidirectional"))
      (node (ref "U1") (pin "26") (pinfunction "SCLK_26") (pintype "bidirectional"))
    )
    (net (code "163") (name "SDA1") (class "Default")
      (node (ref "IC3") (pin "56") (pinfunction "RG3/SDA1/CN84_56") (pintype "bidirectional"))
      (node (ref "IC5") (pin "1") (pinfunction "SDA_1") (pintype "bidirectional"))
      (node (ref "IC6") (pin "5") (pinfunction "SDA_5") (pintype "bidirectional"))
      (node (ref "J8") (pin "15") (pinfunction "15_15") (pintype "passive"))
      (node (ref "R17") (pin "1") (pinfunction "1_1") (pintype "passive"))
      (node (ref "R31") (pin "1") (pinfunction "1_1") (pintype "passive"))
      (node (ref "U3") (pin "9") (pinfunction "SDA_9") (pintype "bidirectional"))
    )
    (net (code "164") (name "SDI1") (class "Default")
      (node (ref "IC3") (pin "72") (pinfunction "CN49/RP11/RD0_72") (pintype "bidirectional"))
      (node (ref "IC7") (pin "8") (pinfunction "SDO_8") (pintype "output"))
      (node (ref "IC8") (pin "2") (pinfunction "Q_2") (pintype "bidirectional"))
    )
    (net (code "165") (name "SDI2") (class "Default")
      (node (ref "IC3") (pin "11") (pinfunction "RG7/CN9/RP26_11") (pintype "bidirectional"))
      (node (ref "J1") (pin "8") (pinfunction "8_8") (pintype "passive"))
      (node (ref "J8") (pin "11") (pinfunction "11_11") (pintype "passive"))
    )
    (net (code "166") (name "SDO1") (class "Default")
      (node (ref "IC3") (pin "76") (pinfunction "CN50/RP24/RD1_76") (pintype "bidirectional"))
      (node (ref "IC7") (pin "9") (pinfunction "SDI_9") (pintype "input"))
      (node (ref "IC8") (pin "5") (pinfunction "D_5") (pintype "input"))
    )
    (net (code "167") (name "SDO2") (class "Default")
      (node (ref "IC3") (pin "12") (pinfunction "CN10/RP19/RG8_12") (pintype "bidirectional"))
      (node (ref "J1") (pin "6") (pinfunction "6_6") (pintype "passive"))
      (node (ref "J8") (pin "14") (pinfunction "14_14") (pintype "passive"))
    )
    (net (code "168") (name "SMB_SCL") (class "Default")
      (node (ref "D31") (pin "6") (pinfunction "AK_6") (pintype "passive"))
      (node (ref "IC3") (pin "66") (pinfunction "RA14/RPI36/CN43_66") (pintype "bidirectional"))
      (node (ref "R190") (pin "1") (pinfunction "1_1") (pintype "passive"))
      (node (ref "R46") (pin "1") (pinfunction "1_1") (pintype "passive"))
    )
    (net (code "169") (name "SMB_SDA") (class "Default")
      (node (ref "D31") (pin "3") (pinfunction "AK_3") (pintype "passive"))
      (node (ref "IC3") (pin "67") (pinfunction "RA15/RPI35/CN44_67") (pintype "bidirectional"))
      (node (ref "R187") (pin "1") (pinfunction "1_1") (pintype "passive"))
      (node (ref "R45") (pin "1") (pinfunction "1_1") (pintype "passive"))
    )
    (net (code "170") (name "SM_C4A") (class "Default")
      (node (ref "J3") (pin "2") (pinfunction "2_2") (pintype "bidirectional"))
      (node (ref "U1") (pin "4") (pinfunction "C4A_4") (pintype "bidirectional"))
      (node (ref "X1") (pin "2") (pinfunction "1_2") (pintype "passive"))
    )
    (net (code "171") (name "SM_C8A") (class "Default")
      (node (ref "J3") (pin "1") (pinfunction "1_1") (pintype "bidirectional"))
      (node (ref "U1") (pin "3") (pinfunction "C8A_3") (pintype "bidirectional"))
      (node (ref "X1") (pin "1") (pinfunction "1_1") (pintype "passive"))
    )
    (net (code "172") (name "SM_CLK_A") (class "Default")
      (node (ref "J3") (pin "4") (pinfunction "4_4") (pintype "bidirectional"))
      (node (ref "U1") (pin "7") (pinfunction "CLKA_7") (pintype "bidirectional"))
      (node (ref "X1") (pin "4") (pinfunction "1_4") (pintype "passive"))
    )
    (net (code "173") (name "SM_DATA") (class "Default")
      (node (ref "IC3") (pin "14") (pinfunction "CN11/RP27/RG9_14") (pintype "bidirectional"))
      (node (ref "U1") (pin "29") (pinfunction "DATA_29") (pintype "bidirectional"))
    )
    (net (code "174") (name "SM_DET_A") (class "Default")
      (node (ref "J3") (pin "10") (pinfunction "10_10") (pintype "bidirectional"))
      (node (ref "U1") (pin "2") (pinfunction "PRESA_2") (pintype "bidirectional"))
      (node (ref "X1") (pin "10") (pinfunction "1_10") (pintype "passive"))
    )
    (net (code "175") (name "SM_IO_A") (class "Default")
      (node (ref "J3") (pin "3") (pinfunction "3_3") (pintype "bidirectional"))
      (node (ref "U1") (pin "5") (pinfunction "IOA_5") (pintype "bidirectional"))
      (node (ref "X1") (pin "3") (pinfunction "1_3") (pintype "passive"))
    )
    (net (code "176") (name "SM_RST") (class "Default")
      (node (ref "IC3") (pin "5") (pinfunction "CN65/SDA3/RE7_5") (pintype "bidirectional"))
      (node (ref "U1") (pin "30") (pinfunction "RIN_30") (pintype "bidirectional"))
    )
    (net (code "177") (name "SM_RST_A") (class "Default")
      (node (ref "J3") (pin "6") (pinfunction "6_6") (pintype "bidirectional"))
      (node (ref "U1") (pin "6") (pinfunction "RSTA_6") (pintype "bidirectional"))
      (node (ref "X1") (pin "6") (pinfunction "1_6") (pintype "passive"))
    )
    (net (code "178") (name "SM_SYNC") (class "Default")
      (node (ref "IC3") (pin "4") (pinfunction "CN64/SCL3/RE6_4") (pintype "bidirectional"))
      (node (ref "U1") (pin "32") (pinfunction "SYNC_32") (pintype "bidirectional"))
    )
    (net (code "179") (name "SM_VCC_A") (class "Default")
      (node (ref "J3") (pin "9") (pinfunction "9_9") (pintype "bidirectional"))
      (node (ref "U1") (pin "8") (pinfunction "VCCA_8") (pintype "bidirectional"))
      (node (ref "X1") (pin "9") (pinfunction "1_9") (pintype "passive"))
    )
    (net (code "180") (name "SNDR") (class "Default")
      (node (ref "IC3") (pin "35") (pinfunction "RB11/AN11/CN29_35") (pintype "bidirectional"))
    )
    (net (code "181") (name "SPKR1_P") (class "Default")
      (node (ref "C176") (pin "1") (pinfunction "1_1") (pintype "passive"))
      (node (ref "J17") (pin "11") (pinfunction "11_11") (pintype "bidirectional"))
      (node (ref "J4") (pin "1") (pinfunction "1_1") (pintype "passive"))
      (node (ref "L15") (pin "1") (pinfunction "1_1") (pintype "passive"))
    )
    (net (code "182") (name "SPKR_N") (class "Default")
      (node (ref "C179") (pin "1") (pinfunction "1_1") (pintype "passive"))
      (node (ref "J17") (pin "10") (pinfunction "10_10") (pintype "bidirectional"))
      (node (ref "J4") (pin "2") (pinfunction "2_2") (pintype "passive"))
      (node (ref "L16") (pin "1") (pinfunction "1_1") (pintype "passive"))
    )
    (net (code "183") (name "STRIKE_EN") (class "Default")
      (node (ref "IC3") (pin "47") (pinfunction "CN20/RPI43/RD14_47") (pintype "bidirectional"))
      (node (ref "Q18") (pin "2") (pinfunction "G_2") (pintype "passive"))
      (node (ref "R174") (pin "1") (pinfunction "1_1") (pintype "passive"))
      (node (ref "R179") (pin "2") (pinfunction "2_2") (pintype "passive"))
      (node (ref "U7") (pin "15") (pinfunction "EN_15") (pintype "input"))
    )
    (net (code "184") (name "STR_BOOT") (class "Default")
      (node (ref "C140") (pin "1") (pinfunction "1_1") (pintype "passive"))
      (node (ref "U7") (pin "11") (pinfunction "BOOT_11") (pintype "passive"))
    )
    (net (code "185") (name "STR_COMP") (class "Default")
      (node (ref "C146") (pin "1") (pinfunction "1_1") (pintype "passive"))
      (node (ref "R181") (pin "2") (pinfunction "2_2") (pintype "passive"))
      (node (ref "U7") (pin "3") (pinfunction "COMP_3") (pintype "passive"))
    )
    (net (code "186") (name "STR_FB") (class "Default")
      (node (ref "R177") (pin "1") (pinfunction "1_1") (pintype "passive"))
      (node (ref "R185") (pin "2") (pinfunction "2_2") (pintype "passive"))
      (node (ref "U7") (pin "4") (pinfunction "FB_4") (pintype "input"))
    )
    (net (code "187") (name "STR_FEED") (class "Default")
      (node (ref "L12") (pin "2") (pinfunction "2_2") (pintype "passive"))
      (node (ref "R172") (pin "2") (pinfunction "2_2") (pintype "passive"))
      (node (ref "R44") (pin "2") (pinfunction "2_2") (pintype "passive"))
    )
    (net (code "188") (name "STR_HDRV") (class "Default")
      (node (ref "R178") (pin "2") (pinfunction "2_2") (pintype "passive"))
      (node (ref "U7") (pin "13") (pinfunction "HDRV_13") (pintype "output"))
    )
    (net (code "189") (name "STR_HG1") (class "Default")
      (node (ref "Q19") (pin "3") (pinfunction "TG_3") (pintype "passive"))
      (node (ref "R178") (pin "1") (pinfunction "1_1") (pintype "passive"))
    )
    (net (code "190") (name "STR_ISNS+") (class "Default")
      (node (ref "C138") (pin "1") (pinfunction "1_1") (pintype "passive"))
      (node (ref "R171") (pin "1") (pinfunction "1_1") (pintype "passive"))
      (node (ref "U7") (pin "6") (pinfunction "ISNS+_6") (pintype "input"))
    )
    (net (code "191") (name "STR_ISNS-") (class "Default")
      (node (ref "C138") (pin "2") (pinfunction "2_2") (pintype "passive"))
      (node (ref "R172") (pin "1") (pinfunction "1_1") (pintype "passive"))
      (node (ref "U7") (pin "5") (pinfunction "ISNS-_5") (pintype "input"))
    )
    (net (code "192") (name "STR_L") (class "Default")
      (node (ref "D22") (pin "A") (pinfunction "A_A") (pintype "passive"))
      (node (ref "L12") (pin "1") (pinfunction "1_1") (pintype "passive"))
      (node (ref "Q19") (pin "6") (pinfunction "VSW_6") (pintype "passive"))
      (node (ref "Q19") (pin "7") (pinfunction "VSW_7") (pintype "passive"))
      (node (ref "Q19") (pin "8") (pinfunction "VSW_8") (pintype "passive"))
    )
    (net (code "193") (name "STR_LDRV") (class "Default")
      (node (ref "R180") (pin "2") (pinfunction "2_2") (pintype "passive"))
      (node (ref "U7") (pin "8") (pinfunction "LDRV_8") (pintype "output"))
    )
    (net (code "194") (name "STR_LG1") (class "Default")
      (node (ref "Q19") (pin "5") (pinfunction "BG_5") (pintype "passive"))
      (node (ref "R180") (pin "1") (pinfunction "1_1") (pintype "passive"))
    )
    (net (code "195") (name "STR_PG") (class "Default")
      (node (ref "IC3") (pin "74") (pinfunction "RC14/SOSCO/CN0/RPI37_74") (pintype "bidirectional"))
      (node (ref "R186") (pin "1") (pinfunction "1_1") (pintype "passive"))
      (node (ref "U7") (pin "14") (pinfunction "PGOOD_14") (pintype "open_collector"))
    )
    (net (code "196") (name "STR_RC") (class "Default")
      (node (ref "C148") (pin "1") (pinfunction "1_1") (pintype "passive"))
      (node (ref "R181") (pin "1") (pinfunction "1_1") (pintype "passive"))
    )
    (net (code "197") (name "STR_RT") (class "Default")
      (node (ref "R182") (pin "2") (pinfunction "2_2") (pintype "passive"))
      (node (ref "U7") (pin "1") (pinfunction "RT/CLK_1") (pintype "passive"))
    )
    (net (code "198") (name "STR_SS") (class "Default")
      (node (ref "C147") (pin "1") (pinfunction "1_1") (pintype "passive"))
      (node (ref "U7") (pin "2") (pinfunction "SS_2") (pintype "passive"))
    )
    (net (code "199") (name "STR_SW") (class "Default")
      (node (ref "C140") (pin "2") (pinfunction "2_2") (pintype "passive"))
      (node (ref "Q19") (pin "4") (pinfunction "TGR_4") (pintype "passive"))
      (node (ref "U7") (pin "12") (pinfunction "SW_12") (pintype "output"))
    )
    (net (code "200") (name "STR_VCC") (class "Default")
      (node (ref "C141") (pin "1") (pinfunction "1_1") (pintype "passive"))
      (node (ref "U7") (pin "10") (pinfunction "VCC_10") (pintype "output"))
    )
    (net (code "201") (name "U1RX") (class "Default")
      (node (ref "IC18") (pin "1") (pinfunction "TXD_1") (pintype "output"))
      (node (ref "IC3") (pin "70") (pinfunction "CN55/RP3/RD10_70") (pintype "bidirectional"))
      (node (ref "J41") (pin "4") (pinfunction "4_4") (pintype "passive"))
    )
    (net (code "202") (name "U1TX") (class "Default")
      (node (ref "IC18") (pin "5") (pinfunction "RXD_5") (pintype "input"))
      (node (ref "IC3") (pin "71") (pinfunction "CN56/RP12/RD11_71") (pintype "bidirectional"))
      (node (ref "J41") (pin "5") (pinfunction "5_5") (pintype "passive"))
    )
    (net (code "203") (name "U2CTL") (class "Default")
      (node (ref "IC2") (pin "2") (pinfunction "/RE_2") (pintype "input"))
      (node (ref "IC2") (pin "3") (pinfunction "DE_3") (pintype "input"))
      (node (ref "IC3") (pin "19") (pinfunction "RPI34/CN67/RE9_19") (pintype "bidirectional"))
    )
    (net (code "204") (name "U2RX") (class "Default")
      (node (ref "IC2") (pin "1") (pinfunction "R_1") (pintype "output"))
      (node (ref "IC3") (pin "81") (pinfunction "CN13/RP25/RD4_81") (pintype "bidirectional"))
    )
    (net (code "205") (name "U2TX") (class "Default")
      (node (ref "IC2") (pin "4") (pinfunction "D_4") (pintype "input"))
      (node (ref "IC3") (pin "82") (pinfunction "CN14/RP20/RD5_82") (pintype "bidirectional"))
    )
    (net (code "206") (name "U3RX") (class "Default")
      (node (ref "IC3") (pin "23") (pinfunction "RB2/AN2/CN4/RP13_23") (pintype "bidirectional"))
      (node (ref "J2") (pin "3") (pinfunction "3_3") (pintype "passive"))
      (node (ref "JP1") (pin "3") (pinfunction "3_3") (pintype "passive"))
    )
    (net (code "207") (name "U3TX") (class "Default")
      (node (ref "IC3") (pin "33") (pinfunction "RB9/AN9/CN27/RP9_33") (pintype "bidirectional"))
      (node (ref "J2") (pin "4") (pinfunction "4_4") (pintype "passive"))
      (node (ref "JP1") (pin "4") (pinfunction "4_4") (pintype "passive"))
    )
    (net (code "208") (name "US-S_O") (class "Default")
      (node (ref "IC3") (pin "78") (pinfunction "CN52/RP22/RD3_78") (pintype "bidirectional"))
      (node (ref "J18") (pin "11") (pinfunction "11_11") (pintype "bidirectional"))
      (node (ref "J30") (pin "5") (pinfunction "SERIAL_5") (pintype "bidirectional"))
    )
    (net (code "209") (name "USRF_EN") (class "Default")
      (node (ref "IC3") (pin "97") (pinfunction "CN80/RG13_97") (pintype "bidirectional"))
      (node (ref "J18") (pin "12") (pinfunction "12_12") (pintype "bidirectional"))
      (node (ref "J30") (pin "4") (pinfunction "EN_4") (pintype "bidirectional"))
    )
    (net (code "210") (name "VACT") (class "Default")
      (node (ref "C142") (pin "1") (pinfunction "1_1") (pintype "passive"))
      (node (ref "C143") (pin "1") (pinfunction "1_1") (pintype "passive"))
      (node (ref "C144") (pin "1") (pinfunction "1_1") (pintype "passive"))
      (node (ref "C145") (pin "1") (pinfunction "1_1") (pintype "passive"))
      (node (ref "C43") (pin "+") (pinfunction "+_+") (pintype "passive"))
      (node (ref "D21") (pin "+") (pinfunction "C_+") (pintype "passive"))
      (node (ref "D22") (pin "K") (pinfunction "K_K") (pintype "passive"))
      (node (ref "D25") (pin "C") (pinfunction "K_C") (pintype "passive"))
      (node (ref "D26") (pin "C") (pinfunction "K_C") (pintype "passive"))
      (node (ref "J15") (pin "11") (pinfunction "11_11") (pintype "bidirectional"))
      (node (ref "J15") (pin "11A") (pinfunction "11_11A") (pintype "bidirectional"))
      (node (ref "J16") (pin "1") (pinfunction "1_1") (pintype "bidirectional"))
      (node (ref "J16") (pin "1A") (pinfunction "1_1A") (pintype "bidirectional"))
      (node (ref "J18") (pin "1") (pinfunction "1_1") (pintype "bidirectional"))
      (node (ref "Q19") (pin "1_2") (pinfunction "VIN_1_2") (pintype "passive"))
      (node (ref "R175") (pin "2") (pinfunction "2_2") (pintype "passive"))
      (node (ref "R176") (pin "2") (pinfunction "2_2") (pintype "passive"))
      (node (ref "R177") (pin "2") (pinfunction "2_2") (pintype "passive"))
      (node (ref "TP62") (pin "TP") (pinfunction "TP_TP") (pintype "input"))
    )
    (net (code "211") (name "VPS_ON") (class "Default")
      (node (ref "IC3") (pin "100") (pinfunction "CN62/RE4_100") (pintype "bidirectional"))
      (node (ref "Q2") (pin "5") (pinfunction "Q1G_5") (pintype "input"))
      (node (ref "R5") (pin "2") (pinfunction "2_2") (pintype "passive"))
    )
    (net (code "212") (name "VPS_PWR") (class "Default")
      (node (ref "J7") (pin "5") (pinfunction "5_5") (pintype "passive"))
      (node (ref "J9") (pin "5") (pinfunction "5_5") (pintype "passive"))
      (node (ref "Q2") (pin "2") (pinfunction "Q2D1_2") (pintype "bidirectional"))
      (node (ref "Q2") (pin "3") (pinfunction "Q2D2_3") (pintype "bidirectional"))
      (node (ref "R4") (pin "2") (pinfunction "2_2") (pintype "passive"))
    )
    (net (code "213") (name "VPS_SEN") (class "Default")
      (node (ref "IC3") (pin "99") (pinfunction "CN61/RE3_99") (pintype "bidirectional"))
      (node (ref "R4") (pin "1") (pinfunction "1_1") (pintype "passive"))
      (node (ref "R6") (pin "2") (pinfunction "2_2") (pintype "passive"))
    )
    (net (code "214") (name "VREF2.5") (class "Default")
      (node (ref "C4") (pin "1") (pinfunction "1_1") (pintype "passive"))
      (node (ref "IC1") (pin "2") (pinfunction "VOUT_2") (pintype "output"))
      (node (ref "IC3") (pin "29") (pinfunction "RA10/VR+/CN42_29") (pintype "bidirectional"))
      (node (ref "TP1") (pin "P$1") (pinfunction "TP_P$1") (pintype "passive"))
    )
    (net (code "215") (name "VSOLAR") (class "Default")
      (node (ref "J1") (pin "2") (pinfunction "2_2") (pintype "passive"))
    )
    (net (code "216") (name "XB_RTS") (class "Default")
      (node (ref "IC3") (pin "48") (pinfunction "CN21/RP5/RD15_48") (pintype "bidirectional"))
      (node (ref "J2") (pin "7") (pinfunction "7_7") (pintype "passive"))
    )
    (net (code "217") (name "XB_SLEEP") (class "Default")
      (node (ref "IC3") (pin "22") (pinfunction "RB3/AN3/CN5_22") (pintype "bidirectional"))
      (node (ref "J2") (pin "5") (pinfunction "5_5") (pintype "passive"))
      (node (ref "JP1") (pin "5") (pinfunction "5_5") (pintype "passive"))
    )
    (net (code "218") (name "unconnected-(B1-+-Pad+2)") (class "Default")
      (node (ref "B1") (pin "+2") (pinfunction "+_+2") (pintype "passive"))
    )
    (net (code "219") (name "unconnected-(IC3-CN15{slash}RD6-Pad83)") (class "Default")
      (node (ref "IC3") (pin "83") (pinfunction "CN15/RD6_83") (pintype "bidirectional"))
    )
    (net (code "220") (name "unconnected-(IC3-CN58{slash}RE0-Pad93)") (class "Default")
      (node (ref "IC3") (pin "93") (pinfunction "CN58/RE0_93") (pintype "bidirectional"))
    )
    (net (code "221") (name "unconnected-(IC3-CN76{slash}RP31{slash}RF13-Pad39)") (class "Default")
      (node (ref "IC3") (pin "39") (pinfunction "CN76/RP31/RF13_39") (pintype "bidirectional"))
    )
    (net (code "222") (name "unconnected-(IC3-RA2{slash}SCL2-Pad58)") (class "Default")
      (node (ref "IC3") (pin "58") (pinfunction "RA2/SCL2_58") (pintype "bidirectional"))
    )
    (net (code "223") (name "unconnected-(IC3-RA3{slash}SDA2-Pad59)") (class "Default")
      (node (ref "IC3") (pin "59") (pinfunction "RA3/SDA2_59") (pintype "bidirectional"))
    )
    (net (code "224") (name "unconnected-(IC5-OS-Pad3)") (class "Default")
      (node (ref "IC5") (pin "3") (pinfunction "OS_3") (pintype "output"))
    )
    (net (code "225") (name "unconnected-(IC7-CLKOUT-Pad13)") (class "Default")
      (node (ref "IC7") (pin "13") (pinfunction "CLKOUT_13") (pintype "output"))
    )
    (net (code "226") (name "unconnected-(IC7-TEST-Pad4)") (class "Default")
      (node (ref "IC7") (pin "4") (pinfunction "TEST_4") (pintype "output"))
    )
    (net (code "227") (name "unconnected-(IC18-AVCC-NC-Pad24)") (class "Default")
      (node (ref "IC18") (pin "24") (pinfunction "AVCC-NC_24") (pintype "no_connect"))
    )
    (net (code "228") (name "unconnected-(IC18-GPIO2-Pad13)") (class "Default")
      (node (ref "IC18") (pin "13") (pinfunction "GPIO2_13") (pintype "output"))
    )
    (net (code "229") (name "unconnected-(IC18-GPIO3-Pad14)") (class "Default")
      (node (ref "IC18") (pin "14") (pinfunction "GPIO3_14") (pintype "bidirectional"))
    )
    (net (code "230") (name "unconnected-(IC18-OSCI-Pad27)") (class "Default")
      (node (ref "IC18") (pin "27") (pinfunction "OSCI_27") (pintype "bidirectional"))
    )
    (net (code "231") (name "unconnected-(IC18-OSCO-Pad28)") (class "Default")
      (node (ref "IC18") (pin "28") (pinfunction "OSCO_28") (pintype "output"))
    )
    (net (code "232") (name "unconnected-(IC18-VCC3I-NC-Pad8)") (class "Default")
      (node (ref "IC18") (pin "8") (pinfunction "VCC3I-NC_8") (pintype "no_connect"))
    )
    (net (code "233") (name "unconnected-(IC18-{slash}DCD-Pad10)") (class "Default")
      (node (ref "IC18") (pin "10") (pinfunction "/DCD_10") (pintype "bidirectional"))
    )
    (net (code "234") (name "unconnected-(IC18-{slash}DSR-Pad9)") (class "Default")
      (node (ref "IC18") (pin "9") (pinfunction "/DSR_9") (pintype "bidirectional"))
    )
    (net (code "235") (name "unconnected-(IC18-{slash}DTR-Pad2)") (class "Default")
      (node (ref "IC18") (pin "2") (pinfunction "/DTR_2") (pintype "output"))
    )
    (net (code "236") (name "unconnected-(IC18-{slash}RI-Pad6)") (class "Default")
      (node (ref "IC18") (pin "6") (pinfunction "/RI_6") (pintype "bidirectional"))
    )
    (net (code "237") (name "unconnected-(IC18-{slash}SLEEP-Pad12)") (class "Default")
      (node (ref "IC18") (pin "12") (pinfunction "/SLEEP_12") (pintype "bidirectional"))
    )
    (net (code "238") (name "unconnected-(J8-Pad1)") (class "Default")
      (node (ref "J8") (pin "1") (pinfunction "1_1") (pintype "passive"))
    )
    (net (code "239") (name "unconnected-(J8-Pad2)") (class "Default")
      (node (ref "J8") (pin "2") (pinfunction "2_2") (pintype "passive"))
    )
    (net (code "240") (name "unconnected-(J8-Pad3)") (class "Default")
      (node (ref "J8") (pin "3") (pinfunction "3_3") (pintype "passive"))
    )
    (net (code "241") (name "unconnected-(J8-Pad4)") (class "Default")
      (node (ref "J8") (pin "4") (pinfunction "4_4") (pintype "passive"))
    )
    (net (code "242") (name "unconnected-(J8-Pad5)") (class "Default")
      (node (ref "J8") (pin "5") (pinfunction "5_5") (pintype "passive"))
    )
    (net (code "243") (name "unconnected-(J8-Pad6)") (class "Default")
      (node (ref "J8") (pin "6") (pinfunction "6_6") (pintype "passive"))
    )
    (net (code "244") (name "unconnected-(J8-Pad7)") (class "Default")
      (node (ref "J8") (pin "7") (pinfunction "7_7") (pintype "passive"))
    )
    (net (code "245") (name "unconnected-(J8-Pad8)") (class "Default")
      (node (ref "J8") (pin "8") (pinfunction "8_8") (pintype "passive"))
    )
    (net (code "246") (name "unconnected-(J10-PadC4)") (class "Default")
      (node (ref "J10") (pin "C4") (pinfunction "C4_C4") (pintype "bidirectional"))
    )
    (net (code "247") (name "unconnected-(J10-PadC6)") (class "Default")
      (node (ref "J10") (pin "C6") (pinfunction "C6_C6") (pintype "bidirectional"))
    )
    (net (code "248") (name "unconnected-(J10-PadC8)") (class "Default")
      (node (ref "J10") (pin "C8") (pinfunction "C8_C8") (pintype "bidirectional"))
    )
    (net (code "249") (name "unconnected-(J30-AN{slash}O-Pad3)") (class "Default")
      (node (ref "J30") (pin "3") (pinfunction "AN/O_3") (pintype "bidirectional"))
    )
    (net (code "250") (name "unconnected-(J30-PWM-Pad2)") (class "Default")
      (node (ref "J30") (pin "2") (pinfunction "PWM_2") (pintype "bidirectional"))
    )
    (net (code "251") (name "unconnected-(J30-TEMP(NC)-Pad1)") (class "Default")
      (node (ref "J30") (pin "1") (pinfunction "TEMP(NC)_1") (pintype "bidirectional"))
    )
    (net (code "252") (name "unconnected-(J47-Pad7)") (class "Default")
      (node (ref "J47") (pin "7") (pinfunction "7_7") (pintype "passive"))
    )
    (net (code "253") (name "unconnected-(J47-Pad8)") (class "Default")
      (node (ref "J47") (pin "8") (pinfunction "8_8") (pintype "passive"))
    )
    (net (code "254") (name "unconnected-(J47-Pad9)") (class "Default")
      (node (ref "J47") (pin "9") (pinfunction "9_9") (pintype "passive"))
    )
    (net (code "255") (name "unconnected-(J47-Pad10)") (class "Default")
      (node (ref "J47") (pin "10") (pinfunction "10_10") (pintype "passive"))
    )
    (net (code "256") (name "unconnected-(JP1-Pad8)") (class "Default")
      (node (ref "JP1") (pin "8") (pinfunction "8_8") (pintype "passive"))
    )
    (net (code "257") (name "unconnected-(Q3-Pad4)") (class "Default")
      (node (ref "Q3") (pin "4") (pinfunction "4_4") (pintype "passive"))
    )
    (net (code "258") (name "unconnected-(U1-NC-Pad16)") (class "Default")
      (node (ref "U1") (pin "16") (pinfunction "NC_16") (pintype "bidirectional"))
    )
    (net (code "259") (name "unconnected-(U3-ALERT{slash}RDY-Pad2)") (class "Default")
      (node (ref "U3") (pin "2") (pinfunction "ALERT/RDY_2") (pintype "bidirectional"))
    )
    (net (code "260") (name "unconnected-(U8-NC-Pad13)") (class "Default")
      (node (ref "U8") (pin "13") (pinfunction "NC_13") (pintype "no_connect"))
    )
    (net (code "261") (name "unconnected-(X1F-1-Pad5)") (class "Default")
      (node (ref "X1") (pin "5") (pinfunction "1_5") (pintype "passive"))
    )
    (net (code "262") (name "{slash}3.3V1_ON") (class "Default")
      (node (ref "IC3") (pin "95") (pinfunction "CN81/RG14_95") (pintype "bidirectional"))
      (node (ref "Q7") (pin "2") (pinfunction "G_2") (pintype "passive"))
    )
    (net (code "263") (name "{slash}3.3V2_ON") (class "Default")
      (node (ref "IC3") (pin "94") (pinfunction "CN59/RE1_94") (pintype "bidirectional"))
      (node (ref "Q7") (pin "5") (pinfunction "G_5") (pintype "passive"))
    )
    (net (code "264") (name "{slash}3.3V3_ON") (class "Default")
      (node (ref "IC3") (pin "61") (pinfunction "RA5/TDO/CN38_61") (pintype "bidirectional"))
    )
    (net (code "265") (name "{slash}CL_CS1") (class "Default")
      (node (ref "IC3") (pin "1") (pinfunction "CN82/RG15_1") (pintype "bidirectional"))
      (node (ref "TP10") (pin "P$1") (pinfunction "TP_P$1") (pintype "passive"))
    )
    (net (code "266") (name "{slash}CL_CS2") (class "Default")
      (node (ref "IC3") (pin "17") (pinfunction "RA0/TMS_17") (pintype "bidirectional"))
      (node (ref "J1") (pin "7") (pinfunction "7_7") (pintype "passive"))
    )
    (net (code "267") (name "{slash}CTS") (class "Default")
      (node (ref "IC18") (pin "11") (pinfunction "/CTS_11") (pintype "bidirectional"))
      (node (ref "J41") (pin "2") (pinfunction "2_2") (pintype "passive"))
    )
    (net (code "268") (name "{slash}FMEM1_CS") (class "Default")
      (node (ref "IC3") (pin "28") (pinfunction "RA9/VR-/CN41_28") (pintype "bidirectional"))
      (node (ref "IC8") (pin "1") (pinfunction "/S_1") (pintype "input"))
      (node (ref "R24") (pin "2") (pinfunction "2_2") (pintype "passive"))
    )
    (net (code "269") (name "{slash}MCLR") (class "Default")
      (node (ref "IC3") (pin "13") (pinfunction "MCLR_13") (pintype "input"))
      (node (ref "IC4") (pin "4") (pinfunction "GP2/T0CK_4") (pintype "bidirectional"))
      (node (ref "J11") (pin "1") (pinfunction "1_1") (pintype "passive"))
      (node (ref "R14") (pin "1") (pinfunction "1_1") (pintype "passive"))
    )
    (net (code "270") (name "{slash}MCLR2") (class "Default")
      (node (ref "IC4") (pin "6") (pinfunction "GP3/MCLR_6") (pintype "bidirectional"))
      (node (ref "J12") (pin "1") (pinfunction "1_1") (pintype "passive"))
    )
    (net (code "271") (name "{slash}RAM_CS") (class "Default")
      (node (ref "IC3") (pin "3") (pinfunction "CN63/RE5_3") (pintype "bidirectional"))
      (node (ref "J8") (pin "13") (pinfunction "13_13") (pintype "passive"))
    )
    (net (code "272") (name "{slash}RTS") (class "Default")
      (node (ref "IC18") (pin "3") (pinfunction "/RTS_3") (pintype "output"))
      (node (ref "J41") (pin "6") (pinfunction "6_6") (pintype "passive"))
    )
    (net (code "273") (name "{slash}SM_FAULT") (class "Default")
      (node (ref "IC3") (pin "21") (pinfunction "RB4/AN4/CN6/RP28_21") (pintype "bidirectional"))
      (node (ref "U1") (pin "24") (pinfunction "-FAULT_24") (pintype "bidirectional"))
    )
    (net (code "274") (name "{slash}XB_RESET") (class "Default")
      (node (ref "IC3") (pin "18") (pinfunction "RPI33/CN66/RE8_18") (pintype "bidirectional"))
      (node (ref "J2") (pin "6") (pinfunction "6_6") (pintype "passive"))
      (node (ref "JP1") (pin "7") (pinfunction "7_7") (pintype "passive"))
    )
  )
)
